# HYBRID_COMPUTER.net
KiCad netlist of a schematic drawn in EAGLE
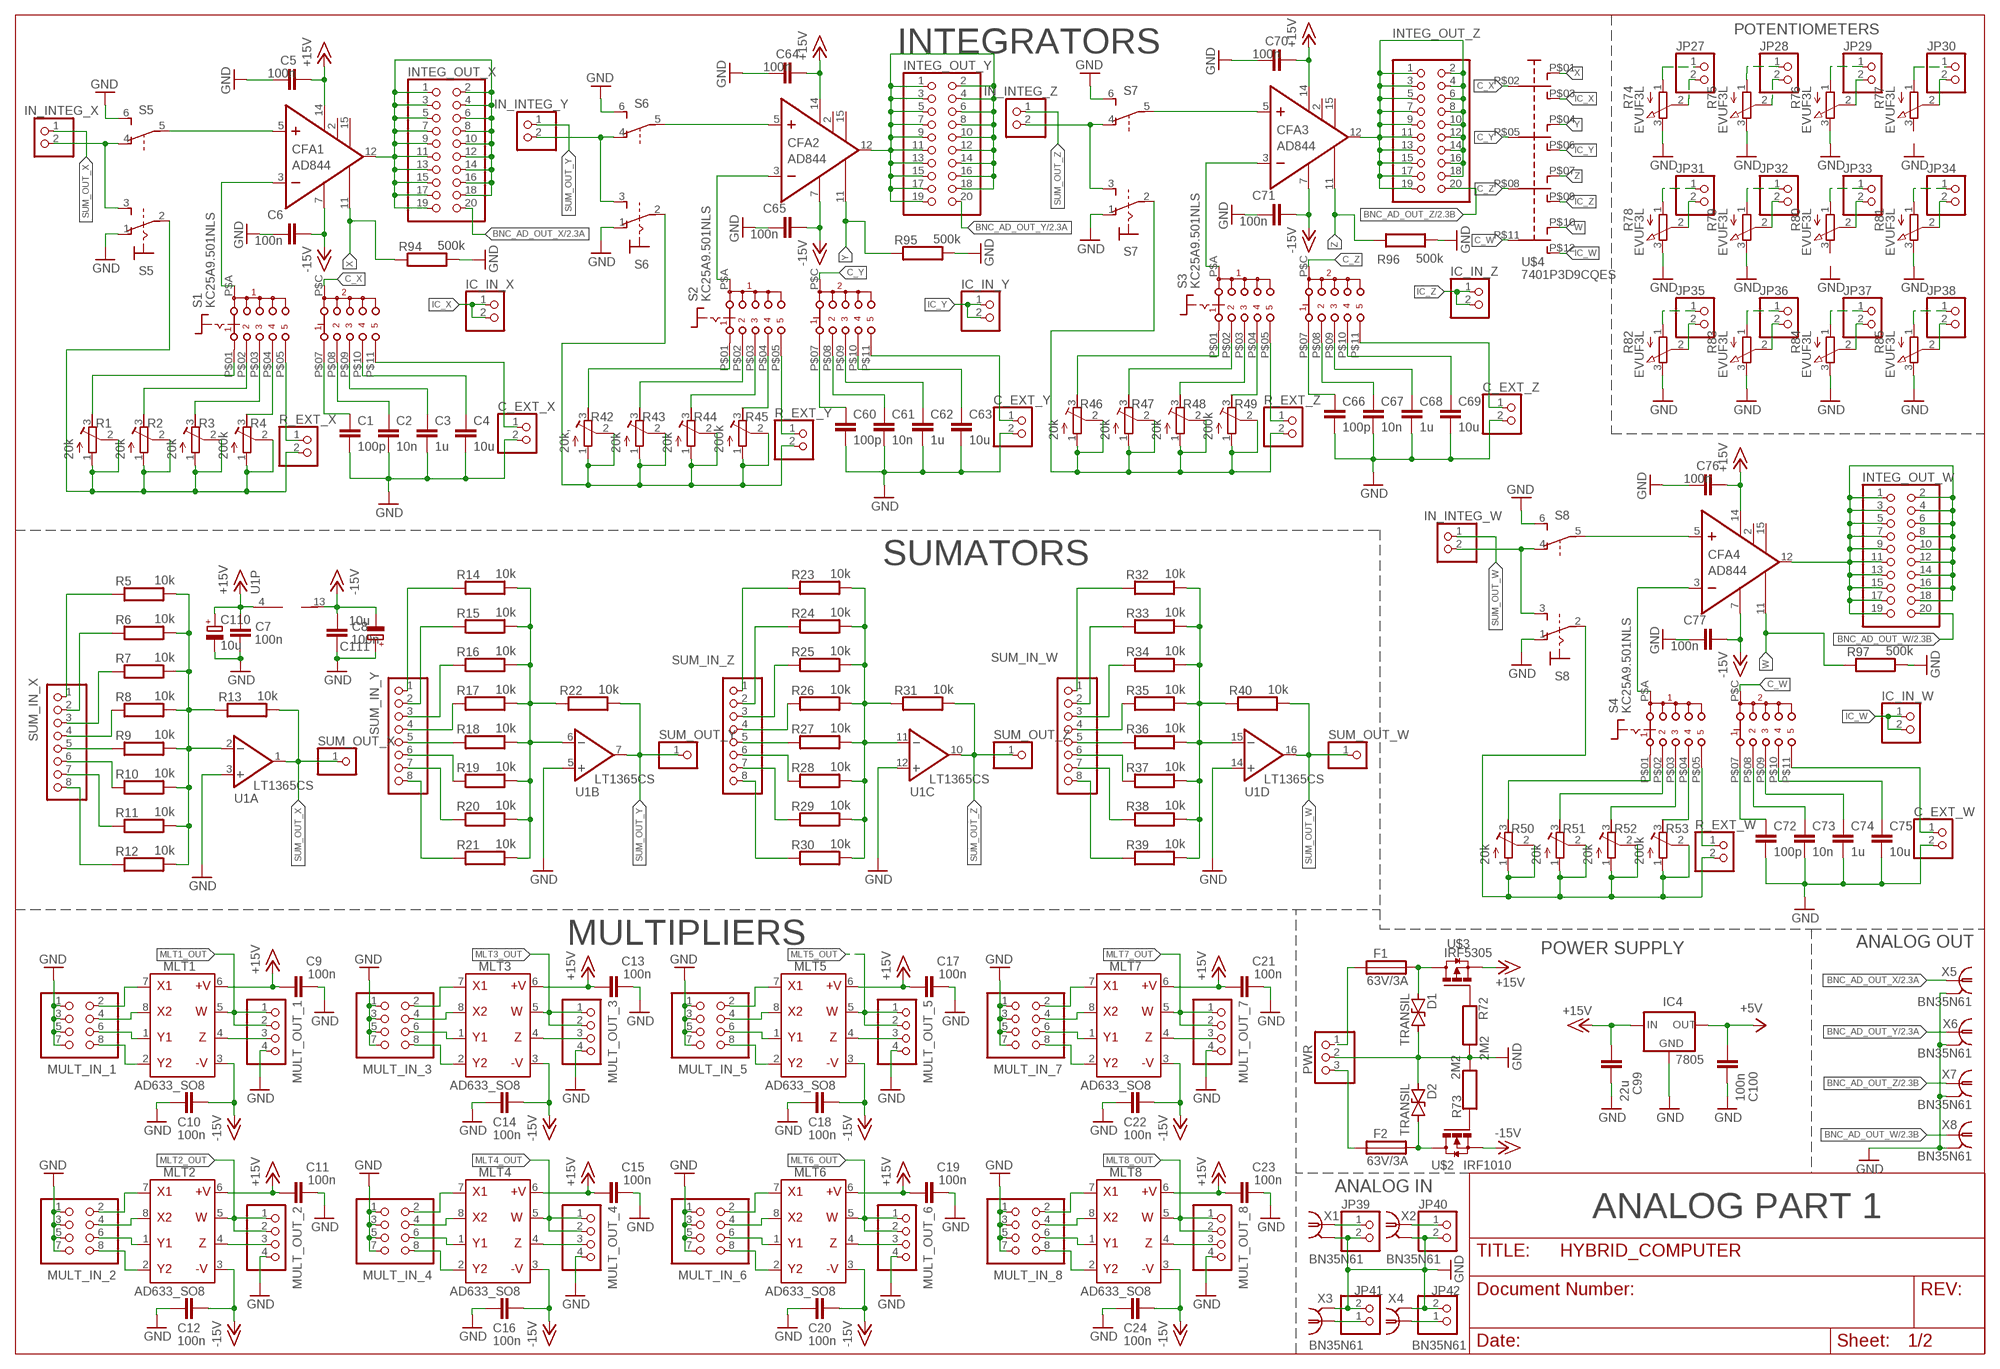
[diagram p0: schematic, sheet 1]
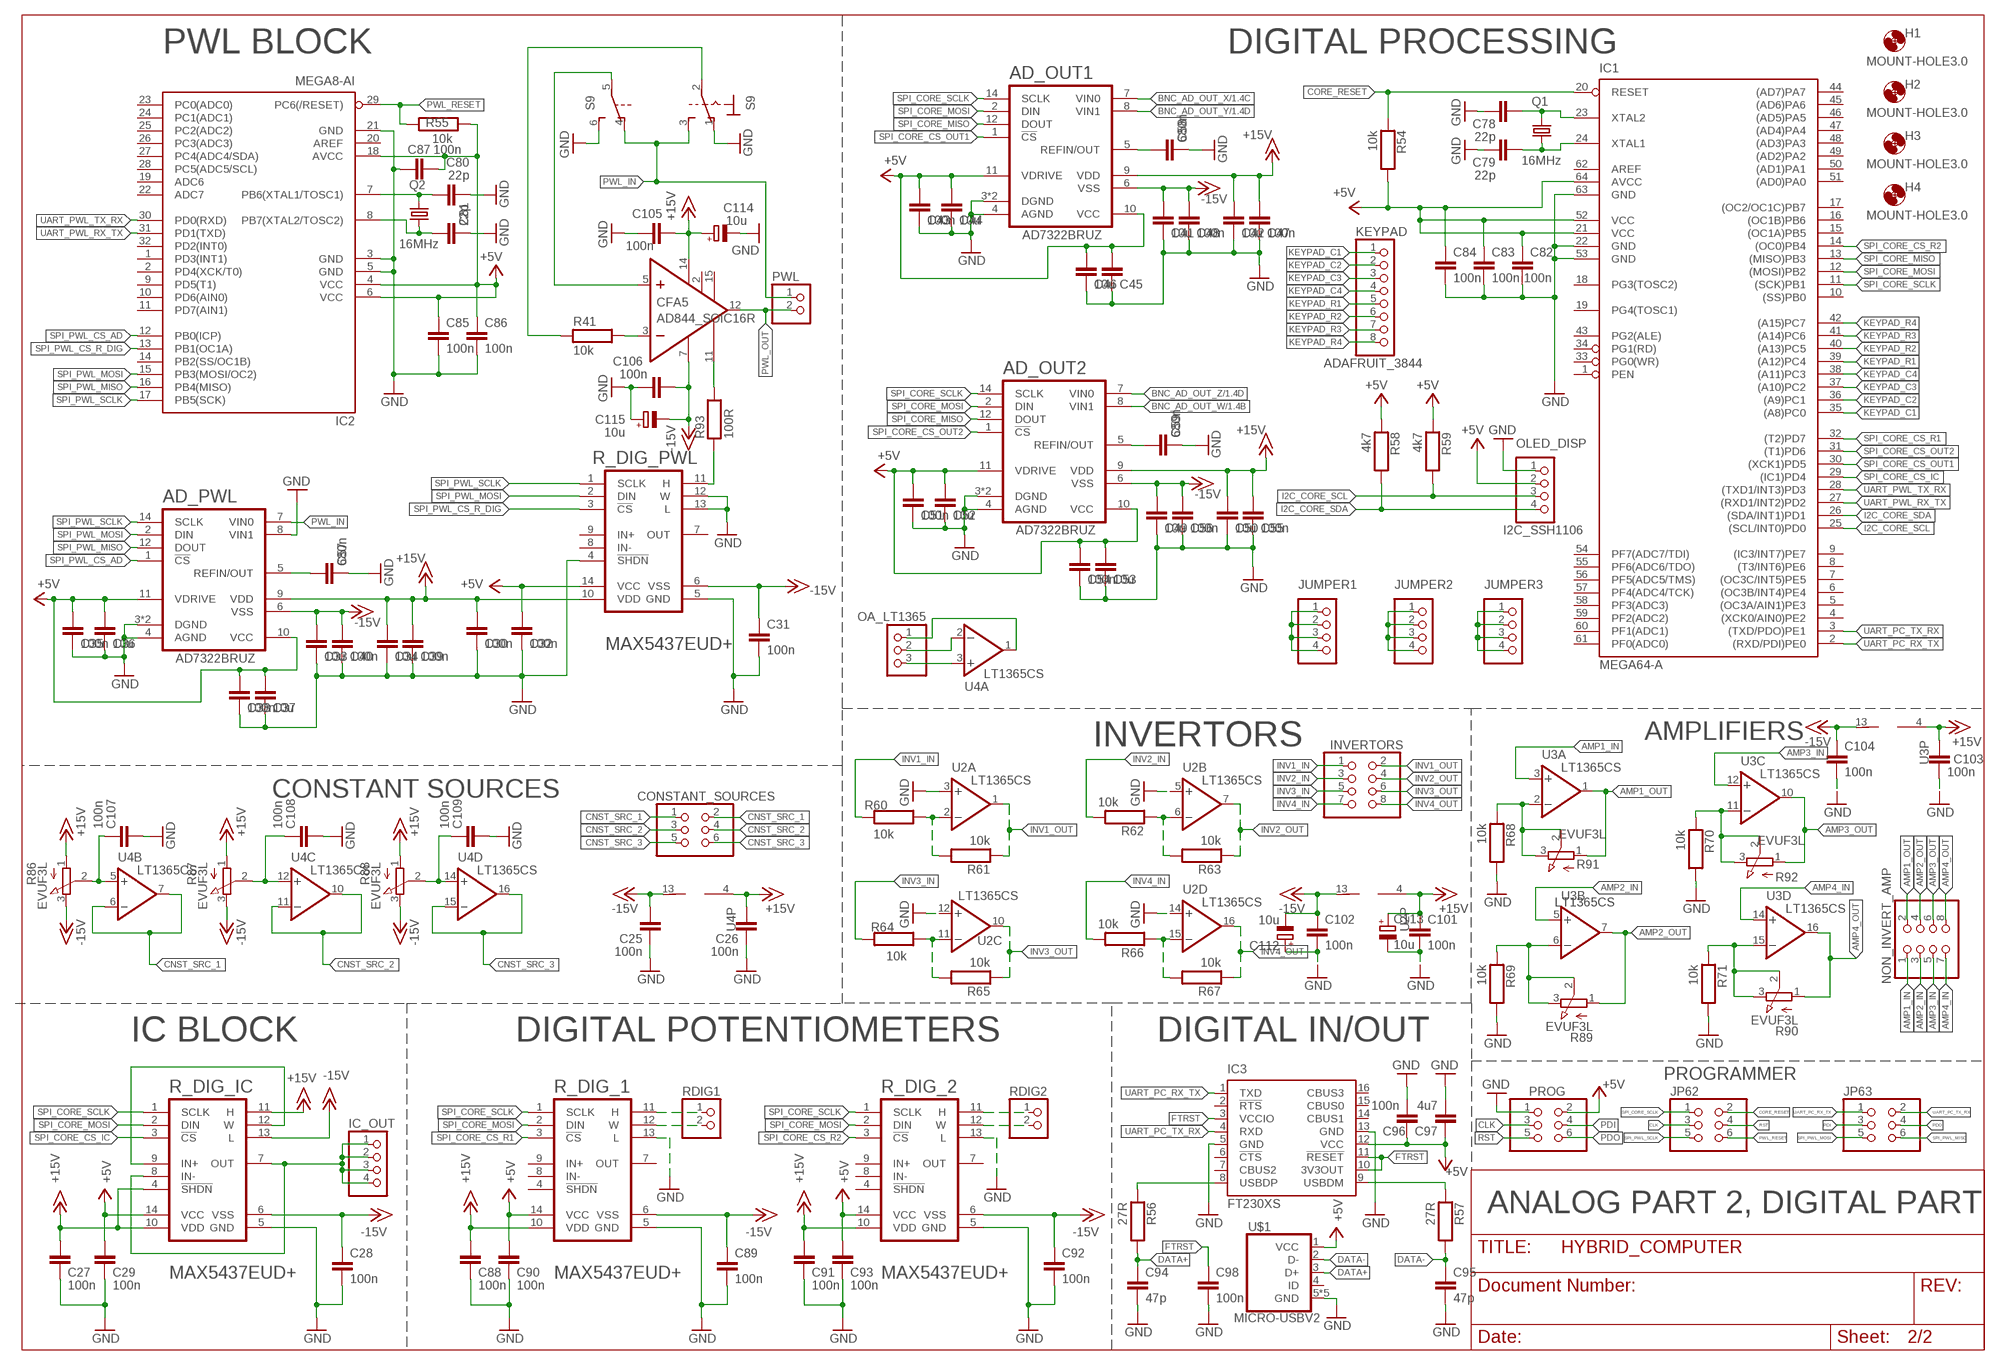
[diagram p1: schematic, sheet 2]

(export (version "E")
  (design (tool "Eeschema 10.0.6"))
  (components
    (comp (ref "C1")
      (value "100p")
      (footprint "eagle-import:C_1206")
      (libsource (lib "eagle-import") (part "C_1206"))
    )
    (comp (ref "C2")
      (value "10n")
      (footprint "eagle-import:C_1206")
      (libsource (lib "eagle-import") (part "C_1206"))
    )
    (comp (ref "C3")
      (value "1u")
      (footprint "eagle-import:C_1206")
      (libsource (lib "eagle-import") (part "C_1206"))
    )
    (comp (ref "C4")
      (value "10u")
      (footprint "eagle-import:C_1206")
      (libsource (lib "eagle-import") (part "C_1206"))
    )
    (comp (ref "C5")
      (value "100n")
      (footprint "eagle-import:C_1206")
      (libsource (lib "eagle-import") (part "C_1206"))
    )
    (comp (ref "C6")
      (value "100n")
      (footprint "eagle-import:C_1206")
      (libsource (lib "eagle-import") (part "C_1206"))
    )
    (comp (ref "C7")
      (value "100n")
      (footprint "eagle-import:C_1206")
      (libsource (lib "eagle-import") (part "C_1206"))
    )
    (comp (ref "C8")
      (value "100n")
      (footprint "eagle-import:C_1206")
      (libsource (lib "eagle-import") (part "C_1206"))
    )
    (comp (ref "C9")
      (value "100n")
      (footprint "eagle-import:C_1206")
      (libsource (lib "eagle-import") (part "C_1206"))
    )
    (comp (ref "C10")
      (value "100n")
      (footprint "eagle-import:C_1206")
      (libsource (lib "eagle-import") (part "C_1206"))
    )
    (comp (ref "C11")
      (value "100n")
      (footprint "eagle-import:C_1206")
      (libsource (lib "eagle-import") (part "C_1206"))
    )
    (comp (ref "C12")
      (value "100n")
      (footprint "eagle-import:C_1206")
      (libsource (lib "eagle-import") (part "C_1206"))
    )
    (comp (ref "C13")
      (value "100n")
      (footprint "eagle-import:C_1206")
      (libsource (lib "eagle-import") (part "C_1206"))
    )
    (comp (ref "C14")
      (value "100n")
      (footprint "eagle-import:C_1206")
      (libsource (lib "eagle-import") (part "C_1206"))
    )
    (comp (ref "C15")
      (value "100n")
      (footprint "eagle-import:C_1206")
      (libsource (lib "eagle-import") (part "C_1206"))
    )
    (comp (ref "C16")
      (value "100n")
      (footprint "eagle-import:C_1206")
      (libsource (lib "eagle-import") (part "C_1206"))
    )
    (comp (ref "C17")
      (value "100n")
      (footprint "eagle-import:C_1206")
      (libsource (lib "eagle-import") (part "C_1206"))
    )
    (comp (ref "C18")
      (value "100n")
      (footprint "eagle-import:C_1206")
      (libsource (lib "eagle-import") (part "C_1206"))
    )
    (comp (ref "C19")
      (value "100n")
      (footprint "eagle-import:C_1206")
      (libsource (lib "eagle-import") (part "C_1206"))
    )
    (comp (ref "C20")
      (value "100n")
      (footprint "eagle-import:C_1206")
      (libsource (lib "eagle-import") (part "C_1206"))
    )
    (comp (ref "C21")
      (value "100n")
      (footprint "eagle-import:C_1206")
      (libsource (lib "eagle-import") (part "C_1206"))
    )
    (comp (ref "C22")
      (value "100n")
      (footprint "eagle-import:C_1206")
      (libsource (lib "eagle-import") (part "C_1206"))
    )
    (comp (ref "C23")
      (value "100n")
      (footprint "eagle-import:C_1206")
      (libsource (lib "eagle-import") (part "C_1206"))
    )
    (comp (ref "C24")
      (value "100n")
      (footprint "eagle-import:C_1206")
      (libsource (lib "eagle-import") (part "C_1206"))
    )
    (comp (ref "C60")
      (value "100p")
      (footprint "eagle-import:C_1206")
      (libsource (lib "eagle-import") (part "C_1206"))
    )
    (comp (ref "C61")
      (value "10n")
      (footprint "eagle-import:C_1206")
      (libsource (lib "eagle-import") (part "C_1206"))
    )
    (comp (ref "C62")
      (value "1u")
      (footprint "eagle-import:C_1206")
      (libsource (lib "eagle-import") (part "C_1206"))
    )
    (comp (ref "C63")
      (value "10u")
      (footprint "eagle-import:C_1206")
      (libsource (lib "eagle-import") (part "C_1206"))
    )
    (comp (ref "C64")
      (value "100n")
      (footprint "eagle-import:C_1206")
      (libsource (lib "eagle-import") (part "C_1206"))
    )
    (comp (ref "C65")
      (value "100n")
      (footprint "eagle-import:C_1206")
      (libsource (lib "eagle-import") (part "C_1206"))
    )
    (comp (ref "C66")
      (value "100p")
      (footprint "eagle-import:C_1206")
      (libsource (lib "eagle-import") (part "C_1206"))
    )
    (comp (ref "C67")
      (value "10n")
      (footprint "eagle-import:C_1206")
      (libsource (lib "eagle-import") (part "C_1206"))
    )
    (comp (ref "C68")
      (value "1u")
      (footprint "eagle-import:C_1206")
      (libsource (lib "eagle-import") (part "C_1206"))
    )
    (comp (ref "C69")
      (value "10u")
      (footprint "eagle-import:C_1206")
      (libsource (lib "eagle-import") (part "C_1206"))
    )
    (comp (ref "C70")
      (value "100n")
      (footprint "eagle-import:C_1206")
      (libsource (lib "eagle-import") (part "C_1206"))
    )
    (comp (ref "C71")
      (value "100n")
      (footprint "eagle-import:C_1206")
      (libsource (lib "eagle-import") (part "C_1206"))
    )
    (comp (ref "C72")
      (value "100p")
      (footprint "eagle-import:C_1206")
      (libsource (lib "eagle-import") (part "C_1206"))
    )
    (comp (ref "C73")
      (value "10n")
      (footprint "eagle-import:C_1206")
      (libsource (lib "eagle-import") (part "C_1206"))
    )
    (comp (ref "C74")
      (value "1u")
      (footprint "eagle-import:C_1206")
      (libsource (lib "eagle-import") (part "C_1206"))
    )
    (comp (ref "C75")
      (value "10u")
      (footprint "eagle-import:C_1206")
      (libsource (lib "eagle-import") (part "C_1206"))
    )
    (comp (ref "C76")
      (value "100n")
      (footprint "eagle-import:C_1206")
      (libsource (lib "eagle-import") (part "C_1206"))
    )
    (comp (ref "C77")
      (value "100n")
      (footprint "eagle-import:C_1206")
      (libsource (lib "eagle-import") (part "C_1206"))
    )
    (comp (ref "C99")
      (value "22u")
      (footprint "eagle-import:C_1206")
      (libsource (lib "eagle-import") (part "C_1206"))
    )
    (comp (ref "C100")
      (value "100n")
      (footprint "eagle-import:C_1206")
      (libsource (lib "eagle-import") (part "C_1206"))
    )
    (comp (ref "C110")
      (value "10u")
      (footprint "eagle-import:E2,5-5")
      (libsource (lib "eagle-import") (part "CPOL-EUE2.5-5"))
    )
    (comp (ref "C111")
      (value "10u")
      (footprint "eagle-import:E2,5-5")
      (libsource (lib "eagle-import") (part "CPOL-EUE2.5-5"))
    )
    (comp (ref "CFA1")
      (value "AD844")
      (footprint "eagle-import:SOIC16R")
      (libsource (lib "eagle-import") (part "AD844_SOIC16R"))
    )
    (comp (ref "CFA2")
      (value "AD844")
      (footprint "eagle-import:SOIC16R")
      (libsource (lib "eagle-import") (part "AD844_SOIC16R"))
    )
    (comp (ref "CFA3")
      (value "AD844")
      (footprint "eagle-import:SOIC16R")
      (libsource (lib "eagle-import") (part "AD844_SOIC16R"))
    )
    (comp (ref "CFA4")
      (value "AD844")
      (footprint "eagle-import:SOIC16R")
      (libsource (lib "eagle-import") (part "AD844_SOIC16R"))
    )
    (comp (ref "C_EXT_W")
      (value "PINHD-1X2")
      (footprint "eagle-import:1X02")
      (libsource (lib "eagle-import") (part "PINHD-1X2"))
    )
    (comp (ref "C_EXT_X")
      (value "PINHD-1X2")
      (footprint "eagle-import:1X02")
      (libsource (lib "eagle-import") (part "PINHD-1X2"))
    )
    (comp (ref "C_EXT_Y")
      (value "PINHD-1X2")
      (footprint "eagle-import:1X02")
      (libsource (lib "eagle-import") (part "PINHD-1X2"))
    )
    (comp (ref "C_EXT_Z")
      (value "PINHD-1X2")
      (footprint "eagle-import:1X02")
      (libsource (lib "eagle-import") (part "PINHD-1X2"))
    )
    (comp (ref "D1")
      (value "TRANSIL")
      (footprint "eagle-import:DO15-12")
      (libsource (lib "eagle-import") (part "TRANSIL"))
    )
    (comp (ref "D2")
      (value "TRANSIL")
      (footprint "eagle-import:DO15-12")
      (libsource (lib "eagle-import") (part "TRANSIL"))
    )
    (comp (ref "F1")
      (value "63V/3A")
      (footprint "eagle-import:FUSE_1206")
      (libsource (lib "eagle-import") (part "FUSE"))
    )
    (comp (ref "F2")
      (value "63V/3A")
      (footprint "eagle-import:FUSE_1206")
      (libsource (lib "eagle-import") (part "FUSE"))
    )
    (comp (ref "IC4")
      (value "7805")
      (footprint "eagle-import:78MXXS")
      (libsource (lib "eagle-import") (part "78MXXS"))
    )
    (comp (ref "IC_IN_W")
      (value "PINHD-1X2")
      (footprint "eagle-import:1X02")
      (libsource (lib "eagle-import") (part "PINHD-1X2"))
    )
    (comp (ref "IC_IN_X")
      (value "PINHD-1X2")
      (footprint "eagle-import:1X02")
      (libsource (lib "eagle-import") (part "PINHD-1X2"))
    )
    (comp (ref "IC_IN_Y")
      (value "PINHD-1X2")
      (footprint "eagle-import:1X02")
      (libsource (lib "eagle-import") (part "PINHD-1X2"))
    )
    (comp (ref "IC_IN_Z")
      (value "PINHD-1X2")
      (footprint "eagle-import:1X02")
      (libsource (lib "eagle-import") (part "PINHD-1X2"))
    )
    (comp (ref "INTEG_OUT_W")
      (value "PINHD-2X10")
      (footprint "eagle-import:2X10")
      (libsource (lib "eagle-import") (part "PINHD-2X10"))
    )
    (comp (ref "INTEG_OUT_X")
      (value "PINHD-2X10")
      (footprint "eagle-import:2X10")
      (libsource (lib "eagle-import") (part "PINHD-2X10"))
    )
    (comp (ref "INTEG_OUT_Y")
      (value "PINHD-2X10")
      (footprint "eagle-import:2X10")
      (libsource (lib "eagle-import") (part "PINHD-2X10"))
    )
    (comp (ref "INTEG_OUT_Z")
      (value "PINHD-2X10")
      (footprint "eagle-import:2X10")
      (libsource (lib "eagle-import") (part "PINHD-2X10"))
    )
    (comp (ref "IN_INTEG_W")
      (value "PINHD-1X2")
      (footprint "eagle-import:1X02")
      (libsource (lib "eagle-import") (part "PINHD-1X2"))
    )
    (comp (ref "IN_INTEG_X")
      (value "PINHD-1X2")
      (footprint "eagle-import:1X02")
      (libsource (lib "eagle-import") (part "PINHD-1X2"))
    )
    (comp (ref "IN_INTEG_Y")
      (value "PINHD-1X2")
      (footprint "eagle-import:1X02")
      (libsource (lib "eagle-import") (part "PINHD-1X2"))
    )
    (comp (ref "IN_INTEG_Z")
      (value "PINHD-1X2")
      (footprint "eagle-import:1X02")
      (libsource (lib "eagle-import") (part "PINHD-1X2"))
    )
    (comp (ref "JP27")
      (value "PINHD-1X2")
      (footprint "eagle-import:1X02")
      (libsource (lib "eagle-import") (part "PINHD-1X2"))
    )
    (comp (ref "JP28")
      (value "PINHD-1X2")
      (footprint "eagle-import:1X02")
      (libsource (lib "eagle-import") (part "PINHD-1X2"))
    )
    (comp (ref "JP29")
      (value "PINHD-1X2")
      (footprint "eagle-import:1X02")
      (libsource (lib "eagle-import") (part "PINHD-1X2"))
    )
    (comp (ref "JP30")
      (value "PINHD-1X2")
      (footprint "eagle-import:1X02")
      (libsource (lib "eagle-import") (part "PINHD-1X2"))
    )
    (comp (ref "JP31")
      (value "PINHD-1X2")
      (footprint "eagle-import:1X02")
      (libsource (lib "eagle-import") (part "PINHD-1X2"))
    )
    (comp (ref "JP32")
      (value "PINHD-1X2")
      (footprint "eagle-import:1X02")
      (libsource (lib "eagle-import") (part "PINHD-1X2"))
    )
    (comp (ref "JP33")
      (value "PINHD-1X2")
      (footprint "eagle-import:1X02")
      (libsource (lib "eagle-import") (part "PINHD-1X2"))
    )
    (comp (ref "JP34")
      (value "PINHD-1X2")
      (footprint "eagle-import:1X02")
      (libsource (lib "eagle-import") (part "PINHD-1X2"))
    )
    (comp (ref "JP35")
      (value "PINHD-1X2")
      (footprint "eagle-import:1X02")
      (libsource (lib "eagle-import") (part "PINHD-1X2"))
    )
    (comp (ref "JP36")
      (value "PINHD-1X2")
      (footprint "eagle-import:1X02")
      (libsource (lib "eagle-import") (part "PINHD-1X2"))
    )
    (comp (ref "JP37")
      (value "PINHD-1X2")
      (footprint "eagle-import:1X02")
      (libsource (lib "eagle-import") (part "PINHD-1X2"))
    )
    (comp (ref "JP38")
      (value "PINHD-1X2")
      (footprint "eagle-import:1X02")
      (libsource (lib "eagle-import") (part "PINHD-1X2"))
    )
    (comp (ref "JP39")
      (value "PINHD-1X2")
      (footprint "eagle-import:1X02")
      (libsource (lib "eagle-import") (part "PINHD-1X2"))
    )
    (comp (ref "JP40")
      (value "PINHD-1X2")
      (footprint "eagle-import:1X02")
      (libsource (lib "eagle-import") (part "PINHD-1X2"))
    )
    (comp (ref "JP41")
      (value "PINHD-1X2")
      (footprint "eagle-import:1X02")
      (libsource (lib "eagle-import") (part "PINHD-1X2"))
    )
    (comp (ref "JP42")
      (value "PINHD-1X2")
      (footprint "eagle-import:1X02")
      (libsource (lib "eagle-import") (part "PINHD-1X2"))
    )
    (comp (ref "MLT1")
      (value "AD633_SO8")
      (footprint "eagle-import:SO8")
      (libsource (lib "eagle-import") (part "AD633_SO8"))
    )
    (comp (ref "MLT2")
      (value "AD633_SO8")
      (footprint "eagle-import:SO8")
      (libsource (lib "eagle-import") (part "AD633_SO8"))
    )
    (comp (ref "MLT3")
      (value "AD633_SO8")
      (footprint "eagle-import:SO8")
      (libsource (lib "eagle-import") (part "AD633_SO8"))
    )
    (comp (ref "MLT4")
      (value "AD633_SO8")
      (footprint "eagle-import:SO8")
      (libsource (lib "eagle-import") (part "AD633_SO8"))
    )
    (comp (ref "MLT5")
      (value "AD633_SO8")
      (footprint "eagle-import:SO8")
      (libsource (lib "eagle-import") (part "AD633_SO8"))
    )
    (comp (ref "MLT6")
      (value "AD633_SO8")
      (footprint "eagle-import:SO8")
      (libsource (lib "eagle-import") (part "AD633_SO8"))
    )
    (comp (ref "MLT7")
      (value "AD633_SO8")
      (footprint "eagle-import:SO8")
      (libsource (lib "eagle-import") (part "AD633_SO8"))
    )
    (comp (ref "MLT8")
      (value "AD633_SO8")
      (footprint "eagle-import:SO8")
      (libsource (lib "eagle-import") (part "AD633_SO8"))
    )
    (comp (ref "MULT_IN_1")
      (value "PINHD-2X4")
      (footprint "eagle-import:2X04")
      (libsource (lib "eagle-import") (part "PINHD-2X4"))
    )
    (comp (ref "MULT_IN_2")
      (value "PINHD-2X4")
      (footprint "eagle-import:2X04")
      (libsource (lib "eagle-import") (part "PINHD-2X4"))
    )
    (comp (ref "MULT_IN_3")
      (value "PINHD-2X4")
      (footprint "eagle-import:2X04")
      (libsource (lib "eagle-import") (part "PINHD-2X4"))
    )
    (comp (ref "MULT_IN_4")
      (value "PINHD-2X4")
      (footprint "eagle-import:2X04")
      (libsource (lib "eagle-import") (part "PINHD-2X4"))
    )
    (comp (ref "MULT_IN_5")
      (value "PINHD-2X4")
      (footprint "eagle-import:2X04")
      (libsource (lib "eagle-import") (part "PINHD-2X4"))
    )
    (comp (ref "MULT_IN_6")
      (value "PINHD-2X4")
      (footprint "eagle-import:2X04")
      (libsource (lib "eagle-import") (part "PINHD-2X4"))
    )
    (comp (ref "MULT_IN_7")
      (value "PINHD-2X4")
      (footprint "eagle-import:2X04")
      (libsource (lib "eagle-import") (part "PINHD-2X4"))
    )
    (comp (ref "MULT_IN_8")
      (value "PINHD-2X4")
      (footprint "eagle-import:2X04")
      (libsource (lib "eagle-import") (part "PINHD-2X4"))
    )
    (comp (ref "MULT_OUT_1")
      (value "PINHD-1X4")
      (footprint "eagle-import:1X04")
      (libsource (lib "eagle-import") (part "PINHD-1X4"))
    )
    (comp (ref "MULT_OUT_2")
      (value "PINHD-1X4")
      (footprint "eagle-import:1X04")
      (libsource (lib "eagle-import") (part "PINHD-1X4"))
    )
    (comp (ref "MULT_OUT_3")
      (value "PINHD-1X4")
      (footprint "eagle-import:1X04")
      (libsource (lib "eagle-import") (part "PINHD-1X4"))
    )
    (comp (ref "MULT_OUT_4")
      (value "PINHD-1X4")
      (footprint "eagle-import:1X04")
      (libsource (lib "eagle-import") (part "PINHD-1X4"))
    )
    (comp (ref "MULT_OUT_5")
      (value "PINHD-1X4")
      (footprint "eagle-import:1X04")
      (libsource (lib "eagle-import") (part "PINHD-1X4"))
    )
    (comp (ref "MULT_OUT_6")
      (value "PINHD-1X4")
      (footprint "eagle-import:1X04")
      (libsource (lib "eagle-import") (part "PINHD-1X4"))
    )
    (comp (ref "MULT_OUT_7")
      (value "PINHD-1X4")
      (footprint "eagle-import:1X04")
      (libsource (lib "eagle-import") (part "PINHD-1X4"))
    )
    (comp (ref "MULT_OUT_8")
      (value "PINHD-1X4")
      (footprint "eagle-import:1X04")
      (libsource (lib "eagle-import") (part "PINHD-1X4"))
    )
    (comp (ref "PWR")
      (value "PINHD-1X3")
      (footprint "eagle-import:1X03")
      (libsource (lib "eagle-import") (part "PINHD-1X3"))
    )
    (comp (ref "R1")
      (value "20k")
      (footprint "eagle-import:RTRIM64W")
      (libsource (lib "eagle-import") (part "R-TRIMM64W"))
    )
    (comp (ref "R2")
      (value "20k")
      (footprint "eagle-import:RTRIM64W")
      (libsource (lib "eagle-import") (part "R-TRIMM64W"))
    )
    (comp (ref "R3")
      (value "20k")
      (footprint "eagle-import:RTRIM64W")
      (libsource (lib "eagle-import") (part "R-TRIMM64W"))
    )
    (comp (ref "R4")
      (value "200k")
      (footprint "eagle-import:RTRIM64W")
      (libsource (lib "eagle-import") (part "R-TRIMM64W"))
    )
    (comp (ref "R5")
      (value "10k")
      (footprint "eagle-import:R_1206")
      (libsource (lib "eagle-import") (part "R_1206"))
    )
    (comp (ref "R6")
      (value "10k")
      (footprint "eagle-import:R_1206")
      (libsource (lib "eagle-import") (part "R_1206"))
    )
    (comp (ref "R7")
      (value "10k")
      (footprint "eagle-import:R_1206")
      (libsource (lib "eagle-import") (part "R_1206"))
    )
    (comp (ref "R8")
      (value "10k")
      (footprint "eagle-import:R_1206")
      (libsource (lib "eagle-import") (part "R_1206"))
    )
    (comp (ref "R9")
      (value "10k")
      (footprint "eagle-import:R_1206")
      (libsource (lib "eagle-import") (part "R_1206"))
    )
    (comp (ref "R10")
      (value "10k")
      (footprint "eagle-import:R_1206")
      (libsource (lib "eagle-import") (part "R_1206"))
    )
    (comp (ref "R11")
      (value "10k")
      (footprint "eagle-import:R_1206")
      (libsource (lib "eagle-import") (part "R_1206"))
    )
    (comp (ref "R12")
      (value "10k")
      (footprint "eagle-import:R_1206")
      (libsource (lib "eagle-import") (part "R_1206"))
    )
    (comp (ref "R13")
      (value "10k")
      (footprint "eagle-import:R_1206")
      (libsource (lib "eagle-import") (part "R_1206"))
    )
    (comp (ref "R14")
      (value "10k")
      (footprint "eagle-import:R_1206")
      (libsource (lib "eagle-import") (part "R_1206"))
    )
    (comp (ref "R15")
      (value "10k")
      (footprint "eagle-import:R_1206")
      (libsource (lib "eagle-import") (part "R_1206"))
    )
    (comp (ref "R16")
      (value "10k")
      (footprint "eagle-import:R_1206")
      (libsource (lib "eagle-import") (part "R_1206"))
    )
    (comp (ref "R17")
      (value "10k")
      (footprint "eagle-import:R_1206")
      (libsource (lib "eagle-import") (part "R_1206"))
    )
    (comp (ref "R18")
      (value "10k")
      (footprint "eagle-import:R_1206")
      (libsource (lib "eagle-import") (part "R_1206"))
    )
    (comp (ref "R19")
      (value "10k")
      (footprint "eagle-import:R_1206")
      (libsource (lib "eagle-import") (part "R_1206"))
    )
    (comp (ref "R20")
      (value "10k")
      (footprint "eagle-import:R_1206")
      (libsource (lib "eagle-import") (part "R_1206"))
    )
    (comp (ref "R21")
      (value "10k")
      (footprint "eagle-import:R_1206")
      (libsource (lib "eagle-import") (part "R_1206"))
    )
    (comp (ref "R22")
      (value "10k")
      (footprint "eagle-import:R_1206")
      (libsource (lib "eagle-import") (part "R_1206"))
    )
    (comp (ref "R23")
      (value "10k")
      (footprint "eagle-import:R_1206")
      (libsource (lib "eagle-import") (part "R_1206"))
    )
    (comp (ref "R24")
      (value "10k")
      (footprint "eagle-import:R_1206")
      (libsource (lib "eagle-import") (part "R_1206"))
    )
    (comp (ref "R25")
      (value "10k")
      (footprint "eagle-import:R_1206")
      (libsource (lib "eagle-import") (part "R_1206"))
    )
    (comp (ref "R26")
      (value "10k")
      (footprint "eagle-import:R_1206")
      (libsource (lib "eagle-import") (part "R_1206"))
    )
    (comp (ref "R27")
      (value "10k")
      (footprint "eagle-import:R_1206")
      (libsource (lib "eagle-import") (part "R_1206"))
    )
    (comp (ref "R28")
      (value "10k")
      (footprint "eagle-import:R_1206")
      (libsource (lib "eagle-import") (part "R_1206"))
    )
    (comp (ref "R29")
      (value "10k")
      (footprint "eagle-import:R_1206")
      (libsource (lib "eagle-import") (part "R_1206"))
    )
    (comp (ref "R30")
      (value "10k")
      (footprint "eagle-import:R_1206")
      (libsource (lib "eagle-import") (part "R_1206"))
    )
    (comp (ref "R31")
      (value "10k")
      (footprint "eagle-import:R_1206")
      (libsource (lib "eagle-import") (part "R_1206"))
    )
    (comp (ref "R32")
      (value "10k")
      (footprint "eagle-import:R_1206")
      (libsource (lib "eagle-import") (part "R_1206"))
    )
    (comp (ref "R33")
      (value "10k")
      (footprint "eagle-import:R_1206")
      (libsource (lib "eagle-import") (part "R_1206"))
    )
    (comp (ref "R34")
      (value "10k")
      (footprint "eagle-import:R_1206")
      (libsource (lib "eagle-import") (part "R_1206"))
    )
    (comp (ref "R35")
      (value "10k")
      (footprint "eagle-import:R_1206")
      (libsource (lib "eagle-import") (part "R_1206"))
    )
    (comp (ref "R36")
      (value "10k")
      (footprint "eagle-import:R_1206")
      (libsource (lib "eagle-import") (part "R_1206"))
    )
    (comp (ref "R37")
      (value "10k")
      (footprint "eagle-import:R_1206")
      (libsource (lib "eagle-import") (part "R_1206"))
    )
    (comp (ref "R38")
      (value "10k")
      (footprint "eagle-import:R_1206")
      (libsource (lib "eagle-import") (part "R_1206"))
    )
    (comp (ref "R39")
      (value "10k")
      (footprint "eagle-import:R_1206")
      (libsource (lib "eagle-import") (part "R_1206"))
    )
    (comp (ref "R40")
      (value "10k")
      (footprint "eagle-import:R_1206")
      (libsource (lib "eagle-import") (part "R_1206"))
    )
    (comp (ref "R42")
      (value "20k,")
      (footprint "eagle-import:RTRIM64W")
      (libsource (lib "eagle-import") (part "R-TRIMM64W"))
    )
    (comp (ref "R43")
      (value "20k")
      (footprint "eagle-import:RTRIM64W")
      (libsource (lib "eagle-import") (part "R-TRIMM64W"))
    )
    (comp (ref "R44")
      (value "20k")
      (footprint "eagle-import:RTRIM64W")
      (libsource (lib "eagle-import") (part "R-TRIMM64W"))
    )
    (comp (ref "R45")
      (value "200k")
      (footprint "eagle-import:RTRIM64W")
      (libsource (lib "eagle-import") (part "R-TRIMM64W"))
    )
    (comp (ref "R46")
      (value "20k")
      (footprint "eagle-import:RTRIM64W")
      (libsource (lib "eagle-import") (part "R-TRIMM64W"))
    )
    (comp (ref "R47")
      (value "20k")
      (footprint "eagle-import:RTRIM64W")
      (libsource (lib "eagle-import") (part "R-TRIMM64W"))
    )
    (comp (ref "R48")
      (value "20k")
      (footprint "eagle-import:RTRIM64W")
      (libsource (lib "eagle-import") (part "R-TRIMM64W"))
    )
    (comp (ref "R49")
      (value "200k")
      (footprint "eagle-import:RTRIM64W")
      (libsource (lib "eagle-import") (part "R-TRIMM64W"))
    )
    (comp (ref "R50")
      (value "20k")
      (footprint "eagle-import:RTRIM64W")
      (libsource (lib "eagle-import") (part "R-TRIMM64W"))
    )
    (comp (ref "R51")
      (value "20k")
      (footprint "eagle-import:RTRIM64W")
      (libsource (lib "eagle-import") (part "R-TRIMM64W"))
    )
    (comp (ref "R52")
      (value "20k")
      (footprint "eagle-import:RTRIM64W")
      (libsource (lib "eagle-import") (part "R-TRIMM64W"))
    )
    (comp (ref "R53")
      (value "200k")
      (footprint "eagle-import:RTRIM64W")
      (libsource (lib "eagle-import") (part "R-TRIMM64W"))
    )
    (comp (ref "R72")
      (value "2M2")
      (footprint "eagle-import:R_1206")
      (libsource (lib "eagle-import") (part "R_1206"))
    )
    (comp (ref "R73")
      (value "2M2")
      (footprint "eagle-import:R_1206")
      (libsource (lib "eagle-import") (part "R_1206"))
    )
    (comp (ref "R74")
      (value "EVUF3L")
      (footprint "eagle-import:EVUFXL")
      (libsource (lib "eagle-import") (part "EVULF3"))
    )
    (comp (ref "R75")
      (value "EVUF3L")
      (footprint "eagle-import:EVUFXL")
      (libsource (lib "eagle-import") (part "EVULF3"))
    )
    (comp (ref "R76")
      (value "EVUF3L")
      (footprint "eagle-import:EVUFXL")
      (libsource (lib "eagle-import") (part "EVULF3"))
    )
    (comp (ref "R77")
      (value "EVUF3L")
      (footprint "eagle-import:EVUFXL")
      (libsource (lib "eagle-import") (part "EVULF3"))
    )
    (comp (ref "R78")
      (value "EVUF3L")
      (footprint "eagle-import:EVUFXL")
      (libsource (lib "eagle-import") (part "EVULF3"))
    )
    (comp (ref "R79")
      (value "EVUF3L")
      (footprint "eagle-import:EVUFXL")
      (libsource (lib "eagle-import") (part "EVULF3"))
    )
    (comp (ref "R80")
      (value "EVUF3L")
      (footprint "eagle-import:EVUFXL")
      (libsource (lib "eagle-import") (part "EVULF3"))
    )
    (comp (ref "R81")
      (value "EVUF3L")
      (footprint "eagle-import:EVUFXL")
      (libsource (lib "eagle-import") (part "EVULF3"))
    )
    (comp (ref "R82")
      (value "EVUF3L")
      (footprint "eagle-import:EVUFXL")
      (libsource (lib "eagle-import") (part "EVULF3"))
    )
    (comp (ref "R83")
      (value "EVUF3L")
      (footprint "eagle-import:EVUFXL")
      (libsource (lib "eagle-import") (part "EVULF3"))
    )
    (comp (ref "R84")
      (value "EVUF3L")
      (footprint "eagle-import:EVUFXL")
      (libsource (lib "eagle-import") (part "EVULF3"))
    )
    (comp (ref "R85")
      (value "EVUF3L")
      (footprint "eagle-import:EVUFXL")
      (libsource (lib "eagle-import") (part "EVULF3"))
    )
    (comp (ref "R94")
      (value "500k")
      (footprint "eagle-import:R_1206")
      (libsource (lib "eagle-import") (part "R_1206"))
    )
    (comp (ref "R95")
      (value "500k")
      (footprint "eagle-import:R_1206")
      (libsource (lib "eagle-import") (part "R_1206"))
    )
    (comp (ref "R96")
      (value "500k")
      (footprint "eagle-import:R_1206")
      (libsource (lib "eagle-import") (part "R_1206"))
    )
    (comp (ref "R97")
      (value "500k")
      (footprint "eagle-import:R_1206")
      (libsource (lib "eagle-import") (part "R_1206"))
    )
    (comp (ref "R_EXT_W")
      (value "PINHD-1X2")
      (footprint "eagle-import:1X02")
      (libsource (lib "eagle-import") (part "PINHD-1X2"))
    )
    (comp (ref "R_EXT_X")
      (value "PINHD-1X2")
      (footprint "eagle-import:1X02")
      (libsource (lib "eagle-import") (part "PINHD-1X2"))
    )
    (comp (ref "R_EXT_Y")
      (value "PINHD-1X2")
      (footprint "eagle-import:1X02")
      (libsource (lib "eagle-import") (part "PINHD-1X2"))
    )
    (comp (ref "R_EXT_Z")
      (value "PINHD-1X2")
      (footprint "eagle-import:1X02")
      (libsource (lib "eagle-import") (part "PINHD-1X2"))
    )
    (comp (ref "S1")
      (value "KC25A9.501NLS")
      (footprint "eagle-import:KC25A9.501NLS")
      (libsource (lib "eagle-import") (part "KC25A9.501NLS"))
    )
    (comp (ref "S2")
      (value "KC25A9.501NLS")
      (footprint "eagle-import:KC25A9.501NLS")
      (libsource (lib "eagle-import") (part "KC25A9.501NLS"))
    )
    (comp (ref "S3")
      (value "KC25A9.501NLS")
      (footprint "eagle-import:KC25A9.501NLS")
      (libsource (lib "eagle-import") (part "KC25A9.501NLS"))
    )
    (comp (ref "S4")
      (value "KC25A9.501NLS")
      (footprint "eagle-import:KC25A9.501NLS")
      (libsource (lib "eagle-import") (part "KC25A9.501NLS"))
    )
    (comp (ref "S5")
      (value "320-938")
      (footprint "eagle-import:320-938")
      (libsource (lib "eagle-import") (part "320-938"))
    )
    (comp (ref "S6")
      (value "320-938")
      (footprint "eagle-import:320-938")
      (libsource (lib "eagle-import") (part "320-938"))
    )
    (comp (ref "S7")
      (value "320-938")
      (footprint "eagle-import:320-938")
      (libsource (lib "eagle-import") (part "320-938"))
    )
    (comp (ref "S8")
      (value "320-938")
      (footprint "eagle-import:320-938")
      (libsource (lib "eagle-import") (part "320-938"))
    )
    (comp (ref "SUM_IN_W")
      (value "PINHD-1X8")
      (footprint "eagle-import:1X08")
      (libsource (lib "eagle-import") (part "PINHD-1X8"))
    )
    (comp (ref "SUM_IN_X")
      (value "PINHD-1X8")
      (footprint "eagle-import:1X08")
      (libsource (lib "eagle-import") (part "PINHD-1X8"))
    )
    (comp (ref "SUM_IN_Y")
      (value "PINHD-1X8")
      (footprint "eagle-import:1X08")
      (libsource (lib "eagle-import") (part "PINHD-1X8"))
    )
    (comp (ref "SUM_IN_Z")
      (value "PINHD-1X8")
      (footprint "eagle-import:1X08")
      (libsource (lib "eagle-import") (part "PINHD-1X8"))
    )
    (comp (ref "SUM_OUT_W")
      (value "PINHD-1X1")
      (footprint "eagle-import:1X01")
      (libsource (lib "eagle-import") (part "PINHD-1X1"))
    )
    (comp (ref "SUM_OUT_X")
      (value "PINHD-1X1")
      (footprint "eagle-import:1X01")
      (libsource (lib "eagle-import") (part "PINHD-1X1"))
    )
    (comp (ref "SUM_OUT_Y")
      (value "PINHD-1X1")
      (footprint "eagle-import:1X01")
      (libsource (lib "eagle-import") (part "PINHD-1X1"))
    )
    (comp (ref "SUM_OUT_Z")
      (value "PINHD-1X1")
      (footprint "eagle-import:1X01")
      (libsource (lib "eagle-import") (part "PINHD-1X1"))
    )
    (comp (ref "U$2")
      (value "IRF1010")
      (footprint "eagle-import:TO220BV")
      (libsource (lib "eagle-import") (part "IRF1010"))
    )
    (comp (ref "U$3")
      (value "IRF5305")
      (footprint "eagle-import:TO220BV")
      (libsource (lib "eagle-import") (part "IRF5305"))
    )
    (comp (ref "U$4")
      (value "7401P3D9CQES")
      (footprint "eagle-import:7401P3D9CQES")
      (libsource (lib "eagle-import") (part "7401P3D9CQES"))
    )
    (comp (ref "U1")
      (value "LT1365CS")
      (footprint "eagle-import:SO16")
      (libsource (lib "eagle-import") (part "LT1365CS"))
    )
    (comp (ref "X1")
      (value "BN35N61")
      (footprint "eagle-import:B35N61")
      (libsource (lib "eagle-import") (part "BN35N61"))
    )
    (comp (ref "X2")
      (value "BN35N61")
      (footprint "eagle-import:B35N61")
      (libsource (lib "eagle-import") (part "BN35N61"))
    )
    (comp (ref "X3")
      (value "BN35N61")
      (footprint "eagle-import:B35N61")
      (libsource (lib "eagle-import") (part "BN35N61"))
    )
    (comp (ref "X4")
      (value "BN35N61")
      (footprint "eagle-import:B35N61")
      (libsource (lib "eagle-import") (part "BN35N61"))
    )
    (comp (ref "X5")
      (value "BN35N61")
      (footprint "eagle-import:B35N61")
      (libsource (lib "eagle-import") (part "BN35N61"))
    )
    (comp (ref "X6")
      (value "BN35N61")
      (footprint "eagle-import:B35N61")
      (libsource (lib "eagle-import") (part "BN35N61"))
    )
    (comp (ref "X7")
      (value "BN35N61")
      (footprint "eagle-import:B35N61")
      (libsource (lib "eagle-import") (part "BN35N61"))
    )
    (comp (ref "X8")
      (value "BN35N61")
      (footprint "eagle-import:B35N61")
      (libsource (lib "eagle-import") (part "BN35N61"))
    )
    (comp (ref "AD_OUT1")
      (value "AD7322")
      (footprint "eagle-import:TSSOP-14")
      (libsource (lib "eagle-import") (part "AD7322"))
    )
    (comp (ref "AD_OUT2")
      (value "AD7322")
      (footprint "eagle-import:TSSOP-14")
      (libsource (lib "eagle-import") (part "AD7322"))
    )
    (comp (ref "AD_PWL")
      (value "AD7322")
      (footprint "eagle-import:TSSOP-14")
      (libsource (lib "eagle-import") (part "AD7322"))
    )
    (comp (ref "C25")
      (value "100n")
      (footprint "eagle-import:C_1206")
      (libsource (lib "eagle-import") (part "C_1206"))
    )
    (comp (ref "C26")
      (value "100n")
      (footprint "eagle-import:C_1206")
      (libsource (lib "eagle-import") (part "C_1206"))
    )
    (comp (ref "C27")
      (value "100n")
      (footprint "eagle-import:C_1206")
      (libsource (lib "eagle-import") (part "C_1206"))
    )
    (comp (ref "C28")
      (value "100n")
      (footprint "eagle-import:C_1206")
      (libsource (lib "eagle-import") (part "C_1206"))
    )
    (comp (ref "C29")
      (value "100n")
      (footprint "eagle-import:C_1206")
      (libsource (lib "eagle-import") (part "C_1206"))
    )
    (comp (ref "C30")
      (value "100n")
      (footprint "eagle-import:C_1206")
      (libsource (lib "eagle-import") (part "C_1206"))
    )
    (comp (ref "C31")
      (value "100n")
      (footprint "eagle-import:C_1206")
      (libsource (lib "eagle-import") (part "C_1206"))
    )
    (comp (ref "C32")
      (value "100n")
      (footprint "eagle-import:C_1206")
      (libsource (lib "eagle-import") (part "C_1206"))
    )
    (comp (ref "C33")
      (value "10u")
      (footprint "eagle-import:C_1206")
      (libsource (lib "eagle-import") (part "C_1206"))
    )
    (comp (ref "C34")
      (value "10u")
      (footprint "eagle-import:C_1206")
      (libsource (lib "eagle-import") (part "C_1206"))
    )
    (comp (ref "C35")
      (value "100n")
      (footprint "eagle-import:C_1206")
      (libsource (lib "eagle-import") (part "C_1206"))
    )
    (comp (ref "C36")
      (value "10u")
      (footprint "eagle-import:C_1206")
      (libsource (lib "eagle-import") (part "C_1206"))
    )
    (comp (ref "C37")
      (value "10u")
      (footprint "eagle-import:C_1206")
      (libsource (lib "eagle-import") (part "C_1206"))
    )
    (comp (ref "C38")
      (value "100n")
      (footprint "eagle-import:C_1206")
      (libsource (lib "eagle-import") (part "C_1206"))
    )
    (comp (ref "C39")
      (value "100n")
      (footprint "eagle-import:C_1206")
      (libsource (lib "eagle-import") (part "C_1206"))
    )
    (comp (ref "C40")
      (value "100n")
      (footprint "eagle-import:C_1206")
      (libsource (lib "eagle-import") (part "C_1206"))
    )
    (comp (ref "C41")
      (value "10u")
      (footprint "eagle-import:C_1206")
      (libsource (lib "eagle-import") (part "C_1206"))
    )
    (comp (ref "C42")
      (value "10u")
      (footprint "eagle-import:C_1206")
      (libsource (lib "eagle-import") (part "C_1206"))
    )
    (comp (ref "C43")
      (value "100n")
      (footprint "eagle-import:C_1206")
      (libsource (lib "eagle-import") (part "C_1206"))
    )
    (comp (ref "C44")
      (value "10u")
      (footprint "eagle-import:C_1206")
      (libsource (lib "eagle-import") (part "C_1206"))
    )
    (comp (ref "C45")
      (value "C_1206")
      (footprint "eagle-import:C_1206")
      (libsource (lib "eagle-import") (part "C_1206"))
    )
    (comp (ref "C46")
      (value "10u")
      (footprint "eagle-import:C_1206")
      (libsource (lib "eagle-import") (part "C_1206"))
    )
    (comp (ref "C47")
      (value "100n")
      (footprint "eagle-import:C_1206")
      (libsource (lib "eagle-import") (part "C_1206"))
    )
    (comp (ref "C48")
      (value "100n")
      (footprint "eagle-import:C_1206")
      (libsource (lib "eagle-import") (part "C_1206"))
    )
    (comp (ref "C49")
      (value "10u")
      (footprint "eagle-import:C_1206")
      (libsource (lib "eagle-import") (part "C_1206"))
    )
    (comp (ref "C50")
      (value "10u")
      (footprint "eagle-import:C_1206")
      (libsource (lib "eagle-import") (part "C_1206"))
    )
    (comp (ref "C51")
      (value "100n")
      (footprint "eagle-import:C_1206")
      (libsource (lib "eagle-import") (part "C_1206"))
    )
    (comp (ref "C52")
      (value "10u")
      (footprint "eagle-import:C_1206")
      (libsource (lib "eagle-import") (part "C_1206"))
    )
    (comp (ref "C53")
      (value "10u")
      (footprint "eagle-import:C_1206")
      (libsource (lib "eagle-import") (part "C_1206"))
    )
    (comp (ref "C54")
      (value "100n")
      (footprint "eagle-import:C_1206")
      (libsource (lib "eagle-import") (part "C_1206"))
    )
    (comp (ref "C55")
      (value "100n")
      (footprint "eagle-import:C_1206")
      (libsource (lib "eagle-import") (part "C_1206"))
    )
    (comp (ref "C56")
      (value "100n")
      (footprint "eagle-import:C_1206")
      (libsource (lib "eagle-import") (part "C_1206"))
    )
    (comp (ref "C57")
      (value "680n")
      (footprint "eagle-import:C_1206")
      (libsource (lib "eagle-import") (part "C_1206"))
    )
    (comp (ref "C58")
      (value "680n")
      (footprint "eagle-import:C_1206")
      (libsource (lib "eagle-import") (part "C_1206"))
    )
    (comp (ref "C59")
      (value "680n")
      (footprint "eagle-import:C_1206")
      (libsource (lib "eagle-import") (part "C_1206"))
    )
    (comp (ref "C78")
      (value "22p")
      (footprint "eagle-import:C_1206")
      (libsource (lib "eagle-import") (part "C_1206"))
    )
    (comp (ref "C79")
      (value "22p")
      (footprint "eagle-import:C_1206")
      (libsource (lib "eagle-import") (part "C_1206"))
    )
    (comp (ref "C80")
      (value "22p")
      (footprint "eagle-import:C_1206")
      (libsource (lib "eagle-import") (part "C_1206"))
    )
    (comp (ref "C81")
      (value "22p")
      (footprint "eagle-import:C_1206")
      (libsource (lib "eagle-import") (part "C_1206"))
    )
    (comp (ref "C82")
      (value "100n")
      (footprint "eagle-import:C_1206")
      (libsource (lib "eagle-import") (part "C_1206"))
    )
    (comp (ref "C83")
      (value "100n")
      (footprint "eagle-import:C_1206")
      (libsource (lib "eagle-import") (part "C_1206"))
    )
    (comp (ref "C84")
      (value "100n")
      (footprint "eagle-import:C_1206")
      (libsource (lib "eagle-import") (part "C_1206"))
    )
    (comp (ref "C85")
      (value "100n")
      (footprint "eagle-import:C_1206")
      (libsource (lib "eagle-import") (part "C_1206"))
    )
    (comp (ref "C86")
      (value "100n")
      (footprint "eagle-import:C_1206")
      (libsource (lib "eagle-import") (part "C_1206"))
    )
    (comp (ref "C87")
      (value "100n")
      (footprint "eagle-import:C_1206")
      (libsource (lib "eagle-import") (part "C_1206"))
    )
    (comp (ref "C88")
      (value "100n")
      (footprint "eagle-import:C_1206")
      (libsource (lib "eagle-import") (part "C_1206"))
    )
    (comp (ref "C89")
      (value "100n")
      (footprint "eagle-import:C_1206")
      (libsource (lib "eagle-import") (part "C_1206"))
    )
    (comp (ref "C90")
      (value "100n")
      (footprint "eagle-import:C_1206")
      (libsource (lib "eagle-import") (part "C_1206"))
    )
    (comp (ref "C91")
      (value "100n")
      (footprint "eagle-import:C_1206")
      (libsource (lib "eagle-import") (part "C_1206"))
    )
    (comp (ref "C92")
      (value "100n")
      (footprint "eagle-import:C_1206")
      (libsource (lib "eagle-import") (part "C_1206"))
    )
    (comp (ref "C93")
      (value "100n")
      (footprint "eagle-import:C_1206")
      (libsource (lib "eagle-import") (part "C_1206"))
    )
    (comp (ref "C94")
      (value "47p")
      (footprint "eagle-import:C_1206")
      (libsource (lib "eagle-import") (part "C_1206"))
    )
    (comp (ref "C95")
      (value "47p")
      (footprint "eagle-import:C_1206")
      (libsource (lib "eagle-import") (part "C_1206"))
    )
    (comp (ref "C96")
      (value "100n")
      (footprint "eagle-import:C_1206")
      (libsource (lib "eagle-import") (part "C_1206"))
    )
    (comp (ref "C97")
      (value "4u7")
      (footprint "eagle-import:C_1206")
      (libsource (lib "eagle-import") (part "C_1206"))
    )
    (comp (ref "C98")
      (value "100n")
      (footprint "eagle-import:C_1206")
      (libsource (lib "eagle-import") (part "C_1206"))
    )
    (comp (ref "C101")
      (value "100n")
      (footprint "eagle-import:C_1206")
      (libsource (lib "eagle-import") (part "C_1206"))
    )
    (comp (ref "C102")
      (value "100n")
      (footprint "eagle-import:C_1206")
      (libsource (lib "eagle-import") (part "C_1206"))
    )
    (comp (ref "C103")
      (value "100n")
      (footprint "eagle-import:C_1206")
      (libsource (lib "eagle-import") (part "C_1206"))
    )
    (comp (ref "C104")
      (value "100n")
      (footprint "eagle-import:C_1206")
      (libsource (lib "eagle-import") (part "C_1206"))
    )
    (comp (ref "C105")
      (value "100n")
      (footprint "eagle-import:C_1206")
      (libsource (lib "eagle-import") (part "C_1206"))
    )
    (comp (ref "C106")
      (value "100n")
      (footprint "eagle-import:C_1206")
      (libsource (lib "eagle-import") (part "C_1206"))
    )
    (comp (ref "C107")
      (value "100n")
      (footprint "eagle-import:C_1206")
      (libsource (lib "eagle-import") (part "C_1206"))
    )
    (comp (ref "C108")
      (value "100n")
      (footprint "eagle-import:C_1206")
      (libsource (lib "eagle-import") (part "C_1206"))
    )
    (comp (ref "C109")
      (value "100n")
      (footprint "eagle-import:C_1206")
      (libsource (lib "eagle-import") (part "C_1206"))
    )
    (comp (ref "C112")
      (value "10u")
      (footprint "eagle-import:E2,5-5")
      (libsource (lib "eagle-import") (part "CPOL-EUE2.5-5"))
    )
    (comp (ref "C113")
      (value "10u")
      (footprint "eagle-import:E2,5-5")
      (libsource (lib "eagle-import") (part "CPOL-EUE2.5-5"))
    )
    (comp (ref "C114")
      (value "10u")
      (footprint "eagle-import:E2,5-5")
      (libsource (lib "eagle-import") (part "CPOL-EUE2.5-5"))
    )
    (comp (ref "C115")
      (value "10u")
      (footprint "eagle-import:E2,5-5")
      (libsource (lib "eagle-import") (part "CPOL-EUE2.5-5"))
    )
    (comp (ref "CFA5")
      (value "AD844_SOIC16R")
      (footprint "eagle-import:SOIC16R")
      (libsource (lib "eagle-import") (part "AD844_SOIC16R"))
    )
    (comp (ref "CONSTANT_SOURCES")
      (value "PINHD-2X3")
      (footprint "eagle-import:2X03")
      (libsource (lib "eagle-import") (part "PINHD-2X3"))
    )
    (comp (ref "H1")
      (value "MOUNT-HOLE3.0")
      (footprint "eagle-import:3,0")
      (libsource (lib "eagle-import") (part "MOUNT-HOLE3.0"))
    )
    (comp (ref "H2")
      (value "MOUNT-HOLE3.0")
      (footprint "eagle-import:3,0")
      (libsource (lib "eagle-import") (part "MOUNT-HOLE3.0"))
    )
    (comp (ref "H3")
      (value "MOUNT-HOLE3.0")
      (footprint "eagle-import:3,0")
      (libsource (lib "eagle-import") (part "MOUNT-HOLE3.0"))
    )
    (comp (ref "H4")
      (value "MOUNT-HOLE3.0")
      (footprint "eagle-import:3,0")
      (libsource (lib "eagle-import") (part "MOUNT-HOLE3.0"))
    )
    (comp (ref "IC1")
      (value "MEGA64-A")
      (footprint "eagle-import:TQFP64")
      (fields (field (name "MPN") "ATMEGA64-16AU"))
      (libsource (lib "eagle-import") (part "MEGA64-A"))
    )
    (comp (ref "IC2")
      (value "MEGA8-AI")
      (footprint "eagle-import:TQFP32-08")
      (fields (field (name "MPN") "ATMEGA8-16AU"))
      (libsource (lib "eagle-import") (part "MEGA8-AI"))
    )
    (comp (ref "IC3")
      (value "FT230XS")
      (footprint "eagle-import:SSOP16")
      (libsource (lib "eagle-import") (part "FT230XS"))
    )
    (comp (ref "IC_OUT")
      (value "PINHD-1X4")
      (footprint "eagle-import:1X04")
      (libsource (lib "eagle-import") (part "PINHD-1X4"))
    )
    (comp (ref "INVERTORS")
      (value "PINHD-2X4")
      (footprint "eagle-import:2X04")
      (libsource (lib "eagle-import") (part "PINHD-2X4"))
    )
    (comp (ref "JP62")
      (value "PINHD-2X3")
      (footprint "eagle-import:2X03")
      (libsource (lib "eagle-import") (part "PINHD-2X3"))
    )
    (comp (ref "JP63")
      (value "PINHD-2X3")
      (footprint "eagle-import:2X03")
      (libsource (lib "eagle-import") (part "PINHD-2X3"))
    )
    (comp (ref "JUMPER1")
      (value "PINHD-1X4")
      (footprint "eagle-import:1X04")
      (libsource (lib "eagle-import") (part "PINHD-1X4"))
    )
    (comp (ref "JUMPER2")
      (value "PINHD-1X4")
      (footprint "eagle-import:1X04")
      (libsource (lib "eagle-import") (part "PINHD-1X4"))
    )
    (comp (ref "JUMPER3")
      (value "PINHD-1X4")
      (footprint "eagle-import:1X04")
      (libsource (lib "eagle-import") (part "PINHD-1X4"))
    )
    (comp (ref "KEYPAD")
      (value "ADAFRUIT_3844")
      (footprint "eagle-import:1X08")
      (libsource (lib "eagle-import") (part "PINHD-1X8"))
    )
    (comp (ref "NON_INVERT_AMP")
      (value "PINHD-2X4")
      (footprint "eagle-import:2X04")
      (libsource (lib "eagle-import") (part "PINHD-2X4"))
    )
    (comp (ref "OA_LT1365")
      (value "PINHD-1X3")
      (footprint "eagle-import:1X03")
      (libsource (lib "eagle-import") (part "PINHD-1X3"))
    )
    (comp (ref "OLED_DISP")
      (value "I2C_SSH1106")
      (footprint "eagle-import:1X04")
      (libsource (lib "eagle-import") (part "PINHD-1X4"))
    )
    (comp (ref "PROG")
      (value "PINHD-2X3")
      (footprint "eagle-import:2X03")
      (libsource (lib "eagle-import") (part "PINHD-2X3"))
    )
    (comp (ref "PWL")
      (value "PINHD-1X2")
      (footprint "eagle-import:1X02")
      (libsource (lib "eagle-import") (part "PINHD-1X2"))
    )
    (comp (ref "Q1")
      (value "16MHz")
      (footprint "eagle-import:HC49_S")
      (libsource (lib "eagle-import") (part "CRYSTALHC49S"))
    )
    (comp (ref "Q2")
      (value "16MHz")
      (footprint "eagle-import:HC49_S")
      (libsource (lib "eagle-import") (part "CRYSTALHC49S"))
    )
    (comp (ref "R41")
      (value "10k")
      (footprint "eagle-import:R_1206")
      (libsource (lib "eagle-import") (part "R_1206"))
    )
    (comp (ref "R54")
      (value "10k")
      (footprint "eagle-import:R_1206")
      (libsource (lib "eagle-import") (part "R_1206"))
    )
    (comp (ref "R55")
      (value "10k")
      (footprint "eagle-import:R_1206")
      (libsource (lib "eagle-import") (part "R_1206"))
    )
    (comp (ref "R56")
      (value "27R")
      (footprint "eagle-import:R_1206")
      (libsource (lib "eagle-import") (part "R_1206"))
    )
    (comp (ref "R57")
      (value "27R")
      (footprint "eagle-import:R_1206")
      (libsource (lib "eagle-import") (part "R_1206"))
    )
    (comp (ref "R58")
      (value "4k7")
      (footprint "eagle-import:R_1206")
      (libsource (lib "eagle-import") (part "R_1206"))
    )
    (comp (ref "R59")
      (value "4k7")
      (footprint "eagle-import:R_1206")
      (libsource (lib "eagle-import") (part "R_1206"))
    )
    (comp (ref "R60")
      (value "10k")
      (footprint "eagle-import:R_1206")
      (libsource (lib "eagle-import") (part "R_1206"))
    )
    (comp (ref "R61")
      (value "10k")
      (footprint "eagle-import:R_1206")
      (libsource (lib "eagle-import") (part "R_1206"))
    )
    (comp (ref "R62")
      (value "10k")
      (footprint "eagle-import:R_1206")
      (libsource (lib "eagle-import") (part "R_1206"))
    )
    (comp (ref "R63")
      (value "10k")
      (footprint "eagle-import:R_1206")
      (libsource (lib "eagle-import") (part "R_1206"))
    )
    (comp (ref "R64")
      (value "10k")
      (footprint "eagle-import:R_1206")
      (libsource (lib "eagle-import") (part "R_1206"))
    )
    (comp (ref "R65")
      (value "10k")
      (footprint "eagle-import:R_1206")
      (libsource (lib "eagle-import") (part "R_1206"))
    )
    (comp (ref "R66")
      (value "10k")
      (footprint "eagle-import:R_1206")
      (libsource (lib "eagle-import") (part "R_1206"))
    )
    (comp (ref "R67")
      (value "10k")
      (footprint "eagle-import:R_1206")
      (libsource (lib "eagle-import") (part "R_1206"))
    )
    (comp (ref "R68")
      (value "10k")
      (footprint "eagle-import:R_1206")
      (libsource (lib "eagle-import") (part "R_1206"))
    )
    (comp (ref "R69")
      (value "10k")
      (footprint "eagle-import:R_1206")
      (libsource (lib "eagle-import") (part "R_1206"))
    )
    (comp (ref "R70")
      (value "10k")
      (footprint "eagle-import:R_1206")
      (libsource (lib "eagle-import") (part "R_1206"))
    )
    (comp (ref "R71")
      (value "10k")
      (footprint "eagle-import:R_1206")
      (libsource (lib "eagle-import") (part "R_1206"))
    )
    (comp (ref "R86")
      (value "EVUF3L")
      (footprint "eagle-import:EVUFXL")
      (libsource (lib "eagle-import") (part "EVULF3"))
    )
    (comp (ref "R87")
      (value "EVUF3L")
      (footprint "eagle-import:EVUFXL")
      (libsource (lib "eagle-import") (part "EVULF3"))
    )
    (comp (ref "R88")
      (value "EVUF3L")
      (footprint "eagle-import:EVUFXL")
      (libsource (lib "eagle-import") (part "EVULF3"))
    )
    (comp (ref "R89")
      (value "EVUF3L")
      (footprint "eagle-import:EVUFXL")
      (libsource (lib "eagle-import") (part "EVULF3"))
    )
    (comp (ref "R90")
      (value "EVUF3L")
      (footprint "eagle-import:EVUFXL")
      (libsource (lib "eagle-import") (part "EVULF3"))
    )
    (comp (ref "R91")
      (value "EVUF3L")
      (footprint "eagle-import:EVUFXL")
      (libsource (lib "eagle-import") (part "EVULF3"))
    )
    (comp (ref "R92")
      (value "EVUF3L")
      (footprint "eagle-import:EVUFXL")
      (libsource (lib "eagle-import") (part "EVULF3"))
    )
    (comp (ref "R93")
      (value "100R")
      (footprint "eagle-import:R_1206")
      (libsource (lib "eagle-import") (part "R_1206"))
    )
    (comp (ref "RDIG1")
      (value "PINHD-1X2")
      (footprint "eagle-import:1X02")
      (libsource (lib "eagle-import") (part "PINHD-1X2"))
    )
    (comp (ref "RDIG2")
      (value "PINHD-1X2")
      (footprint "eagle-import:1X02")
      (libsource (lib "eagle-import") (part "PINHD-1X2"))
    )
    (comp (ref "R_DIG_1")
      (value "MAXIM_MAX5437EUD+MAXIM_MAX5437EUD+_0_0")
      (footprint "eagle-import:MAXIM_MAX5437EUD+_0")
      (fields (field (name "MF") "Maxim") (field (name "MPN") "MAX5437EUD+"))
      (libsource (lib "eagle-import") (part "MAXIM_MAX5437EUD+MAXIM_MAX5437EUD+_0_0"))
    )
    (comp (ref "R_DIG_2")
      (value "MAXIM_MAX5437EUD+MAXIM_MAX5437EUD+_0_0")
      (footprint "eagle-import:MAXIM_MAX5437EUD+_0")
      (fields (field (name "MF") "Maxim") (field (name "MPN") "MAX5437EUD+"))
      (libsource (lib "eagle-import") (part "MAXIM_MAX5437EUD+MAXIM_MAX5437EUD+_0_0"))
    )
    (comp (ref "R_DIG_IC")
      (value "MAXIM_MAX5437EUD+MAXIM_MAX5437EUD+_0_0")
      (footprint "eagle-import:MAXIM_MAX5437EUD+_0")
      (fields (field (name "MF") "Maxim") (field (name "MPN") "MAX5437EUD+"))
      (libsource (lib "eagle-import") (part "MAXIM_MAX5437EUD+MAXIM_MAX5437EUD+_0_0"))
    )
    (comp (ref "R_DIG_PWL")
      (value "MAXIM_MAX5437EUD+MAXIM_MAX5437EUD+_0_0")
      (footprint "eagle-import:MAXIM_MAX5437EUD+_0")
      (fields (field (name "MF") "Maxim") (field (name "MPN") "MAX5437EUD+"))
      (libsource (lib "eagle-import") (part "MAXIM_MAX5437EUD+MAXIM_MAX5437EUD+_0_0"))
    )
    (comp (ref "S9")
      (value "320-938")
      (footprint "eagle-import:320-938")
      (libsource (lib "eagle-import") (part "320-938"))
    )
    (comp (ref "U$1")
      (value "MICRO-USBV2")
      (footprint "eagle-import:MICRO-USB-2")
      (libsource (lib "eagle-import") (part "MICRO-USBV2"))
    )
    (comp (ref "U2")
      (value "LT1365CS")
      (footprint "eagle-import:SO16")
      (libsource (lib "eagle-import") (part "LT1365CS"))
    )
    (comp (ref "U3")
      (value "LT1365CS")
      (footprint "eagle-import:SO16")
      (libsource (lib "eagle-import") (part "LT1365CS"))
    )
    (comp (ref "U4")
      (value "LT1365CS")
      (footprint "eagle-import:SO16")
      (libsource (lib "eagle-import") (part "LT1365CS"))
    )
  )
  (nets
    (net (code "1") (name "+5V") (class "Default")
      (node (ref "AD_OUT1") (pin "10") (pinfunction "VCC_10") (pintype "power_in"))
      (node (ref "AD_OUT1") (pin "11") (pinfunction "VDRIVE_11") (pintype "power_in"))
      (node (ref "AD_OUT2") (pin "10") (pinfunction "VCC_10") (pintype "power_in"))
      (node (ref "AD_OUT2") (pin "11") (pinfunction "VDRIVE_11") (pintype "power_in"))
      (node (ref "AD_PWL") (pin "10") (pinfunction "VCC_10") (pintype "power_in"))
      (node (ref "AD_PWL") (pin "11") (pinfunction "VDRIVE_11") (pintype "power_in"))
      (node (ref "C100") (pin "1") (pinfunction "1_1") (pintype "passive"))
      (node (ref "C29") (pin "1") (pinfunction "1_1") (pintype "passive"))
      (node (ref "C32") (pin "1") (pinfunction "1_1") (pintype "passive"))
      (node (ref "C35") (pin "1") (pinfunction "1_1") (pintype "passive"))
      (node (ref "C36") (pin "1") (pinfunction "1_1") (pintype "passive"))
      (node (ref "C37") (pin "1") (pinfunction "1_1") (pintype "passive"))
      (node (ref "C38") (pin "1") (pinfunction "1_1") (pintype "passive"))
      (node (ref "C43") (pin "1") (pinfunction "1_1") (pintype "passive"))
      (node (ref "C44") (pin "1") (pinfunction "1_1") (pintype "passive"))
      (node (ref "C45") (pin "1") (pinfunction "1_1") (pintype "passive"))
      (node (ref "C46") (pin "1") (pinfunction "1_1") (pintype "passive"))
      (node (ref "C51") (pin "1") (pinfunction "1_1") (pintype "passive"))
      (node (ref "C52") (pin "1") (pinfunction "1_1") (pintype "passive"))
      (node (ref "C53") (pin "1") (pinfunction "1_1") (pintype "passive"))
      (node (ref "C54") (pin "1") (pinfunction "1_1") (pintype "passive"))
      (node (ref "C82") (pin "1") (pinfunction "1_1") (pintype "passive"))
      (node (ref "C83") (pin "1") (pinfunction "1_1") (pintype "passive"))
      (node (ref "C84") (pin "1") (pinfunction "1_1") (pintype "passive"))
      (node (ref "C85") (pin "1") (pinfunction "1_1") (pintype "passive"))
      (node (ref "C86") (pin "1") (pinfunction "1_1") (pintype "passive"))
      (node (ref "C87") (pin "1") (pinfunction "1_1") (pintype "passive"))
      (node (ref "C90") (pin "1") (pinfunction "1_1") (pintype "passive"))
      (node (ref "C93") (pin "1") (pinfunction "1_1") (pintype "passive"))
      (node (ref "C96") (pin "1") (pinfunction "1_1") (pintype "passive"))
      (node (ref "C97") (pin "1") (pinfunction "1_1") (pintype "passive"))
      (node (ref "IC1") (pin "21") (pinfunction "VCC_21") (pintype "power_in"))
      (node (ref "IC1") (pin "52") (pinfunction "VCC_52") (pintype "power_in"))
      (node (ref "IC1") (pin "64") (pinfunction "AVCC_64") (pintype "power_in"))
      (node (ref "IC2") (pin "18") (pinfunction "AVCC_18") (pintype "power_in"))
      (node (ref "IC2") (pin "4") (pinfunction "VCC_4") (pintype "power_in"))
      (node (ref "IC2") (pin "6") (pinfunction "VCC_6") (pintype "power_in"))
      (node (ref "IC3") (pin "12") (pinfunction "VCC_12") (pintype "power_in"))
      (node (ref "IC4") (pin "OUT") (pinfunction "OUT_OUT") (pintype "passive"))
      (node (ref "OLED_DISP") (pin "2") (pinfunction "2_2") (pintype "passive"))
      (node (ref "PROG") (pin "2") (pinfunction "2_2") (pintype "passive"))
      (node (ref "R54") (pin "2") (pinfunction "2_2") (pintype "passive"))
      (node (ref "R55") (pin "2") (pinfunction "2_2") (pintype "passive"))
      (node (ref "R58") (pin "1") (pinfunction "1_1") (pintype "passive"))
      (node (ref "R59") (pin "1") (pinfunction "1_1") (pintype "passive"))
      (node (ref "R_DIG_1") (pin "14") (pinfunction "VCC_14") (pintype "power_in"))
      (node (ref "R_DIG_2") (pin "14") (pinfunction "VCC_14") (pintype "power_in"))
      (node (ref "R_DIG_IC") (pin "14") (pinfunction "VCC_14") (pintype "power_in"))
      (node (ref "R_DIG_PWL") (pin "14") (pinfunction "VCC_14") (pintype "power_in"))
      (node (ref "U$1") (pin "1") (pinfunction "VCC_1") (pintype "power_in"))
    )
    (net (code "2") (name "+15V") (class "Default")
      (node (ref "AD_OUT1") (pin "9") (pinfunction "VDD_9") (pintype "power_in"))
      (node (ref "AD_OUT2") (pin "9") (pinfunction "VDD_9") (pintype "power_in"))
      (node (ref "AD_PWL") (pin "9") (pinfunction "VDD_9") (pintype "power_in"))
      (node (ref "C101") (pin "1") (pinfunction "1_1") (pintype "passive"))
      (node (ref "C103") (pin "1") (pinfunction "1_1") (pintype "passive"))
      (node (ref "C105") (pin "1") (pinfunction "1_1") (pintype "passive"))
      (node (ref "C11") (pin "1") (pinfunction "1_1") (pintype "passive"))
      (node (ref "C110") (pin "+") (pinfunction "+_+") (pintype "passive"))
      (node (ref "C113") (pin "+") (pinfunction "+_+") (pintype "passive"))
      (node (ref "C114") (pin "+") (pinfunction "+_+") (pintype "passive"))
      (node (ref "C13") (pin "1") (pinfunction "1_1") (pintype "passive"))
      (node (ref "C15") (pin "1") (pinfunction "1_1") (pintype "passive"))
      (node (ref "C17") (pin "1") (pinfunction "1_1") (pintype "passive"))
      (node (ref "C19") (pin "1") (pinfunction "1_1") (pintype "passive"))
      (node (ref "C21") (pin "1") (pinfunction "1_1") (pintype "passive"))
      (node (ref "C23") (pin "1") (pinfunction "1_1") (pintype "passive"))
      (node (ref "C26") (pin "2") (pinfunction "2_2") (pintype "passive"))
      (node (ref "C27") (pin "1") (pinfunction "1_1") (pintype "passive"))
      (node (ref "C30") (pin "1") (pinfunction "1_1") (pintype "passive"))
      (node (ref "C34") (pin "1") (pinfunction "1_1") (pintype "passive"))
      (node (ref "C39") (pin "1") (pinfunction "1_1") (pintype "passive"))
      (node (ref "C42") (pin "1") (pinfunction "1_1") (pintype "passive"))
      (node (ref "C47") (pin "1") (pinfunction "1_1") (pintype "passive"))
      (node (ref "C5") (pin "1") (pinfunction "1_1") (pintype "passive"))
      (node (ref "C50") (pin "1") (pinfunction "1_1") (pintype "passive"))
      (node (ref "C55") (pin "1") (pinfunction "1_1") (pintype "passive"))
      (node (ref "C64") (pin "1") (pinfunction "1_1") (pintype "passive"))
      (node (ref "C7") (pin "1") (pinfunction "1_1") (pintype "passive"))
      (node (ref "C70") (pin "1") (pinfunction "1_1") (pintype "passive"))
      (node (ref "C76") (pin "1") (pinfunction "1_1") (pintype "passive"))
      (node (ref "C88") (pin "1") (pinfunction "1_1") (pintype "passive"))
      (node (ref "C9") (pin "1") (pinfunction "1_1") (pintype "passive"))
      (node (ref "C91") (pin "1") (pinfunction "1_1") (pintype "passive"))
      (node (ref "C99") (pin "1") (pinfunction "1_1") (pintype "passive"))
      (node (ref "CFA1") (pin "14") (pinfunction "7_14") (pintype "passive"))
      (node (ref "CFA2") (pin "14") (pinfunction "7_14") (pintype "passive"))
      (node (ref "CFA3") (pin "14") (pinfunction "7_14") (pintype "passive"))
      (node (ref "CFA4") (pin "14") (pinfunction "7_14") (pintype "passive"))
      (node (ref "CFA5") (pin "14") (pinfunction "7_14") (pintype "passive"))
      (node (ref "IC4") (pin "IN") (pinfunction "IN_IN") (pintype "input"))
      (node (ref "MLT1") (pin "6") (pinfunction "8_6") (pintype "power_in"))
      (node (ref "MLT2") (pin "6") (pinfunction "8_6") (pintype "power_in"))
      (node (ref "MLT3") (pin "6") (pinfunction "8_6") (pintype "power_in"))
      (node (ref "MLT4") (pin "6") (pinfunction "8_6") (pintype "power_in"))
      (node (ref "MLT5") (pin "6") (pinfunction "8_6") (pintype "power_in"))
      (node (ref "MLT6") (pin "6") (pinfunction "8_6") (pintype "power_in"))
      (node (ref "MLT7") (pin "6") (pinfunction "8_6") (pintype "power_in"))
      (node (ref "MLT8") (pin "6") (pinfunction "8_6") (pintype "power_in"))
      (node (ref "R86") (pin "1") (pinfunction "A_1") (pintype "passive"))
      (node (ref "R87") (pin "1") (pinfunction "A_1") (pintype "passive"))
      (node (ref "R88") (pin "1") (pinfunction "A_1") (pintype "passive"))
      (node (ref "R_DIG_1") (pin "10") (pinfunction "VDD_10") (pintype "power_in"))
      (node (ref "R_DIG_2") (pin "10") (pinfunction "VDD_10") (pintype "power_in"))
      (node (ref "R_DIG_IC") (pin "10") (pinfunction "VDD_10") (pintype "power_in"))
      (node (ref "R_DIG_IC") (pin "11") (pinfunction "H_11") (pintype "passive"))
      (node (ref "R_DIG_IC") (pin "4") (pinfunction "~{SHDN}_4") (pintype "input"))
      (node (ref "R_DIG_PWL") (pin "10") (pinfunction "VDD_10") (pintype "power_in"))
      (node (ref "U$3") (pin "S") (pinfunction "S_S") (pintype "passive"))
      (node (ref "U1") (pin "4") (pinfunction "V+_4") (pintype "power_in"))
      (node (ref "U2") (pin "4") (pinfunction "V+_4") (pintype "power_in"))
      (node (ref "U3") (pin "4") (pinfunction "V+_4") (pintype "power_in"))
      (node (ref "U4") (pin "4") (pinfunction "V+_4") (pintype "power_in"))
    )
    (net (code "3") (name "-15V") (class "Default")
      (node (ref "AD_OUT1") (pin "6") (pinfunction "VSS_6") (pintype "power_in"))
      (node (ref "AD_OUT2") (pin "6") (pinfunction "VSS_6") (pintype "power_in"))
      (node (ref "AD_PWL") (pin "6") (pinfunction "VSS_6") (pintype "power_in"))
      (node (ref "C10") (pin "1") (pinfunction "1_1") (pintype "passive"))
      (node (ref "C102") (pin "1") (pinfunction "1_1") (pintype "passive"))
      (node (ref "C104") (pin "1") (pinfunction "1_1") (pintype "passive"))
      (node (ref "C106") (pin "1") (pinfunction "1_1") (pintype "passive"))
      (node (ref "C111") (pin "-") (pinfunction "-_-") (pintype "passive"))
      (node (ref "C112") (pin "-") (pinfunction "-_-") (pintype "passive"))
      (node (ref "C115") (pin "-") (pinfunction "-_-") (pintype "passive"))
      (node (ref "C12") (pin "1") (pinfunction "1_1") (pintype "passive"))
      (node (ref "C14") (pin "1") (pinfunction "1_1") (pintype "passive"))
      (node (ref "C16") (pin "1") (pinfunction "1_1") (pintype "passive"))
      (node (ref "C18") (pin "1") (pinfunction "1_1") (pintype "passive"))
      (node (ref "C20") (pin "1") (pinfunction "1_1") (pintype "passive"))
      (node (ref "C22") (pin "1") (pinfunction "1_1") (pintype "passive"))
      (node (ref "C24") (pin "1") (pinfunction "1_1") (pintype "passive"))
      (node (ref "C25") (pin "2") (pinfunction "2_2") (pintype "passive"))
      (node (ref "C28") (pin "1") (pinfunction "1_1") (pintype "passive"))
      (node (ref "C31") (pin "1") (pinfunction "1_1") (pintype "passive"))
      (node (ref "C33") (pin "1") (pinfunction "1_1") (pintype "passive"))
      (node (ref "C40") (pin "1") (pinfunction "1_1") (pintype "passive"))
      (node (ref "C41") (pin "1") (pinfunction "1_1") (pintype "passive"))
      (node (ref "C48") (pin "1") (pinfunction "1_1") (pintype "passive"))
      (node (ref "C49") (pin "1") (pinfunction "1_1") (pintype "passive"))
      (node (ref "C56") (pin "1") (pinfunction "1_1") (pintype "passive"))
      (node (ref "C6") (pin "1") (pinfunction "1_1") (pintype "passive"))
      (node (ref "C65") (pin "1") (pinfunction "1_1") (pintype "passive"))
      (node (ref "C71") (pin "1") (pinfunction "1_1") (pintype "passive"))
      (node (ref "C77") (pin "1") (pinfunction "1_1") (pintype "passive"))
      (node (ref "C8") (pin "1") (pinfunction "1_1") (pintype "passive"))
      (node (ref "C89") (pin "1") (pinfunction "1_1") (pintype "passive"))
      (node (ref "C92") (pin "1") (pinfunction "1_1") (pintype "passive"))
      (node (ref "CFA1") (pin "7") (pinfunction "4_7") (pintype "passive"))
      (node (ref "CFA2") (pin "7") (pinfunction "4_7") (pintype "passive"))
      (node (ref "CFA3") (pin "7") (pinfunction "4_7") (pintype "passive"))
      (node (ref "CFA4") (pin "7") (pinfunction "4_7") (pintype "passive"))
      (node (ref "CFA5") (pin "7") (pinfunction "4_7") (pintype "passive"))
      (node (ref "MLT1") (pin "3") (pinfunction "5_3") (pintype "power_in"))
      (node (ref "MLT2") (pin "3") (pinfunction "5_3") (pintype "power_in"))
      (node (ref "MLT3") (pin "3") (pinfunction "5_3") (pintype "power_in"))
      (node (ref "MLT4") (pin "3") (pinfunction "5_3") (pintype "power_in"))
      (node (ref "MLT5") (pin "3") (pinfunction "5_3") (pintype "power_in"))
      (node (ref "MLT6") (pin "3") (pinfunction "5_3") (pintype "power_in"))
      (node (ref "MLT7") (pin "3") (pinfunction "5_3") (pintype "power_in"))
      (node (ref "MLT8") (pin "3") (pinfunction "5_3") (pintype "power_in"))
      (node (ref "R86") (pin "3") (pinfunction "E_3") (pintype "passive"))
      (node (ref "R87") (pin "3") (pinfunction "E_3") (pintype "passive"))
      (node (ref "R88") (pin "3") (pinfunction "E_3") (pintype "passive"))
      (node (ref "R_DIG_1") (pin "6") (pinfunction "VSS_6") (pintype "power_in"))
      (node (ref "R_DIG_2") (pin "6") (pinfunction "VSS_6") (pintype "power_in"))
      (node (ref "R_DIG_IC") (pin "13") (pinfunction "L_13") (pintype "passive"))
      (node (ref "R_DIG_IC") (pin "6") (pinfunction "VSS_6") (pintype "power_in"))
      (node (ref "R_DIG_PWL") (pin "6") (pinfunction "VSS_6") (pintype "power_in"))
      (node (ref "U$2") (pin "S") (pinfunction "S_S") (pintype "passive"))
      (node (ref "U1") (pin "13") (pinfunction "V-_13") (pintype "power_in"))
      (node (ref "U2") (pin "13") (pinfunction "V-_13") (pintype "power_in"))
      (node (ref "U3") (pin "13") (pinfunction "V-_13") (pintype "power_in"))
      (node (ref "U4") (pin "13") (pinfunction "V-_13") (pintype "power_in"))
    )
    (net (code "4") (name "AMP1_IN") (class "Default")
      (node (ref "NON_INVERT_AMP") (pin "1") (pinfunction "1_1") (pintype "passive"))
      (node (ref "U3") (pin "3") (pinfunction "+IN_3") (pintype "input"))
    )
    (net (code "5") (name "AMP1_OUT") (class "Default")
      (node (ref "NON_INVERT_AMP") (pin "2") (pinfunction "2_2") (pintype "passive"))
      (node (ref "R91") (pin "1") (pinfunction "A_1") (pintype "passive"))
      (node (ref "U3") (pin "1") (pinfunction "OUT_1") (pintype "output"))
    )
    (net (code "6") (name "AMP2_IN") (class "Default")
      (node (ref "NON_INVERT_AMP") (pin "3") (pinfunction "3_3") (pintype "passive"))
      (node (ref "U3") (pin "5") (pinfunction "+IN_5") (pintype "input"))
    )
    (net (code "7") (name "AMP2_OUT") (class "Default")
      (node (ref "NON_INVERT_AMP") (pin "4") (pinfunction "4_4") (pintype "passive"))
      (node (ref "R89") (pin "1") (pinfunction "A_1") (pintype "passive"))
      (node (ref "U3") (pin "7") (pinfunction "OUT_7") (pintype "output"))
    )
    (net (code "8") (name "AMP3_IN") (class "Default")
      (node (ref "NON_INVERT_AMP") (pin "5") (pinfunction "5_5") (pintype "passive"))
      (node (ref "U3") (pin "12") (pinfunction "+IN_12") (pintype "input"))
    )
    (net (code "9") (name "AMP3_OUT") (class "Default")
      (node (ref "NON_INVERT_AMP") (pin "6") (pinfunction "6_6") (pintype "passive"))
      (node (ref "R92") (pin "1") (pinfunction "A_1") (pintype "passive"))
      (node (ref "U3") (pin "10") (pinfunction "OUT_10") (pintype "output"))
    )
    (net (code "10") (name "AMP4_IN") (class "Default")
      (node (ref "NON_INVERT_AMP") (pin "7") (pinfunction "7_7") (pintype "passive"))
      (node (ref "U3") (pin "14") (pinfunction "+IN_14") (pintype "input"))
    )
    (net (code "11") (name "AMP4_OUT") (class "Default")
      (node (ref "NON_INVERT_AMP") (pin "8") (pinfunction "8_8") (pintype "passive"))
      (node (ref "R90") (pin "1") (pinfunction "A_1") (pintype "passive"))
      (node (ref "U3") (pin "16") (pinfunction "OUT_16") (pintype "output"))
    )
    (net (code "12") (name "BNC_AD_OUT_W") (class "Default")
      (node (ref "AD_OUT2") (pin "8") (pinfunction "VIN1_8") (pintype "input"))
      (node (ref "INTEG_OUT_W") (pin "20") (pinfunction "20_20") (pintype "passive"))
      (node (ref "X8") (pin "1") (pinfunction "1_1") (pintype "passive"))
    )
    (net (code "13") (name "BNC_AD_OUT_X") (class "Default")
      (node (ref "AD_OUT1") (pin "7") (pinfunction "VIN0_7") (pintype "input"))
      (node (ref "INTEG_OUT_X") (pin "20") (pinfunction "20_20") (pintype "passive"))
      (node (ref "X5") (pin "1") (pinfunction "1_1") (pintype "passive"))
    )
    (net (code "14") (name "BNC_AD_OUT_Y") (class "Default")
      (node (ref "AD_OUT1") (pin "8") (pinfunction "VIN1_8") (pintype "input"))
      (node (ref "INTEG_OUT_Y") (pin "20") (pinfunction "20_20") (pintype "passive"))
      (node (ref "X6") (pin "1") (pinfunction "1_1") (pintype "passive"))
    )
    (net (code "15") (name "BNC_AD_OUT_Z") (class "Default")
      (node (ref "AD_OUT2") (pin "7") (pinfunction "VIN0_7") (pintype "input"))
      (node (ref "INTEG_OUT_Z") (pin "20") (pinfunction "20_20") (pintype "passive"))
      (node (ref "X7") (pin "1") (pinfunction "1_1") (pintype "passive"))
    )
    (net (code "16") (name "CLK") (class "Default")
      (node (ref "JP62") (pin "3") (pinfunction "3_3") (pintype "passive"))
      (node (ref "PROG") (pin "3") (pinfunction "3_3") (pintype "passive"))
    )
    (net (code "17") (name "CNST_SRC_1") (class "Default")
      (node (ref "CONSTANT_SOURCES") (pin "1") (pinfunction "1_1") (pintype "passive"))
      (node (ref "CONSTANT_SOURCES") (pin "2") (pinfunction "2_2") (pintype "passive"))
      (node (ref "U4") (pin "6") (pinfunction "-IN_6") (pintype "input"))
      (node (ref "U4") (pin "7") (pinfunction "OUT_7") (pintype "output"))
    )
    (net (code "18") (name "CNST_SRC_2") (class "Default")
      (node (ref "CONSTANT_SOURCES") (pin "3") (pinfunction "3_3") (pintype "passive"))
      (node (ref "CONSTANT_SOURCES") (pin "4") (pinfunction "4_4") (pintype "passive"))
      (node (ref "U4") (pin "10") (pinfunction "OUT_10") (pintype "output"))
      (node (ref "U4") (pin "11") (pinfunction "-IN_11") (pintype "input"))
    )
    (net (code "19") (name "CNST_SRC_3") (class "Default")
      (node (ref "CONSTANT_SOURCES") (pin "5") (pinfunction "5_5") (pintype "passive"))
      (node (ref "CONSTANT_SOURCES") (pin "6") (pinfunction "6_6") (pintype "passive"))
      (node (ref "U4") (pin "15") (pinfunction "-IN_15") (pintype "input"))
      (node (ref "U4") (pin "16") (pinfunction "OUT_16") (pintype "output"))
    )
    (net (code "20") (name "CORE_RESET") (class "Default")
      (node (ref "IC1") (pin "20") (pinfunction "RESET_20") (pintype "input"))
      (node (ref "JP62") (pin "2") (pinfunction "2_2") (pintype "passive"))
      (node (ref "R54") (pin "1") (pinfunction "1_1") (pintype "passive"))
    )
    (net (code "21") (name "C_W") (class "Default")
      (node (ref "S4") (pin "P$C") (pinfunction "C_P$C") (pintype "passive"))
      (node (ref "U$4") (pin "P$11") (pinfunction "11_P$11") (pintype "passive"))
    )
    (net (code "22") (name "C_X") (class "Default")
      (node (ref "S1") (pin "P$C") (pinfunction "C_P$C") (pintype "passive"))
      (node (ref "U$4") (pin "P$02") (pinfunction "2_P$02") (pintype "passive"))
    )
    (net (code "23") (name "C_Y") (class "Default")
      (node (ref "S2") (pin "P$C") (pinfunction "C_P$C") (pintype "passive"))
      (node (ref "U$4") (pin "P$05") (pinfunction "5_P$05") (pintype "passive"))
    )
    (net (code "24") (name "C_Z") (class "Default")
      (node (ref "S3") (pin "P$C") (pinfunction "C_P$C") (pintype "passive"))
      (node (ref "U$4") (pin "P$08") (pinfunction "8_P$08") (pintype "passive"))
    )
    (net (code "25") (name "DATA+") (class "Default")
      (node (ref "C94") (pin "1") (pinfunction "1_1") (pintype "passive"))
      (node (ref "R56") (pin "2") (pinfunction "2_2") (pintype "passive"))
      (node (ref "U$1") (pin "3") (pinfunction "D+_3") (pintype "bidirectional"))
    )
    (net (code "26") (name "DATA-") (class "Default")
      (node (ref "C95") (pin "1") (pinfunction "1_1") (pintype "passive"))
      (node (ref "R57") (pin "2") (pinfunction "2_2") (pintype "passive"))
      (node (ref "U$1") (pin "2") (pinfunction "D-_2") (pintype "bidirectional"))
    )
    (net (code "27") (name "FTRST") (class "Default")
      (node (ref "C98") (pin "1") (pinfunction "1_1") (pintype "passive"))
      (node (ref "IC3") (pin "10") (pinfunction "3V3OUT_10") (pintype "output"))
      (node (ref "IC3") (pin "11") (pinfunction "~{RESET}_11") (pintype "input"))
      (node (ref "IC3") (pin "3") (pinfunction "VCCIO_3") (pintype "power_in"))
    )
    (net (code "28") (name "GND") (class "Default")
      (node (ref "AD_OUT1") (pin "13") (pinfunction "DGND_13") (pintype "power_in"))
      (node (ref "AD_OUT1") (pin "3") (pinfunction "DGND_3") (pintype "power_in"))
      (node (ref "AD_OUT1") (pin "4") (pinfunction "AGND_4") (pintype "power_in"))
      (node (ref "AD_OUT2") (pin "13") (pinfunction "DGND_13") (pintype "power_in"))
      (node (ref "AD_OUT2") (pin "3") (pinfunction "DGND_3") (pintype "power_in"))
      (node (ref "AD_OUT2") (pin "4") (pinfunction "AGND_4") (pintype "power_in"))
      (node (ref "AD_PWL") (pin "13") (pinfunction "DGND_13") (pintype "power_in"))
      (node (ref "AD_PWL") (pin "3") (pinfunction "DGND_3") (pintype "power_in"))
      (node (ref "AD_PWL") (pin "4") (pinfunction "AGND_4") (pintype "power_in"))
      (node (ref "AD_PWL") (pin "8") (pinfunction "VIN1_8") (pintype "input"))
      (node (ref "C1") (pin "2") (pinfunction "2_2") (pintype "passive"))
      (node (ref "C10") (pin "2") (pinfunction "2_2") (pintype "passive"))
      (node (ref "C100") (pin "2") (pinfunction "2_2") (pintype "passive"))
      (node (ref "C101") (pin "2") (pinfunction "2_2") (pintype "passive"))
      (node (ref "C102") (pin "2") (pinfunction "2_2") (pintype "passive"))
      (node (ref "C103") (pin "2") (pinfunction "2_2") (pintype "passive"))
      (node (ref "C104") (pin "2") (pinfunction "2_2") (pintype "passive"))
      (node (ref "C105") (pin "2") (pinfunction "2_2") (pintype "passive"))
      (node (ref "C106") (pin "2") (pinfunction "2_2") (pintype "passive"))
      (node (ref "C107") (pin "2") (pinfunction "2_2") (pintype "passive"))
      (node (ref "C108") (pin "2") (pinfunction "2_2") (pintype "passive"))
      (node (ref "C109") (pin "2") (pinfunction "2_2") (pintype "passive"))
      (node (ref "C11") (pin "2") (pinfunction "2_2") (pintype "passive"))
      (node (ref "C110") (pin "-") (pinfunction "-_-") (pintype "passive"))
      (node (ref "C111") (pin "+") (pinfunction "+_+") (pintype "passive"))
      (node (ref "C112") (pin "+") (pinfunction "+_+") (pintype "passive"))
      (node (ref "C113") (pin "-") (pinfunction "-_-") (pintype "passive"))
      (node (ref "C114") (pin "-") (pinfunction "-_-") (pintype "passive"))
      (node (ref "C115") (pin "+") (pinfunction "+_+") (pintype "passive"))
      (node (ref "C12") (pin "2") (pinfunction "2_2") (pintype "passive"))
      (node (ref "C13") (pin "2") (pinfunction "2_2") (pintype "passive"))
      (node (ref "C14") (pin "2") (pinfunction "2_2") (pintype "passive"))
      (node (ref "C15") (pin "2") (pinfunction "2_2") (pintype "passive"))
      (node (ref "C16") (pin "2") (pinfunction "2_2") (pintype "passive"))
      (node (ref "C17") (pin "2") (pinfunction "2_2") (pintype "passive"))
      (node (ref "C18") (pin "2") (pinfunction "2_2") (pintype "passive"))
      (node (ref "C19") (pin "2") (pinfunction "2_2") (pintype "passive"))
      (node (ref "C2") (pin "2") (pinfunction "2_2") (pintype "passive"))
      (node (ref "C20") (pin "2") (pinfunction "2_2") (pintype "passive"))
      (node (ref "C21") (pin "2") (pinfunction "2_2") (pintype "passive"))
      (node (ref "C22") (pin "2") (pinfunction "2_2") (pintype "passive"))
      (node (ref "C23") (pin "2") (pinfunction "2_2") (pintype "passive"))
      (node (ref "C24") (pin "2") (pinfunction "2_2") (pintype "passive"))
      (node (ref "C25") (pin "1") (pinfunction "1_1") (pintype "passive"))
      (node (ref "C26") (pin "1") (pinfunction "1_1") (pintype "passive"))
      (node (ref "C27") (pin "2") (pinfunction "2_2") (pintype "passive"))
      (node (ref "C28") (pin "2") (pinfunction "2_2") (pintype "passive"))
      (node (ref "C29") (pin "2") (pinfunction "2_2") (pintype "passive"))
      (node (ref "C3") (pin "2") (pinfunction "2_2") (pintype "passive"))
      (node (ref "C30") (pin "2") (pinfunction "2_2") (pintype "passive"))
      (node (ref "C31") (pin "2") (pinfunction "2_2") (pintype "passive"))
      (node (ref "C32") (pin "2") (pinfunction "2_2") (pintype "passive"))
      (node (ref "C33") (pin "2") (pinfunction "2_2") (pintype "passive"))
      (node (ref "C34") (pin "2") (pinfunction "2_2") (pintype "passive"))
      (node (ref "C35") (pin "2") (pinfunction "2_2") (pintype "passive"))
      (node (ref "C36") (pin "2") (pinfunction "2_2") (pintype "passive"))
      (node (ref "C37") (pin "2") (pinfunction "2_2") (pintype "passive"))
      (node (ref "C38") (pin "2") (pinfunction "2_2") (pintype "passive"))
      (node (ref "C39") (pin "2") (pinfunction "2_2") (pintype "passive"))
      (node (ref "C4") (pin "2") (pinfunction "2_2") (pintype "passive"))
      (node (ref "C40") (pin "2") (pinfunction "2_2") (pintype "passive"))
      (node (ref "C41") (pin "2") (pinfunction "2_2") (pintype "passive"))
      (node (ref "C42") (pin "2") (pinfunction "2_2") (pintype "passive"))
      (node (ref "C43") (pin "2") (pinfunction "2_2") (pintype "passive"))
      (node (ref "C44") (pin "2") (pinfunction "2_2") (pintype "passive"))
      (node (ref "C45") (pin "2") (pinfunction "2_2") (pintype "passive"))
      (node (ref "C46") (pin "2") (pinfunction "2_2") (pintype "passive"))
      (node (ref "C47") (pin "2") (pinfunction "2_2") (pintype "passive"))
      (node (ref "C48") (pin "2") (pinfunction "2_2") (pintype "passive"))
      (node (ref "C49") (pin "2") (pinfunction "2_2") (pintype "passive"))
      (node (ref "C5") (pin "2") (pinfunction "2_2") (pintype "passive"))
      (node (ref "C50") (pin "2") (pinfunction "2_2") (pintype "passive"))
      (node (ref "C51") (pin "2") (pinfunction "2_2") (pintype "passive"))
      (node (ref "C52") (pin "2") (pinfunction "2_2") (pintype "passive"))
      (node (ref "C53") (pin "2") (pinfunction "2_2") (pintype "passive"))
      (node (ref "C54") (pin "2") (pinfunction "2_2") (pintype "passive"))
      (node (ref "C55") (pin "2") (pinfunction "2_2") (pintype "passive"))
      (node (ref "C56") (pin "2") (pinfunction "2_2") (pintype "passive"))
      (node (ref "C57") (pin "2") (pinfunction "2_2") (pintype "passive"))
      (node (ref "C58") (pin "2") (pinfunction "2_2") (pintype "passive"))
      (node (ref "C59") (pin "2") (pinfunction "2_2") (pintype "passive"))
      (node (ref "C6") (pin "2") (pinfunction "2_2") (pintype "passive"))
      (node (ref "C60") (pin "2") (pinfunction "2_2") (pintype "passive"))
      (node (ref "C61") (pin "2") (pinfunction "2_2") (pintype "passive"))
      (node (ref "C62") (pin "2") (pinfunction "2_2") (pintype "passive"))
      (node (ref "C63") (pin "2") (pinfunction "2_2") (pintype "passive"))
      (node (ref "C64") (pin "2") (pinfunction "2_2") (pintype "passive"))
      (node (ref "C65") (pin "2") (pinfunction "2_2") (pintype "passive"))
      (node (ref "C66") (pin "2") (pinfunction "2_2") (pintype "passive"))
      (node (ref "C67") (pin "2") (pinfunction "2_2") (pintype "passive"))
      (node (ref "C68") (pin "2") (pinfunction "2_2") (pintype "passive"))
      (node (ref "C69") (pin "2") (pinfunction "2_2") (pintype "passive"))
      (node (ref "C7") (pin "2") (pinfunction "2_2") (pintype "passive"))
      (node (ref "C70") (pin "2") (pinfunction "2_2") (pintype "passive"))
      (node (ref "C71") (pin "2") (pinfunction "2_2") (pintype "passive"))
      (node (ref "C72") (pin "2") (pinfunction "2_2") (pintype "passive"))
      (node (ref "C73") (pin "2") (pinfunction "2_2") (pintype "passive"))
      (node (ref "C74") (pin "2") (pinfunction "2_2") (pintype "passive"))
      (node (ref "C75") (pin "2") (pinfunction "2_2") (pintype "passive"))
      (node (ref "C76") (pin "2") (pinfunction "2_2") (pintype "passive"))
      (node (ref "C77") (pin "2") (pinfunction "2_2") (pintype "passive"))
      (node (ref "C78") (pin "1") (pinfunction "1_1") (pintype "passive"))
      (node (ref "C79") (pin "1") (pinfunction "1_1") (pintype "passive"))
      (node (ref "C8") (pin "2") (pinfunction "2_2") (pintype "passive"))
      (node (ref "C80") (pin "2") (pinfunction "2_2") (pintype "passive"))
      (node (ref "C81") (pin "2") (pinfunction "2_2") (pintype "passive"))
      (node (ref "C82") (pin "2") (pinfunction "2_2") (pintype "passive"))
      (node (ref "C83") (pin "2") (pinfunction "2_2") (pintype "passive"))
      (node (ref "C84") (pin "2") (pinfunction "2_2") (pintype "passive"))
      (node (ref "C85") (pin "2") (pinfunction "2_2") (pintype "passive"))
      (node (ref "C86") (pin "2") (pinfunction "2_2") (pintype "passive"))
      (node (ref "C87") (pin "2") (pinfunction "2_2") (pintype "passive"))
      (node (ref "C88") (pin "2") (pinfunction "2_2") (pintype "passive"))
      (node (ref "C89") (pin "2") (pinfunction "2_2") (pintype "passive"))
      (node (ref "C9") (pin "2") (pinfunction "2_2") (pintype "passive"))
      (node (ref "C90") (pin "2") (pinfunction "2_2") (pintype "passive"))
      (node (ref "C91") (pin "2") (pinfunction "2_2") (pintype "passive"))
      (node (ref "C92") (pin "2") (pinfunction "2_2") (pintype "passive"))
      (node (ref "C93") (pin "2") (pinfunction "2_2") (pintype "passive"))
      (node (ref "C94") (pin "2") (pinfunction "2_2") (pintype "passive"))
      (node (ref "C95") (pin "2") (pinfunction "2_2") (pintype "passive"))
      (node (ref "C96") (pin "2") (pinfunction "2_2") (pintype "passive"))
      (node (ref "C97") (pin "2") (pinfunction "2_2") (pintype "passive"))
      (node (ref "C98") (pin "2") (pinfunction "2_2") (pintype "passive"))
      (node (ref "C99") (pin "2") (pinfunction "2_2") (pintype "passive"))
      (node (ref "C_EXT_W") (pin "2") (pinfunction "2_2") (pintype "passive"))
      (node (ref "C_EXT_X") (pin "2") (pinfunction "2_2") (pintype "passive"))
      (node (ref "C_EXT_Y") (pin "2") (pinfunction "2_2") (pintype "passive"))
      (node (ref "C_EXT_Z") (pin "2") (pinfunction "2_2") (pintype "passive"))
      (node (ref "D1") (pin "C") (pinfunction "C_C") (pintype "passive"))
      (node (ref "D2") (pin "A") (pinfunction "A_A") (pintype "passive"))
      (node (ref "IC1") (pin "22") (pinfunction "GND_22") (pintype "power_in"))
      (node (ref "IC1") (pin "53") (pinfunction "GND_53") (pintype "power_in"))
      (node (ref "IC1") (pin "63") (pinfunction "GND_63") (pintype "power_in"))
      (node (ref "IC2") (pin "21") (pinfunction "GND_21") (pintype "power_in"))
      (node (ref "IC2") (pin "3") (pinfunction "GND_3") (pintype "power_in"))
      (node (ref "IC2") (pin "5") (pinfunction "GND_5") (pintype "power_in"))
      (node (ref "IC3") (pin "13") (pinfunction "GND_13") (pintype "power_in"))
      (node (ref "IC3") (pin "5") (pinfunction "GND_5") (pintype "power_in"))
      (node (ref "IC4") (pin "GND") (pinfunction "GND_GND") (pintype "input"))
      (node (ref "JP39") (pin "2") (pinfunction "2_2") (pintype "passive"))
      (node (ref "JP40") (pin "2") (pinfunction "2_2") (pintype "passive"))
      (node (ref "JP41") (pin "2") (pinfunction "2_2") (pintype "passive"))
      (node (ref "JP42") (pin "2") (pinfunction "2_2") (pintype "passive"))
      (node (ref "MULT_IN_1") (pin "1") (pinfunction "1_1") (pintype "passive"))
      (node (ref "MULT_IN_1") (pin "3") (pinfunction "3_3") (pintype "passive"))
      (node (ref "MULT_IN_1") (pin "5") (pinfunction "5_5") (pintype "passive"))
      (node (ref "MULT_IN_1") (pin "7") (pinfunction "7_7") (pintype "passive"))
      (node (ref "MULT_IN_2") (pin "1") (pinfunction "1_1") (pintype "passive"))
      (node (ref "MULT_IN_2") (pin "3") (pinfunction "3_3") (pintype "passive"))
      (node (ref "MULT_IN_2") (pin "5") (pinfunction "5_5") (pintype "passive"))
      (node (ref "MULT_IN_2") (pin "7") (pinfunction "7_7") (pintype "passive"))
      (node (ref "MULT_IN_3") (pin "1") (pinfunction "1_1") (pintype "passive"))
      (node (ref "MULT_IN_3") (pin "3") (pinfunction "3_3") (pintype "passive"))
      (node (ref "MULT_IN_3") (pin "5") (pinfunction "5_5") (pintype "passive"))
      (node (ref "MULT_IN_3") (pin "7") (pinfunction "7_7") (pintype "passive"))
      (node (ref "MULT_IN_4") (pin "1") (pinfunction "1_1") (pintype "passive"))
      (node (ref "MULT_IN_4") (pin "3") (pinfunction "3_3") (pintype "passive"))
      (node (ref "MULT_IN_4") (pin "5") (pinfunction "5_5") (pintype "passive"))
      (node (ref "MULT_IN_4") (pin "7") (pinfunction "7_7") (pintype "passive"))
      (node (ref "MULT_IN_5") (pin "1") (pinfunction "1_1") (pintype "passive"))
      (node (ref "MULT_IN_5") (pin "3") (pinfunction "3_3") (pintype "passive"))
      (node (ref "MULT_IN_5") (pin "5") (pinfunction "5_5") (pintype "passive"))
      (node (ref "MULT_IN_5") (pin "7") (pinfunction "7_7") (pintype "passive"))
      (node (ref "MULT_IN_6") (pin "1") (pinfunction "1_1") (pintype "passive"))
      (node (ref "MULT_IN_6") (pin "3") (pinfunction "3_3") (pintype "passive"))
      (node (ref "MULT_IN_6") (pin "5") (pinfunction "5_5") (pintype "passive"))
      (node (ref "MULT_IN_6") (pin "7") (pinfunction "7_7") (pintype "passive"))
      (node (ref "MULT_IN_7") (pin "1") (pinfunction "1_1") (pintype "passive"))
      (node (ref "MULT_IN_7") (pin "3") (pinfunction "3_3") (pintype "passive"))
      (node (ref "MULT_IN_7") (pin "5") (pinfunction "5_5") (pintype "passive"))
      (node (ref "MULT_IN_7") (pin "7") (pinfunction "7_7") (pintype "passive"))
      (node (ref "MULT_IN_8") (pin "1") (pinfunction "1_1") (pintype "passive"))
      (node (ref "MULT_IN_8") (pin "3") (pinfunction "3_3") (pintype "passive"))
      (node (ref "MULT_IN_8") (pin "5") (pinfunction "5_5") (pintype "passive"))
      (node (ref "MULT_IN_8") (pin "7") (pinfunction "7_7") (pintype "passive"))
      (node (ref "MULT_OUT_1") (pin "4") (pinfunction "4_4") (pintype "passive"))
      (node (ref "MULT_OUT_2") (pin "4") (pinfunction "4_4") (pintype "passive"))
      (node (ref "MULT_OUT_3") (pin "4") (pinfunction "4_4") (pintype "passive"))
      (node (ref "MULT_OUT_4") (pin "4") (pinfunction "4_4") (pintype "passive"))
      (node (ref "MULT_OUT_5") (pin "4") (pinfunction "4_4") (pintype "passive"))
      (node (ref "MULT_OUT_6") (pin "4") (pinfunction "4_4") (pintype "passive"))
      (node (ref "MULT_OUT_7") (pin "4") (pinfunction "4_4") (pintype "passive"))
      (node (ref "MULT_OUT_8") (pin "4") (pinfunction "4_4") (pintype "passive"))
      (node (ref "OLED_DISP") (pin "1") (pinfunction "1_1") (pintype "passive"))
      (node (ref "PROG") (pin "1") (pinfunction "1_1") (pintype "passive"))
      (node (ref "PWR") (pin "2") (pinfunction "2_2") (pintype "passive"))
      (node (ref "R68") (pin "2") (pinfunction "2_2") (pintype "passive"))
      (node (ref "R69") (pin "2") (pinfunction "2_2") (pintype "passive"))
      (node (ref "R70") (pin "2") (pinfunction "2_2") (pintype "passive"))
      (node (ref "R71") (pin "2") (pinfunction "2_2") (pintype "passive"))
      (node (ref "R72") (pin "2") (pinfunction "2_2") (pintype "passive"))
      (node (ref "R73") (pin "2") (pinfunction "2_2") (pintype "passive"))
      (node (ref "R74") (pin "3") (pinfunction "E_3") (pintype "passive"))
      (node (ref "R75") (pin "3") (pinfunction "E_3") (pintype "passive"))
      (node (ref "R76") (pin "3") (pinfunction "E_3") (pintype "passive"))
      (node (ref "R78") (pin "3") (pinfunction "E_3") (pintype "passive"))
      (node (ref "R79") (pin "3") (pinfunction "E_3") (pintype "passive"))
      (node (ref "R81") (pin "3") (pinfunction "E_3") (pintype "passive"))
      (node (ref "R82") (pin "3") (pinfunction "E_3") (pintype "passive"))
      (node (ref "R83") (pin "3") (pinfunction "E_3") (pintype "passive"))
      (node (ref "R84") (pin "3") (pinfunction "E_3") (pintype "passive"))
      (node (ref "R85") (pin "3") (pinfunction "E_3") (pintype "passive"))
      (node (ref "R94") (pin "2") (pinfunction "2_2") (pintype "passive"))
      (node (ref "R95") (pin "2") (pinfunction "2_2") (pintype "passive"))
      (node (ref "R96") (pin "2") (pinfunction "2_2") (pintype "passive"))
      (node (ref "R97") (pin "2") (pinfunction "2_2") (pintype "passive"))
      (node (ref "R_DIG_1") (pin "13") (pinfunction "L_13") (pintype "passive"))
      (node (ref "R_DIG_1") (pin "5") (pinfunction "GND_5") (pintype "power_in"))
      (node (ref "R_DIG_2") (pin "13") (pinfunction "L_13") (pintype "passive"))
      (node (ref "R_DIG_2") (pin "5") (pinfunction "GND_5") (pintype "power_in"))
      (node (ref "R_DIG_IC") (pin "5") (pinfunction "GND_5") (pintype "power_in"))
      (node (ref "R_DIG_PWL") (pin "12") (pinfunction "W_12") (pintype "passive"))
      (node (ref "R_DIG_PWL") (pin "13") (pinfunction "L_13") (pintype "passive"))
      (node (ref "R_DIG_PWL") (pin "4") (pinfunction "~{SHDN}_4") (pintype "input"))
      (node (ref "R_DIG_PWL") (pin "5") (pinfunction "GND_5") (pintype "power_in"))
      (node (ref "S5") (pin "1") (pinfunction "O_1") (pintype "passive"))
      (node (ref "S5") (pin "6") (pinfunction "S_6") (pintype "passive"))
      (node (ref "S6") (pin "1") (pinfunction "O_1") (pintype "passive"))
      (node (ref "S6") (pin "6") (pinfunction "S_6") (pintype "passive"))
      (node (ref "S7") (pin "1") (pinfunction "O_1") (pintype "passive"))
      (node (ref "S7") (pin "6") (pinfunction "S_6") (pintype "passive"))
      (node (ref "S8") (pin "1") (pinfunction "O_1") (pintype "passive"))
      (node (ref "S8") (pin "6") (pinfunction "S_6") (pintype "passive"))
      (node (ref "S9") (pin "1") (pinfunction "O_1") (pintype "passive"))
      (node (ref "S9") (pin "6") (pinfunction "S_6") (pintype "passive"))
      (node (ref "U$1") (pin "5") (pinfunction "GND_5") (pintype "power_in"))
      (node (ref "U$1") (pin "P$1") (pinfunction "GND_P$1") (pintype "power_in"))
      (node (ref "U$1") (pin "P$2") (pinfunction "GND_P$2") (pintype "power_in"))
      (node (ref "U$1") (pin "P$3") (pinfunction "GND_P$3") (pintype "power_in"))
      (node (ref "U$1") (pin "P$4") (pinfunction "GND_P$4") (pintype "power_in"))
      (node (ref "U1") (pin "12") (pinfunction "+IN_12") (pintype "input"))
      (node (ref "U1") (pin "14") (pinfunction "+IN_14") (pintype "input"))
      (node (ref "U1") (pin "3") (pinfunction "+IN_3") (pintype "input"))
      (node (ref "U1") (pin "5") (pinfunction "+IN_5") (pintype "input"))
      (node (ref "U2") (pin "12") (pinfunction "+IN_12") (pintype "input"))
      (node (ref "U2") (pin "14") (pinfunction "+IN_14") (pintype "input"))
      (node (ref "U2") (pin "3") (pinfunction "+IN_3") (pintype "input"))
      (node (ref "U2") (pin "5") (pinfunction "+IN_5") (pintype "input"))
      (node (ref "X1") (pin "2") (pinfunction "2_2") (pintype "passive"))
      (node (ref "X1") (pin "3") (pinfunction "2_3") (pintype "passive"))
      (node (ref "X1") (pin "4") (pinfunction "2_4") (pintype "passive"))
      (node (ref "X1") (pin "5") (pinfunction "2_5") (pintype "passive"))
      (node (ref "X2") (pin "2") (pinfunction "2_2") (pintype "passive"))
      (node (ref "X2") (pin "3") (pinfunction "2_3") (pintype "passive"))
      (node (ref "X2") (pin "4") (pinfunction "2_4") (pintype "passive"))
      (node (ref "X2") (pin "5") (pinfunction "2_5") (pintype "passive"))
      (node (ref "X3") (pin "2") (pinfunction "2_2") (pintype "passive"))
      (node (ref "X3") (pin "3") (pinfunction "2_3") (pintype "passive"))
      (node (ref "X3") (pin "4") (pinfunction "2_4") (pintype "passive"))
      (node (ref "X3") (pin "5") (pinfunction "2_5") (pintype "passive"))
      (node (ref "X4") (pin "2") (pinfunction "2_2") (pintype "passive"))
      (node (ref "X4") (pin "3") (pinfunction "2_3") (pintype "passive"))
      (node (ref "X4") (pin "4") (pinfunction "2_4") (pintype "passive"))
      (node (ref "X4") (pin "5") (pinfunction "2_5") (pintype "passive"))
      (node (ref "X5") (pin "2") (pinfunction "2_2") (pintype "passive"))
      (node (ref "X5") (pin "3") (pinfunction "2_3") (pintype "passive"))
      (node (ref "X5") (pin "4") (pinfunction "2_4") (pintype "passive"))
      (node (ref "X5") (pin "5") (pinfunction "2_5") (pintype "passive"))
      (node (ref "X6") (pin "2") (pinfunction "2_2") (pintype "passive"))
      (node (ref "X6") (pin "3") (pinfunction "2_3") (pintype "passive"))
      (node (ref "X6") (pin "4") (pinfunction "2_4") (pintype "passive"))
      (node (ref "X6") (pin "5") (pinfunction "2_5") (pintype "passive"))
      (node (ref "X7") (pin "2") (pinfunction "2_2") (pintype "passive"))
      (node (ref "X7") (pin "3") (pinfunction "2_3") (pintype "passive"))
      (node (ref "X7") (pin "4") (pinfunction "2_4") (pintype "passive"))
      (node (ref "X7") (pin "5") (pinfunction "2_5") (pintype "passive"))
      (node (ref "X8") (pin "2") (pinfunction "2_2") (pintype "passive"))
      (node (ref "X8") (pin "3") (pinfunction "2_3") (pintype "passive"))
      (node (ref "X8") (pin "4") (pinfunction "2_4") (pintype "passive"))
      (node (ref "X8") (pin "5") (pinfunction "2_5") (pintype "passive"))
    )
    (net (code "29") (name "I2C_CORE_SCL") (class "Default")
      (node (ref "IC1") (pin "25") (pinfunction "(SCL/INT0)PD0_25") (pintype "bidirectional"))
      (node (ref "OLED_DISP") (pin "3") (pinfunction "3_3") (pintype "passive"))
      (node (ref "R59") (pin "2") (pinfunction "2_2") (pintype "passive"))
    )
    (net (code "30") (name "I2C_CORE_SDA") (class "Default")
      (node (ref "IC1") (pin "26") (pinfunction "(SDA/INT1)PD1_26") (pintype "bidirectional"))
      (node (ref "OLED_DISP") (pin "4") (pinfunction "4_4") (pintype "passive"))
      (node (ref "R58") (pin "2") (pinfunction "2_2") (pintype "passive"))
    )
    (net (code "31") (name "IC_W") (class "Default")
      (node (ref "IC_IN_W") (pin "1") (pinfunction "1_1") (pintype "passive"))
      (node (ref "IC_IN_W") (pin "2") (pinfunction "2_2") (pintype "passive"))
      (node (ref "U$4") (pin "P$12") (pinfunction "12_P$12") (pintype "passive"))
    )
    (net (code "32") (name "IC_X") (class "Default")
      (node (ref "IC_IN_X") (pin "1") (pinfunction "1_1") (pintype "passive"))
      (node (ref "IC_IN_X") (pin "2") (pinfunction "2_2") (pintype "passive"))
      (node (ref "U$4") (pin "P$03") (pinfunction "3_P$03") (pintype "passive"))
    )
    (net (code "33") (name "IC_Y") (class "Default")
      (node (ref "IC_IN_Y") (pin "1") (pinfunction "1_1") (pintype "passive"))
      (node (ref "IC_IN_Y") (pin "2") (pinfunction "2_2") (pintype "passive"))
      (node (ref "U$4") (pin "P$06") (pinfunction "6_P$06") (pintype "passive"))
    )
    (net (code "34") (name "IC_Z") (class "Default")
      (node (ref "IC_IN_Z") (pin "1") (pinfunction "1_1") (pintype "passive"))
      (node (ref "IC_IN_Z") (pin "2") (pinfunction "2_2") (pintype "passive"))
      (node (ref "U$4") (pin "P$09") (pinfunction "9_P$09") (pintype "passive"))
    )
    (net (code "35") (name "INV1_IN") (class "Default")
      (node (ref "INVERTORS") (pin "1") (pinfunction "1_1") (pintype "passive"))
      (node (ref "R60") (pin "2") (pinfunction "2_2") (pintype "passive"))
    )
    (net (code "36") (name "INV1_OUT") (class "Default")
      (node (ref "INVERTORS") (pin "2") (pinfunction "2_2") (pintype "passive"))
      (node (ref "R61") (pin "1") (pinfunction "1_1") (pintype "passive"))
      (node (ref "U2") (pin "1") (pinfunction "OUT_1") (pintype "output"))
    )
    (net (code "37") (name "INV2_IN") (class "Default")
      (node (ref "INVERTORS") (pin "3") (pinfunction "3_3") (pintype "passive"))
      (node (ref "R62") (pin "2") (pinfunction "2_2") (pintype "passive"))
    )
    (net (code "38") (name "INV2_OUT") (class "Default")
      (node (ref "INVERTORS") (pin "4") (pinfunction "4_4") (pintype "passive"))
      (node (ref "R63") (pin "1") (pinfunction "1_1") (pintype "passive"))
      (node (ref "U2") (pin "7") (pinfunction "OUT_7") (pintype "output"))
    )
    (net (code "39") (name "INV3_IN") (class "Default")
      (node (ref "INVERTORS") (pin "5") (pinfunction "5_5") (pintype "passive"))
      (node (ref "R64") (pin "2") (pinfunction "2_2") (pintype "passive"))
    )
    (net (code "40") (name "INV3_OUT") (class "Default")
      (node (ref "INVERTORS") (pin "6") (pinfunction "6_6") (pintype "passive"))
      (node (ref "R65") (pin "1") (pinfunction "1_1") (pintype "passive"))
      (node (ref "U2") (pin "10") (pinfunction "OUT_10") (pintype "output"))
    )
    (net (code "41") (name "INV4_IN") (class "Default")
      (node (ref "INVERTORS") (pin "7") (pinfunction "7_7") (pintype "passive"))
      (node (ref "R66") (pin "2") (pinfunction "2_2") (pintype "passive"))
    )
    (net (code "42") (name "INV4_OUT") (class "Default")
      (node (ref "INVERTORS") (pin "8") (pinfunction "8_8") (pintype "passive"))
      (node (ref "R67") (pin "1") (pinfunction "1_1") (pintype "passive"))
      (node (ref "U2") (pin "16") (pinfunction "OUT_16") (pintype "output"))
    )
    (net (code "43") (name "KEYPAD_C1") (class "Default")
      (node (ref "IC1") (pin "35") (pinfunction "(A8)PC0_35") (pintype "output"))
      (node (ref "KEYPAD") (pin "1") (pinfunction "1_1") (pintype "passive"))
    )
    (net (code "44") (name "KEYPAD_C2") (class "Default")
      (node (ref "IC1") (pin "36") (pinfunction "(A9)PC1_36") (pintype "output"))
      (node (ref "KEYPAD") (pin "2") (pinfunction "2_2") (pintype "passive"))
    )
    (net (code "45") (name "KEYPAD_C3") (class "Default")
      (node (ref "IC1") (pin "37") (pinfunction "(A10)PC2_37") (pintype "output"))
      (node (ref "KEYPAD") (pin "3") (pinfunction "3_3") (pintype "passive"))
    )
    (net (code "46") (name "KEYPAD_C4") (class "Default")
      (node (ref "IC1") (pin "38") (pinfunction "(A11)PC3_38") (pintype "output"))
      (node (ref "KEYPAD") (pin "4") (pinfunction "4_4") (pintype "passive"))
    )
    (net (code "47") (name "KEYPAD_R1") (class "Default")
      (node (ref "IC1") (pin "39") (pinfunction "(A12)PC4_39") (pintype "output"))
      (node (ref "KEYPAD") (pin "5") (pinfunction "5_5") (pintype "passive"))
    )
    (net (code "48") (name "KEYPAD_R2") (class "Default")
      (node (ref "IC1") (pin "40") (pinfunction "(A13)PC5_40") (pintype "output"))
      (node (ref "KEYPAD") (pin "6") (pinfunction "6_6") (pintype "passive"))
    )
    (net (code "49") (name "KEYPAD_R3") (class "Default")
      (node (ref "IC1") (pin "41") (pinfunction "(A14)PC6_41") (pintype "output"))
      (node (ref "KEYPAD") (pin "7") (pinfunction "7_7") (pintype "passive"))
    )
    (net (code "50") (name "KEYPAD_R4") (class "Default")
      (node (ref "IC1") (pin "42") (pinfunction "(A15)PC7_42") (pintype "output"))
      (node (ref "KEYPAD") (pin "8") (pinfunction "8_8") (pintype "passive"))
    )
    (net (code "51") (name "MLT1_OUT") (class "Default")
      (node (ref "MLT1") (pin "5") (pinfunction "7_5") (pintype "output"))
      (node (ref "MULT_OUT_1") (pin "1") (pinfunction "1_1") (pintype "passive"))
      (node (ref "MULT_OUT_1") (pin "2") (pinfunction "2_2") (pintype "passive"))
    )
    (net (code "52") (name "MLT2_OUT") (class "Default")
      (node (ref "MLT2") (pin "5") (pinfunction "7_5") (pintype "output"))
      (node (ref "MULT_OUT_2") (pin "1") (pinfunction "1_1") (pintype "passive"))
      (node (ref "MULT_OUT_2") (pin "2") (pinfunction "2_2") (pintype "passive"))
    )
    (net (code "53") (name "MLT3_OUT") (class "Default")
      (node (ref "MLT3") (pin "5") (pinfunction "7_5") (pintype "output"))
      (node (ref "MULT_OUT_3") (pin "1") (pinfunction "1_1") (pintype "passive"))
      (node (ref "MULT_OUT_3") (pin "2") (pinfunction "2_2") (pintype "passive"))
    )
    (net (code "54") (name "MLT4_OUT") (class "Default")
      (node (ref "MLT4") (pin "5") (pinfunction "7_5") (pintype "output"))
      (node (ref "MULT_OUT_4") (pin "1") (pinfunction "1_1") (pintype "passive"))
      (node (ref "MULT_OUT_4") (pin "2") (pinfunction "2_2") (pintype "passive"))
    )
    (net (code "55") (name "MLT5_OUT") (class "Default")
      (node (ref "MLT5") (pin "5") (pinfunction "7_5") (pintype "output"))
      (node (ref "MULT_OUT_5") (pin "1") (pinfunction "1_1") (pintype "passive"))
      (node (ref "MULT_OUT_5") (pin "2") (pinfunction "2_2") (pintype "passive"))
    )
    (net (code "56") (name "MLT6_OUT") (class "Default")
      (node (ref "MLT6") (pin "5") (pinfunction "7_5") (pintype "output"))
      (node (ref "MULT_OUT_6") (pin "1") (pinfunction "1_1") (pintype "passive"))
      (node (ref "MULT_OUT_6") (pin "2") (pinfunction "2_2") (pintype "passive"))
    )
    (net (code "57") (name "MLT7_OUT") (class "Default")
      (node (ref "MLT7") (pin "5") (pinfunction "7_5") (pintype "output"))
      (node (ref "MULT_OUT_7") (pin "1") (pinfunction "1_1") (pintype "passive"))
      (node (ref "MULT_OUT_7") (pin "2") (pinfunction "2_2") (pintype "passive"))
    )
    (net (code "58") (name "MLT8_OUT") (class "Default")
      (node (ref "MLT8") (pin "5") (pinfunction "7_5") (pintype "output"))
      (node (ref "MULT_OUT_8") (pin "1") (pinfunction "1_1") (pintype "passive"))
      (node (ref "MULT_OUT_8") (pin "2") (pinfunction "2_2") (pintype "passive"))
    )
    (net (code "59") (name "Net-(AD_OUT1-REFIN{slash}OUT)") (class "Default")
      (node (ref "AD_OUT1") (pin "5") (pinfunction "REFIN/OUT_5") (pintype "output"))
      (node (ref "C58") (pin "1") (pinfunction "1_1") (pintype "passive"))
    )
    (net (code "60") (name "Net-(AD_OUT2-REFIN{slash}OUT)") (class "Default")
      (node (ref "AD_OUT2") (pin "5") (pinfunction "REFIN/OUT_5") (pintype "output"))
      (node (ref "C59") (pin "1") (pinfunction "1_1") (pintype "passive"))
    )
    (net (code "61") (name "Net-(AD_PWL-REFIN{slash}OUT)") (class "Default")
      (node (ref "AD_PWL") (pin "5") (pinfunction "REFIN/OUT_5") (pintype "output"))
      (node (ref "C57") (pin "1") (pinfunction "1_1") (pintype "passive"))
    )
    (net (code "62") (name "Net-(CFA1-2)") (class "Default")
      (node (ref "CFA1") (pin "3") (pinfunction "2_3") (pintype "input"))
      (node (ref "S1") (pin "P$A") (pinfunction "A_P$A") (pintype "passive"))
    )
    (net (code "63") (name "Net-(CFA1-3)") (class "Default")
      (node (ref "CFA1") (pin "5") (pinfunction "3_5") (pintype "input"))
      (node (ref "S5") (pin "5") (pinfunction "P_5") (pintype "passive"))
    )
    (net (code "64") (name "Net-(CFA1-6)") (class "Default")
      (node (ref "CFA1") (pin "12") (pinfunction "6_12") (pintype "output"))
      (node (ref "INTEG_OUT_X") (pin "1") (pinfunction "1_1") (pintype "passive"))
      (node (ref "INTEG_OUT_X") (pin "10") (pinfunction "10_10") (pintype "passive"))
      (node (ref "INTEG_OUT_X") (pin "11") (pinfunction "11_11") (pintype "passive"))
      (node (ref "INTEG_OUT_X") (pin "12") (pinfunction "12_12") (pintype "passive"))
      (node (ref "INTEG_OUT_X") (pin "13") (pinfunction "13_13") (pintype "passive"))
      (node (ref "INTEG_OUT_X") (pin "14") (pinfunction "14_14") (pintype "passive"))
      (node (ref "INTEG_OUT_X") (pin "15") (pinfunction "15_15") (pintype "passive"))
      (node (ref "INTEG_OUT_X") (pin "16") (pinfunction "16_16") (pintype "passive"))
      (node (ref "INTEG_OUT_X") (pin "17") (pinfunction "17_17") (pintype "passive"))
      (node (ref "INTEG_OUT_X") (pin "18") (pinfunction "18_18") (pintype "passive"))
      (node (ref "INTEG_OUT_X") (pin "19") (pinfunction "19_19") (pintype "passive"))
      (node (ref "INTEG_OUT_X") (pin "2") (pinfunction "2_2") (pintype "passive"))
      (node (ref "INTEG_OUT_X") (pin "3") (pinfunction "3_3") (pintype "passive"))
      (node (ref "INTEG_OUT_X") (pin "4") (pinfunction "4_4") (pintype "passive"))
      (node (ref "INTEG_OUT_X") (pin "5") (pinfunction "5_5") (pintype "passive"))
      (node (ref "INTEG_OUT_X") (pin "6") (pinfunction "6_6") (pintype "passive"))
      (node (ref "INTEG_OUT_X") (pin "7") (pinfunction "7_7") (pintype "passive"))
      (node (ref "INTEG_OUT_X") (pin "8") (pinfunction "8_8") (pintype "passive"))
      (node (ref "INTEG_OUT_X") (pin "9") (pinfunction "9_9") (pintype "passive"))
    )
    (net (code "65") (name "Net-(CFA2-2)") (class "Default")
      (node (ref "CFA2") (pin "3") (pinfunction "2_3") (pintype "input"))
      (node (ref "S2") (pin "P$A") (pinfunction "A_P$A") (pintype "passive"))
    )
    (net (code "66") (name "Net-(CFA2-3)") (class "Default")
      (node (ref "CFA2") (pin "5") (pinfunction "3_5") (pintype "input"))
      (node (ref "S6") (pin "5") (pinfunction "P_5") (pintype "passive"))
    )
    (net (code "67") (name "Net-(CFA2-6)") (class "Default")
      (node (ref "CFA2") (pin "12") (pinfunction "6_12") (pintype "output"))
      (node (ref "INTEG_OUT_Y") (pin "1") (pinfunction "1_1") (pintype "passive"))
      (node (ref "INTEG_OUT_Y") (pin "10") (pinfunction "10_10") (pintype "passive"))
      (node (ref "INTEG_OUT_Y") (pin "11") (pinfunction "11_11") (pintype "passive"))
      (node (ref "INTEG_OUT_Y") (pin "12") (pinfunction "12_12") (pintype "passive"))
      (node (ref "INTEG_OUT_Y") (pin "13") (pinfunction "13_13") (pintype "passive"))
      (node (ref "INTEG_OUT_Y") (pin "14") (pinfunction "14_14") (pintype "passive"))
      (node (ref "INTEG_OUT_Y") (pin "15") (pinfunction "15_15") (pintype "passive"))
      (node (ref "INTEG_OUT_Y") (pin "16") (pinfunction "16_16") (pintype "passive"))
      (node (ref "INTEG_OUT_Y") (pin "17") (pinfunction "17_17") (pintype "passive"))
      (node (ref "INTEG_OUT_Y") (pin "18") (pinfunction "18_18") (pintype "passive"))
      (node (ref "INTEG_OUT_Y") (pin "19") (pinfunction "19_19") (pintype "passive"))
      (node (ref "INTEG_OUT_Y") (pin "2") (pinfunction "2_2") (pintype "passive"))
      (node (ref "INTEG_OUT_Y") (pin "3") (pinfunction "3_3") (pintype "passive"))
      (node (ref "INTEG_OUT_Y") (pin "4") (pinfunction "4_4") (pintype "passive"))
      (node (ref "INTEG_OUT_Y") (pin "5") (pinfunction "5_5") (pintype "passive"))
      (node (ref "INTEG_OUT_Y") (pin "6") (pinfunction "6_6") (pintype "passive"))
      (node (ref "INTEG_OUT_Y") (pin "7") (pinfunction "7_7") (pintype "passive"))
      (node (ref "INTEG_OUT_Y") (pin "8") (pinfunction "8_8") (pintype "passive"))
      (node (ref "INTEG_OUT_Y") (pin "9") (pinfunction "9_9") (pintype "passive"))
    )
    (net (code "68") (name "Net-(CFA3-2)") (class "Default")
      (node (ref "CFA3") (pin "3") (pinfunction "2_3") (pintype "input"))
      (node (ref "S3") (pin "P$A") (pinfunction "A_P$A") (pintype "passive"))
    )
    (net (code "69") (name "Net-(CFA3-3)") (class "Default")
      (node (ref "CFA3") (pin "5") (pinfunction "3_5") (pintype "input"))
      (node (ref "S7") (pin "5") (pinfunction "P_5") (pintype "passive"))
    )
    (net (code "70") (name "Net-(CFA3-6)") (class "Default")
      (node (ref "CFA3") (pin "12") (pinfunction "6_12") (pintype "output"))
      (node (ref "INTEG_OUT_Z") (pin "1") (pinfunction "1_1") (pintype "passive"))
      (node (ref "INTEG_OUT_Z") (pin "10") (pinfunction "10_10") (pintype "passive"))
      (node (ref "INTEG_OUT_Z") (pin "11") (pinfunction "11_11") (pintype "passive"))
      (node (ref "INTEG_OUT_Z") (pin "12") (pinfunction "12_12") (pintype "passive"))
      (node (ref "INTEG_OUT_Z") (pin "13") (pinfunction "13_13") (pintype "passive"))
      (node (ref "INTEG_OUT_Z") (pin "14") (pinfunction "14_14") (pintype "passive"))
      (node (ref "INTEG_OUT_Z") (pin "15") (pinfunction "15_15") (pintype "passive"))
      (node (ref "INTEG_OUT_Z") (pin "16") (pinfunction "16_16") (pintype "passive"))
      (node (ref "INTEG_OUT_Z") (pin "17") (pinfunction "17_17") (pintype "passive"))
      (node (ref "INTEG_OUT_Z") (pin "18") (pinfunction "18_18") (pintype "passive"))
      (node (ref "INTEG_OUT_Z") (pin "19") (pinfunction "19_19") (pintype "passive"))
      (node (ref "INTEG_OUT_Z") (pin "2") (pinfunction "2_2") (pintype "passive"))
      (node (ref "INTEG_OUT_Z") (pin "3") (pinfunction "3_3") (pintype "passive"))
      (node (ref "INTEG_OUT_Z") (pin "4") (pinfunction "4_4") (pintype "passive"))
      (node (ref "INTEG_OUT_Z") (pin "5") (pinfunction "5_5") (pintype "passive"))
      (node (ref "INTEG_OUT_Z") (pin "6") (pinfunction "6_6") (pintype "passive"))
      (node (ref "INTEG_OUT_Z") (pin "7") (pinfunction "7_7") (pintype "passive"))
      (node (ref "INTEG_OUT_Z") (pin "8") (pinfunction "8_8") (pintype "passive"))
      (node (ref "INTEG_OUT_Z") (pin "9") (pinfunction "9_9") (pintype "passive"))
    )
    (net (code "71") (name "Net-(CFA4-2)") (class "Default")
      (node (ref "CFA4") (pin "3") (pinfunction "2_3") (pintype "input"))
      (node (ref "S4") (pin "P$A") (pinfunction "A_P$A") (pintype "passive"))
    )
    (net (code "72") (name "Net-(CFA4-3)") (class "Default")
      (node (ref "CFA4") (pin "5") (pinfunction "3_5") (pintype "input"))
      (node (ref "S8") (pin "5") (pinfunction "P_5") (pintype "passive"))
    )
    (net (code "73") (name "Net-(CFA4-6)") (class "Default")
      (node (ref "CFA4") (pin "12") (pinfunction "6_12") (pintype "output"))
      (node (ref "INTEG_OUT_W") (pin "1") (pinfunction "1_1") (pintype "passive"))
      (node (ref "INTEG_OUT_W") (pin "10") (pinfunction "10_10") (pintype "passive"))
      (node (ref "INTEG_OUT_W") (pin "11") (pinfunction "11_11") (pintype "passive"))
      (node (ref "INTEG_OUT_W") (pin "12") (pinfunction "12_12") (pintype "passive"))
      (node (ref "INTEG_OUT_W") (pin "13") (pinfunction "13_13") (pintype "passive"))
      (node (ref "INTEG_OUT_W") (pin "14") (pinfunction "14_14") (pintype "passive"))
      (node (ref "INTEG_OUT_W") (pin "15") (pinfunction "15_15") (pintype "passive"))
      (node (ref "INTEG_OUT_W") (pin "16") (pinfunction "16_16") (pintype "passive"))
      (node (ref "INTEG_OUT_W") (pin "17") (pinfunction "17_17") (pintype "passive"))
      (node (ref "INTEG_OUT_W") (pin "18") (pinfunction "18_18") (pintype "passive"))
      (node (ref "INTEG_OUT_W") (pin "19") (pinfunction "19_19") (pintype "passive"))
      (node (ref "INTEG_OUT_W") (pin "2") (pinfunction "2_2") (pintype "passive"))
      (node (ref "INTEG_OUT_W") (pin "3") (pinfunction "3_3") (pintype "passive"))
      (node (ref "INTEG_OUT_W") (pin "4") (pinfunction "4_4") (pintype "passive"))
      (node (ref "INTEG_OUT_W") (pin "5") (pinfunction "5_5") (pintype "passive"))
      (node (ref "INTEG_OUT_W") (pin "6") (pinfunction "6_6") (pintype "passive"))
      (node (ref "INTEG_OUT_W") (pin "7") (pinfunction "7_7") (pintype "passive"))
      (node (ref "INTEG_OUT_W") (pin "8") (pinfunction "8_8") (pintype "passive"))
      (node (ref "INTEG_OUT_W") (pin "9") (pinfunction "9_9") (pintype "passive"))
    )
    (net (code "74") (name "Net-(CFA5-2)") (class "Default")
      (node (ref "CFA5") (pin "3") (pinfunction "2_3") (pintype "input"))
      (node (ref "R41") (pin "2") (pinfunction "2_2") (pintype "passive"))
    )
    (net (code "75") (name "Net-(CFA5-3)") (class "Default")
      (node (ref "CFA5") (pin "5") (pinfunction "3_5") (pintype "input"))
      (node (ref "S9") (pin "5") (pinfunction "P_5") (pintype "passive"))
    )
    (net (code "76") (name "Net-(CFA5-5)") (class "Default")
      (node (ref "CFA5") (pin "11") (pinfunction "5_11") (pintype "passive"))
      (node (ref "R93") (pin "2") (pinfunction "2_2") (pintype "passive"))
    )
    (net (code "77") (name "Net-(D1-PadA)") (class "Default")
      (node (ref "D1") (pin "A") (pinfunction "A_A") (pintype "passive"))
      (node (ref "F1") (pin "2") (pinfunction "2_2") (pintype "passive"))
      (node (ref "U$3") (pin "D") (pinfunction "D_D") (pintype "passive"))
    )
    (net (code "78") (name "Net-(D2-PadC)") (class "Default")
      (node (ref "D2") (pin "C") (pinfunction "C_C") (pintype "passive"))
      (node (ref "F2") (pin "2") (pinfunction "2_2") (pintype "passive"))
      (node (ref "U$2") (pin "D") (pinfunction "D_D") (pintype "passive"))
    )
    (net (code "79") (name "Net-(F1-Pad1)") (class "Default")
      (node (ref "F1") (pin "1") (pinfunction "1_1") (pintype "passive"))
      (node (ref "PWR") (pin "1") (pinfunction "1_1") (pintype "passive"))
    )
    (net (code "80") (name "Net-(F2-Pad1)") (class "Default")
      (node (ref "F2") (pin "1") (pinfunction "1_1") (pintype "passive"))
      (node (ref "PWR") (pin "3") (pinfunction "3_3") (pintype "passive"))
    )
    (net (code "81") (name "Net-(IC1-XTAL1)") (class "Default")
      (node (ref "C79") (pin "2") (pinfunction "2_2") (pintype "passive"))
      (node (ref "IC1") (pin "24") (pinfunction "XTAL1_24") (pintype "bidirectional"))
      (node (ref "Q1") (pin "1") (pinfunction "1_1") (pintype "passive"))
    )
    (net (code "82") (name "Net-(IC1-XTAL2)") (class "Default")
      (node (ref "C78") (pin "2") (pinfunction "2_2") (pintype "passive"))
      (node (ref "IC1") (pin "23") (pinfunction "XTAL2_23") (pintype "bidirectional"))
      (node (ref "Q1") (pin "2") (pinfunction "2_2") (pintype "passive"))
    )
    (net (code "83") (name "Net-(IC2-PB6(XTAL1{slash}TOSC1))") (class "Default")
      (node (ref "C80") (pin "1") (pinfunction "1_1") (pintype "passive"))
      (node (ref "IC2") (pin "7") (pinfunction "PB6(XTAL1/TOSC1)_7") (pintype "bidirectional"))
      (node (ref "Q2") (pin "2") (pinfunction "2_2") (pintype "passive"))
    )
    (net (code "84") (name "Net-(IC2-PB7(XTAL2{slash}TOSC2))") (class "Default")
      (node (ref "C81") (pin "1") (pinfunction "1_1") (pintype "passive"))
      (node (ref "IC2") (pin "8") (pinfunction "PB7(XTAL2/TOSC2)_8") (pintype "bidirectional"))
      (node (ref "Q2") (pin "1") (pinfunction "1_1") (pintype "passive"))
    )
    (net (code "85") (name "Net-(IC3-USBDM)") (class "Default")
      (node (ref "IC3") (pin "9") (pinfunction "USBDM_9") (pintype "input"))
      (node (ref "R57") (pin "1") (pinfunction "1_1") (pintype "passive"))
    )
    (net (code "86") (name "Net-(IC3-USBDP)") (class "Default")
      (node (ref "IC3") (pin "8") (pinfunction "USBDP_8") (pintype "input"))
      (node (ref "R56") (pin "1") (pinfunction "1_1") (pintype "passive"))
    )
    (net (code "87") (name "Net-(JP39-Pad1)") (class "Default")
      (node (ref "JP39") (pin "1") (pinfunction "1_1") (pintype "passive"))
      (node (ref "X1") (pin "1") (pinfunction "1_1") (pintype "passive"))
    )
    (net (code "88") (name "Net-(JP40-Pad1)") (class "Default")
      (node (ref "JP40") (pin "1") (pinfunction "1_1") (pintype "passive"))
      (node (ref "X2") (pin "1") (pinfunction "1_1") (pintype "passive"))
    )
    (net (code "89") (name "Net-(JP41-Pad1)") (class "Default")
      (node (ref "JP41") (pin "1") (pinfunction "1_1") (pintype "passive"))
      (node (ref "X3") (pin "1") (pinfunction "1_1") (pintype "passive"))
    )
    (net (code "90") (name "Net-(JP42-Pad1)") (class "Default")
      (node (ref "JP42") (pin "1") (pinfunction "1_1") (pintype "passive"))
      (node (ref "X4") (pin "1") (pinfunction "1_1") (pintype "passive"))
    )
    (net (code "91") (name "Net-(JUMPER1-Pad1)") (class "Default")
      (node (ref "JUMPER1") (pin "1") (pinfunction "1_1") (pintype "passive"))
      (node (ref "JUMPER1") (pin "2") (pinfunction "2_2") (pintype "passive"))
      (node (ref "JUMPER1") (pin "3") (pinfunction "3_3") (pintype "passive"))
      (node (ref "JUMPER1") (pin "4") (pinfunction "4_4") (pintype "passive"))
    )
    (net (code "92") (name "Net-(JUMPER2-Pad1)") (class "Default")
      (node (ref "JUMPER2") (pin "1") (pinfunction "1_1") (pintype "passive"))
      (node (ref "JUMPER2") (pin "2") (pinfunction "2_2") (pintype "passive"))
      (node (ref "JUMPER2") (pin "3") (pinfunction "3_3") (pintype "passive"))
      (node (ref "JUMPER2") (pin "4") (pinfunction "4_4") (pintype "passive"))
    )
    (net (code "93") (name "Net-(JUMPER3-Pad1)") (class "Default")
      (node (ref "JUMPER3") (pin "1") (pinfunction "1_1") (pintype "passive"))
      (node (ref "JUMPER3") (pin "2") (pinfunction "2_2") (pintype "passive"))
      (node (ref "JUMPER3") (pin "3") (pinfunction "3_3") (pintype "passive"))
      (node (ref "JUMPER3") (pin "4") (pinfunction "4_4") (pintype "passive"))
    )
    (net (code "94") (name "Net-(MLT1-1)") (class "Default")
      (node (ref "MLT1") (pin "7") (pinfunction "1_7") (pintype "input"))
      (node (ref "MULT_IN_1") (pin "2") (pinfunction "2_2") (pintype "passive"))
    )
    (net (code "95") (name "Net-(MLT1-2)") (class "Default")
      (node (ref "MLT1") (pin "8") (pinfunction "2_8") (pintype "input"))
      (node (ref "MULT_IN_1") (pin "4") (pinfunction "4_4") (pintype "passive"))
    )
    (net (code "96") (name "Net-(MLT1-3)") (class "Default")
      (node (ref "MLT1") (pin "1") (pinfunction "3_1") (pintype "input"))
      (node (ref "MULT_IN_1") (pin "6") (pinfunction "6_6") (pintype "passive"))
    )
    (net (code "97") (name "Net-(MLT1-4)") (class "Default")
      (node (ref "MLT1") (pin "2") (pinfunction "4_2") (pintype "input"))
      (node (ref "MULT_IN_1") (pin "8") (pinfunction "8_8") (pintype "passive"))
    )
    (net (code "98") (name "Net-(MLT1-6)") (class "Default")
      (node (ref "MLT1") (pin "4") (pinfunction "6_4") (pintype "input"))
      (node (ref "MULT_OUT_1") (pin "3") (pinfunction "3_3") (pintype "passive"))
    )
    (net (code "99") (name "Net-(MLT2-1)") (class "Default")
      (node (ref "MLT2") (pin "7") (pinfunction "1_7") (pintype "input"))
      (node (ref "MULT_IN_2") (pin "2") (pinfunction "2_2") (pintype "passive"))
    )
    (net (code "100") (name "Net-(MLT2-2)") (class "Default")
      (node (ref "MLT2") (pin "8") (pinfunction "2_8") (pintype "input"))
      (node (ref "MULT_IN_2") (pin "4") (pinfunction "4_4") (pintype "passive"))
    )
    (net (code "101") (name "Net-(MLT2-3)") (class "Default")
      (node (ref "MLT2") (pin "1") (pinfunction "3_1") (pintype "input"))
      (node (ref "MULT_IN_2") (pin "6") (pinfunction "6_6") (pintype "passive"))
    )
    (net (code "102") (name "Net-(MLT2-4)") (class "Default")
      (node (ref "MLT2") (pin "2") (pinfunction "4_2") (pintype "input"))
      (node (ref "MULT_IN_2") (pin "8") (pinfunction "8_8") (pintype "passive"))
    )
    (net (code "103") (name "Net-(MLT2-6)") (class "Default")
      (node (ref "MLT2") (pin "4") (pinfunction "6_4") (pintype "input"))
      (node (ref "MULT_OUT_2") (pin "3") (pinfunction "3_3") (pintype "passive"))
    )
    (net (code "104") (name "Net-(MLT3-1)") (class "Default")
      (node (ref "MLT3") (pin "7") (pinfunction "1_7") (pintype "input"))
      (node (ref "MULT_IN_3") (pin "2") (pinfunction "2_2") (pintype "passive"))
    )
    (net (code "105") (name "Net-(MLT3-2)") (class "Default")
      (node (ref "MLT3") (pin "8") (pinfunction "2_8") (pintype "input"))
      (node (ref "MULT_IN_3") (pin "4") (pinfunction "4_4") (pintype "passive"))
    )
    (net (code "106") (name "Net-(MLT3-3)") (class "Default")
      (node (ref "MLT3") (pin "1") (pinfunction "3_1") (pintype "input"))
      (node (ref "MULT_IN_3") (pin "6") (pinfunction "6_6") (pintype "passive"))
    )
    (net (code "107") (name "Net-(MLT3-4)") (class "Default")
      (node (ref "MLT3") (pin "2") (pinfunction "4_2") (pintype "input"))
      (node (ref "MULT_IN_3") (pin "8") (pinfunction "8_8") (pintype "passive"))
    )
    (net (code "108") (name "Net-(MLT3-6)") (class "Default")
      (node (ref "MLT3") (pin "4") (pinfunction "6_4") (pintype "input"))
      (node (ref "MULT_OUT_3") (pin "3") (pinfunction "3_3") (pintype "passive"))
    )
    (net (code "109") (name "Net-(MLT4-1)") (class "Default")
      (node (ref "MLT4") (pin "7") (pinfunction "1_7") (pintype "input"))
      (node (ref "MULT_IN_4") (pin "2") (pinfunction "2_2") (pintype "passive"))
    )
    (net (code "110") (name "Net-(MLT4-2)") (class "Default")
      (node (ref "MLT4") (pin "8") (pinfunction "2_8") (pintype "input"))
      (node (ref "MULT_IN_4") (pin "4") (pinfunction "4_4") (pintype "passive"))
    )
    (net (code "111") (name "Net-(MLT4-3)") (class "Default")
      (node (ref "MLT4") (pin "1") (pinfunction "3_1") (pintype "input"))
      (node (ref "MULT_IN_4") (pin "6") (pinfunction "6_6") (pintype "passive"))
    )
    (net (code "112") (name "Net-(MLT4-4)") (class "Default")
      (node (ref "MLT4") (pin "2") (pinfunction "4_2") (pintype "input"))
      (node (ref "MULT_IN_4") (pin "8") (pinfunction "8_8") (pintype "passive"))
    )
    (net (code "113") (name "Net-(MLT4-6)") (class "Default")
      (node (ref "MLT4") (pin "4") (pinfunction "6_4") (pintype "input"))
      (node (ref "MULT_OUT_4") (pin "3") (pinfunction "3_3") (pintype "passive"))
    )
    (net (code "114") (name "Net-(MLT5-1)") (class "Default")
      (node (ref "MLT5") (pin "7") (pinfunction "1_7") (pintype "input"))
      (node (ref "MULT_IN_5") (pin "2") (pinfunction "2_2") (pintype "passive"))
    )
    (net (code "115") (name "Net-(MLT5-2)") (class "Default")
      (node (ref "MLT5") (pin "8") (pinfunction "2_8") (pintype "input"))
      (node (ref "MULT_IN_5") (pin "4") (pinfunction "4_4") (pintype "passive"))
    )
    (net (code "116") (name "Net-(MLT5-3)") (class "Default")
      (node (ref "MLT5") (pin "1") (pinfunction "3_1") (pintype "input"))
      (node (ref "MULT_IN_5") (pin "6") (pinfunction "6_6") (pintype "passive"))
    )
    (net (code "117") (name "Net-(MLT5-4)") (class "Default")
      (node (ref "MLT5") (pin "2") (pinfunction "4_2") (pintype "input"))
      (node (ref "MULT_IN_5") (pin "8") (pinfunction "8_8") (pintype "passive"))
    )
    (net (code "118") (name "Net-(MLT5-6)") (class "Default")
      (node (ref "MLT5") (pin "4") (pinfunction "6_4") (pintype "input"))
      (node (ref "MULT_OUT_5") (pin "3") (pinfunction "3_3") (pintype "passive"))
    )
    (net (code "119") (name "Net-(MLT6-1)") (class "Default")
      (node (ref "MLT6") (pin "7") (pinfunction "1_7") (pintype "input"))
      (node (ref "MULT_IN_6") (pin "2") (pinfunction "2_2") (pintype "passive"))
    )
    (net (code "120") (name "Net-(MLT6-2)") (class "Default")
      (node (ref "MLT6") (pin "8") (pinfunction "2_8") (pintype "input"))
      (node (ref "MULT_IN_6") (pin "4") (pinfunction "4_4") (pintype "passive"))
    )
    (net (code "121") (name "Net-(MLT6-3)") (class "Default")
      (node (ref "MLT6") (pin "1") (pinfunction "3_1") (pintype "input"))
      (node (ref "MULT_IN_6") (pin "6") (pinfunction "6_6") (pintype "passive"))
    )
    (net (code "122") (name "Net-(MLT6-4)") (class "Default")
      (node (ref "MLT6") (pin "2") (pinfunction "4_2") (pintype "input"))
      (node (ref "MULT_IN_6") (pin "8") (pinfunction "8_8") (pintype "passive"))
    )
    (net (code "123") (name "Net-(MLT6-6)") (class "Default")
      (node (ref "MLT6") (pin "4") (pinfunction "6_4") (pintype "input"))
      (node (ref "MULT_OUT_6") (pin "3") (pinfunction "3_3") (pintype "passive"))
    )
    (net (code "124") (name "Net-(MLT7-1)") (class "Default")
      (node (ref "MLT7") (pin "7") (pinfunction "1_7") (pintype "input"))
      (node (ref "MULT_IN_7") (pin "2") (pinfunction "2_2") (pintype "passive"))
    )
    (net (code "125") (name "Net-(MLT7-2)") (class "Default")
      (node (ref "MLT7") (pin "8") (pinfunction "2_8") (pintype "input"))
      (node (ref "MULT_IN_7") (pin "4") (pinfunction "4_4") (pintype "passive"))
    )
    (net (code "126") (name "Net-(MLT7-3)") (class "Default")
      (node (ref "MLT7") (pin "1") (pinfunction "3_1") (pintype "input"))
      (node (ref "MULT_IN_7") (pin "6") (pinfunction "6_6") (pintype "passive"))
    )
    (net (code "127") (name "Net-(MLT7-4)") (class "Default")
      (node (ref "MLT7") (pin "2") (pinfunction "4_2") (pintype "input"))
      (node (ref "MULT_IN_7") (pin "8") (pinfunction "8_8") (pintype "passive"))
    )
    (net (code "128") (name "Net-(MLT7-6)") (class "Default")
      (node (ref "MLT7") (pin "4") (pinfunction "6_4") (pintype "input"))
      (node (ref "MULT_OUT_7") (pin "3") (pinfunction "3_3") (pintype "passive"))
    )
    (net (code "129") (name "Net-(MLT8-1)") (class "Default")
      (node (ref "MLT8") (pin "7") (pinfunction "1_7") (pintype "input"))
      (node (ref "MULT_IN_8") (pin "2") (pinfunction "2_2") (pintype "passive"))
    )
    (net (code "130") (name "Net-(MLT8-2)") (class "Default")
      (node (ref "MLT8") (pin "8") (pinfunction "2_8") (pintype "input"))
      (node (ref "MULT_IN_8") (pin "4") (pinfunction "4_4") (pintype "passive"))
    )
    (net (code "131") (name "Net-(MLT8-3)") (class "Default")
      (node (ref "MLT8") (pin "1") (pinfunction "3_1") (pintype "input"))
      (node (ref "MULT_IN_8") (pin "6") (pinfunction "6_6") (pintype "passive"))
    )
    (net (code "132") (name "Net-(MLT8-4)") (class "Default")
      (node (ref "MLT8") (pin "2") (pinfunction "4_2") (pintype "input"))
      (node (ref "MULT_IN_8") (pin "8") (pinfunction "8_8") (pintype "passive"))
    )
    (net (code "133") (name "Net-(MLT8-6)") (class "Default")
      (node (ref "MLT8") (pin "4") (pinfunction "6_4") (pintype "input"))
      (node (ref "MULT_OUT_8") (pin "3") (pinfunction "3_3") (pintype "passive"))
    )
    (net (code "134") (name "Net-(R1-A)") (class "Default")
      (node (ref "R1") (pin "1") (pinfunction "A_1") (pintype "passive"))
      (node (ref "R1") (pin "2") (pinfunction "S_2") (pintype "passive"))
      (node (ref "R2") (pin "1") (pinfunction "A_1") (pintype "passive"))
      (node (ref "R2") (pin "2") (pinfunction "S_2") (pintype "passive"))
      (node (ref "R3") (pin "1") (pinfunction "A_1") (pintype "passive"))
      (node (ref "R3") (pin "2") (pinfunction "S_2") (pintype "passive"))
      (node (ref "R4") (pin "1") (pinfunction "A_1") (pintype "passive"))
      (node (ref "R4") (pin "2") (pinfunction "S_2") (pintype "passive"))
      (node (ref "R_EXT_X") (pin "2") (pinfunction "2_2") (pintype "passive"))
      (node (ref "S5") (pin "2") (pinfunction "P_2") (pintype "passive"))
    )
    (net (code "135") (name "Net-(R1-E)") (class "Default")
      (node (ref "R1") (pin "3") (pinfunction "E_3") (pintype "passive"))
      (node (ref "S1") (pin "P$01") (pinfunction "1_P$01") (pintype "passive"))
    )
    (net (code "136") (name "Net-(R2-E)") (class "Default")
      (node (ref "R2") (pin "3") (pinfunction "E_3") (pintype "passive"))
      (node (ref "S1") (pin "P$02") (pinfunction "2_P$02") (pintype "passive"))
    )
    (net (code "137") (name "Net-(R3-E)") (class "Default")
      (node (ref "R3") (pin "3") (pinfunction "E_3") (pintype "passive"))
      (node (ref "S1") (pin "P$03") (pinfunction "3_P$03") (pintype "passive"))
    )
    (net (code "138") (name "Net-(R4-E)") (class "Default")
      (node (ref "R4") (pin "3") (pinfunction "E_3") (pintype "passive"))
      (node (ref "S1") (pin "P$04") (pinfunction "4_P$04") (pintype "passive"))
    )
    (net (code "139") (name "Net-(R5-Pad1)") (class "Default")
      (node (ref "R5") (pin "1") (pinfunction "1_1") (pintype "passive"))
      (node (ref "SUM_IN_X") (pin "1") (pinfunction "1_1") (pintype "passive"))
    )
    (net (code "140") (name "Net-(R6-Pad1)") (class "Default")
      (node (ref "R6") (pin "1") (pinfunction "1_1") (pintype "passive"))
      (node (ref "SUM_IN_X") (pin "2") (pinfunction "2_2") (pintype "passive"))
    )
    (net (code "141") (name "Net-(R7-Pad1)") (class "Default")
      (node (ref "R7") (pin "1") (pinfunction "1_1") (pintype "passive"))
      (node (ref "SUM_IN_X") (pin "3") (pinfunction "3_3") (pintype "passive"))
    )
    (net (code "142") (name "Net-(R8-Pad1)") (class "Default")
      (node (ref "R8") (pin "1") (pinfunction "1_1") (pintype "passive"))
      (node (ref "SUM_IN_X") (pin "4") (pinfunction "4_4") (pintype "passive"))
    )
    (net (code "143") (name "Net-(R9-Pad1)") (class "Default")
      (node (ref "R9") (pin "1") (pinfunction "1_1") (pintype "passive"))
      (node (ref "SUM_IN_X") (pin "5") (pinfunction "5_5") (pintype "passive"))
    )
    (net (code "144") (name "Net-(R10-Pad1)") (class "Default")
      (node (ref "R10") (pin "1") (pinfunction "1_1") (pintype "passive"))
      (node (ref "SUM_IN_X") (pin "6") (pinfunction "6_6") (pintype "passive"))
    )
    (net (code "145") (name "Net-(R11-Pad1)") (class "Default")
      (node (ref "R11") (pin "1") (pinfunction "1_1") (pintype "passive"))
      (node (ref "SUM_IN_X") (pin "7") (pinfunction "7_7") (pintype "passive"))
    )
    (net (code "146") (name "Net-(R12-Pad1)") (class "Default")
      (node (ref "R12") (pin "1") (pinfunction "1_1") (pintype "passive"))
      (node (ref "SUM_IN_X") (pin "8") (pinfunction "8_8") (pintype "passive"))
    )
    (net (code "147") (name "Net-(R14-Pad1)") (class "Default")
      (node (ref "R14") (pin "1") (pinfunction "1_1") (pintype "passive"))
      (node (ref "SUM_IN_Y") (pin "1") (pinfunction "1_1") (pintype "passive"))
    )
    (net (code "148") (name "Net-(R15-Pad1)") (class "Default")
      (node (ref "R15") (pin "1") (pinfunction "1_1") (pintype "passive"))
      (node (ref "SUM_IN_Y") (pin "2") (pinfunction "2_2") (pintype "passive"))
    )
    (net (code "149") (name "Net-(R16-Pad1)") (class "Default")
      (node (ref "R16") (pin "1") (pinfunction "1_1") (pintype "passive"))
      (node (ref "SUM_IN_Y") (pin "3") (pinfunction "3_3") (pintype "passive"))
    )
    (net (code "150") (name "Net-(R17-Pad1)") (class "Default")
      (node (ref "R17") (pin "1") (pinfunction "1_1") (pintype "passive"))
      (node (ref "SUM_IN_Y") (pin "4") (pinfunction "4_4") (pintype "passive"))
    )
    (net (code "151") (name "Net-(R18-Pad1)") (class "Default")
      (node (ref "R18") (pin "1") (pinfunction "1_1") (pintype "passive"))
      (node (ref "SUM_IN_Y") (pin "5") (pinfunction "5_5") (pintype "passive"))
    )
    (net (code "152") (name "Net-(R19-Pad1)") (class "Default")
      (node (ref "R19") (pin "1") (pinfunction "1_1") (pintype "passive"))
      (node (ref "SUM_IN_Y") (pin "6") (pinfunction "6_6") (pintype "passive"))
    )
    (net (code "153") (name "Net-(R20-Pad1)") (class "Default")
      (node (ref "R20") (pin "1") (pinfunction "1_1") (pintype "passive"))
      (node (ref "SUM_IN_Y") (pin "7") (pinfunction "7_7") (pintype "passive"))
    )
    (net (code "154") (name "Net-(R21-Pad1)") (class "Default")
      (node (ref "R21") (pin "1") (pinfunction "1_1") (pintype "passive"))
      (node (ref "SUM_IN_Y") (pin "8") (pinfunction "8_8") (pintype "passive"))
    )
    (net (code "155") (name "Net-(R23-Pad1)") (class "Default")
      (node (ref "R23") (pin "1") (pinfunction "1_1") (pintype "passive"))
      (node (ref "SUM_IN_Z") (pin "1") (pinfunction "1_1") (pintype "passive"))
    )
    (net (code "156") (name "Net-(R24-Pad1)") (class "Default")
      (node (ref "R24") (pin "1") (pinfunction "1_1") (pintype "passive"))
      (node (ref "SUM_IN_Z") (pin "2") (pinfunction "2_2") (pintype "passive"))
    )
    (net (code "157") (name "Net-(R25-Pad1)") (class "Default")
      (node (ref "R25") (pin "1") (pinfunction "1_1") (pintype "passive"))
      (node (ref "SUM_IN_Z") (pin "3") (pinfunction "3_3") (pintype "passive"))
    )
    (net (code "158") (name "Net-(R26-Pad1)") (class "Default")
      (node (ref "R26") (pin "1") (pinfunction "1_1") (pintype "passive"))
      (node (ref "SUM_IN_Z") (pin "4") (pinfunction "4_4") (pintype "passive"))
    )
    (net (code "159") (name "Net-(R27-Pad1)") (class "Default")
      (node (ref "R27") (pin "1") (pinfunction "1_1") (pintype "passive"))
      (node (ref "SUM_IN_Z") (pin "5") (pinfunction "5_5") (pintype "passive"))
    )
    (net (code "160") (name "Net-(R28-Pad1)") (class "Default")
      (node (ref "R28") (pin "1") (pinfunction "1_1") (pintype "passive"))
      (node (ref "SUM_IN_Z") (pin "6") (pinfunction "6_6") (pintype "passive"))
    )
    (net (code "161") (name "Net-(R29-Pad1)") (class "Default")
      (node (ref "R29") (pin "1") (pinfunction "1_1") (pintype "passive"))
      (node (ref "SUM_IN_Z") (pin "7") (pinfunction "7_7") (pintype "passive"))
    )
    (net (code "162") (name "Net-(R30-Pad1)") (class "Default")
      (node (ref "R30") (pin "1") (pinfunction "1_1") (pintype "passive"))
      (node (ref "SUM_IN_Z") (pin "8") (pinfunction "8_8") (pintype "passive"))
    )
    (net (code "163") (name "Net-(R32-Pad1)") (class "Default")
      (node (ref "R32") (pin "1") (pinfunction "1_1") (pintype "passive"))
      (node (ref "SUM_IN_W") (pin "1") (pinfunction "1_1") (pintype "passive"))
    )
    (net (code "164") (name "Net-(R33-Pad1)") (class "Default")
      (node (ref "R33") (pin "1") (pinfunction "1_1") (pintype "passive"))
      (node (ref "SUM_IN_W") (pin "2") (pinfunction "2_2") (pintype "passive"))
    )
    (net (code "165") (name "Net-(R34-Pad1)") (class "Default")
      (node (ref "R34") (pin "1") (pinfunction "1_1") (pintype "passive"))
      (node (ref "SUM_IN_W") (pin "3") (pinfunction "3_3") (pintype "passive"))
    )
    (net (code "166") (name "Net-(R35-Pad1)") (class "Default")
      (node (ref "R35") (pin "1") (pinfunction "1_1") (pintype "passive"))
      (node (ref "SUM_IN_W") (pin "4") (pinfunction "4_4") (pintype "passive"))
    )
    (net (code "167") (name "Net-(R36-Pad1)") (class "Default")
      (node (ref "R36") (pin "1") (pinfunction "1_1") (pintype "passive"))
      (node (ref "SUM_IN_W") (pin "5") (pinfunction "5_5") (pintype "passive"))
    )
    (net (code "168") (name "Net-(R37-Pad1)") (class "Default")
      (node (ref "R37") (pin "1") (pinfunction "1_1") (pintype "passive"))
      (node (ref "SUM_IN_W") (pin "6") (pinfunction "6_6") (pintype "passive"))
    )
    (net (code "169") (name "Net-(R38-Pad1)") (class "Default")
      (node (ref "R38") (pin "1") (pinfunction "1_1") (pintype "passive"))
      (node (ref "SUM_IN_W") (pin "7") (pinfunction "7_7") (pintype "passive"))
    )
    (net (code "170") (name "Net-(R39-Pad1)") (class "Default")
      (node (ref "R39") (pin "1") (pinfunction "1_1") (pintype "passive"))
      (node (ref "SUM_IN_W") (pin "8") (pinfunction "8_8") (pintype "passive"))
    )
    (net (code "171") (name "Net-(R42-A)") (class "Default")
      (node (ref "R42") (pin "1") (pinfunction "A_1") (pintype "passive"))
      (node (ref "R42") (pin "2") (pinfunction "S_2") (pintype "passive"))
      (node (ref "R43") (pin "1") (pinfunction "A_1") (pintype "passive"))
      (node (ref "R43") (pin "2") (pinfunction "S_2") (pintype "passive"))
      (node (ref "R44") (pin "1") (pinfunction "A_1") (pintype "passive"))
      (node (ref "R44") (pin "2") (pinfunction "S_2") (pintype "passive"))
      (node (ref "R45") (pin "1") (pinfunction "A_1") (pintype "passive"))
      (node (ref "R45") (pin "2") (pinfunction "S_2") (pintype "passive"))
      (node (ref "R_EXT_Y") (pin "2") (pinfunction "2_2") (pintype "passive"))
      (node (ref "S6") (pin "2") (pinfunction "P_2") (pintype "passive"))
    )
    (net (code "172") (name "Net-(R42-E)") (class "Default")
      (node (ref "R42") (pin "3") (pinfunction "E_3") (pintype "passive"))
      (node (ref "S2") (pin "P$01") (pinfunction "1_P$01") (pintype "passive"))
    )
    (net (code "173") (name "Net-(R43-E)") (class "Default")
      (node (ref "R43") (pin "3") (pinfunction "E_3") (pintype "passive"))
      (node (ref "S2") (pin "P$02") (pinfunction "2_P$02") (pintype "passive"))
    )
    (net (code "174") (name "Net-(R44-E)") (class "Default")
      (node (ref "R44") (pin "3") (pinfunction "E_3") (pintype "passive"))
      (node (ref "S2") (pin "P$03") (pinfunction "3_P$03") (pintype "passive"))
    )
    (net (code "175") (name "Net-(R45-E)") (class "Default")
      (node (ref "R45") (pin "3") (pinfunction "E_3") (pintype "passive"))
      (node (ref "S2") (pin "P$04") (pinfunction "4_P$04") (pintype "passive"))
    )
    (net (code "176") (name "Net-(R46-A)") (class "Default")
      (node (ref "R46") (pin "1") (pinfunction "A_1") (pintype "passive"))
      (node (ref "R46") (pin "2") (pinfunction "S_2") (pintype "passive"))
      (node (ref "R47") (pin "1") (pinfunction "A_1") (pintype "passive"))
      (node (ref "R47") (pin "2") (pinfunction "S_2") (pintype "passive"))
      (node (ref "R48") (pin "1") (pinfunction "A_1") (pintype "passive"))
      (node (ref "R48") (pin "2") (pinfunction "S_2") (pintype "passive"))
      (node (ref "R49") (pin "1") (pinfunction "A_1") (pintype "passive"))
      (node (ref "R49") (pin "2") (pinfunction "S_2") (pintype "passive"))
      (node (ref "R_EXT_Z") (pin "2") (pinfunction "2_2") (pintype "passive"))
      (node (ref "S7") (pin "2") (pinfunction "P_2") (pintype "passive"))
    )
    (net (code "177") (name "Net-(R46-E)") (class "Default")
      (node (ref "R46") (pin "3") (pinfunction "E_3") (pintype "passive"))
      (node (ref "S3") (pin "P$01") (pinfunction "1_P$01") (pintype "passive"))
    )
    (net (code "178") (name "Net-(R47-E)") (class "Default")
      (node (ref "R47") (pin "3") (pinfunction "E_3") (pintype "passive"))
      (node (ref "S3") (pin "P$02") (pinfunction "2_P$02") (pintype "passive"))
    )
    (net (code "179") (name "Net-(R48-E)") (class "Default")
      (node (ref "R48") (pin "3") (pinfunction "E_3") (pintype "passive"))
      (node (ref "S3") (pin "P$03") (pinfunction "3_P$03") (pintype "passive"))
    )
    (net (code "180") (name "Net-(R49-E)") (class "Default")
      (node (ref "R49") (pin "3") (pinfunction "E_3") (pintype "passive"))
      (node (ref "S3") (pin "P$04") (pinfunction "4_P$04") (pintype "passive"))
    )
    (net (code "181") (name "Net-(R50-A)") (class "Default")
      (node (ref "R50") (pin "1") (pinfunction "A_1") (pintype "passive"))
      (node (ref "R50") (pin "2") (pinfunction "S_2") (pintype "passive"))
      (node (ref "R51") (pin "1") (pinfunction "A_1") (pintype "passive"))
      (node (ref "R51") (pin "2") (pinfunction "S_2") (pintype "passive"))
      (node (ref "R52") (pin "1") (pinfunction "A_1") (pintype "passive"))
      (node (ref "R52") (pin "2") (pinfunction "S_2") (pintype "passive"))
      (node (ref "R53") (pin "1") (pinfunction "A_1") (pintype "passive"))
      (node (ref "R53") (pin "2") (pinfunction "S_2") (pintype "passive"))
      (node (ref "R_EXT_W") (pin "2") (pinfunction "2_2") (pintype "passive"))
      (node (ref "S8") (pin "2") (pinfunction "P_2") (pintype "passive"))
    )
    (net (code "182") (name "Net-(R50-E)") (class "Default")
      (node (ref "R50") (pin "3") (pinfunction "E_3") (pintype "passive"))
      (node (ref "S4") (pin "P$01") (pinfunction "1_P$01") (pintype "passive"))
    )
    (net (code "183") (name "Net-(R51-E)") (class "Default")
      (node (ref "R51") (pin "3") (pinfunction "E_3") (pintype "passive"))
      (node (ref "S4") (pin "P$02") (pinfunction "2_P$02") (pintype "passive"))
    )
    (net (code "184") (name "Net-(R52-E)") (class "Default")
      (node (ref "R52") (pin "3") (pinfunction "E_3") (pintype "passive"))
      (node (ref "S4") (pin "P$03") (pinfunction "3_P$03") (pintype "passive"))
    )
    (net (code "185") (name "Net-(R53-E)") (class "Default")
      (node (ref "R53") (pin "3") (pinfunction "E_3") (pintype "passive"))
      (node (ref "S4") (pin "P$04") (pinfunction "4_P$04") (pintype "passive"))
    )
    (net (code "186") (name "Net-(R72-Pad1)") (class "Default")
      (node (ref "R72") (pin "1") (pinfunction "1_1") (pintype "passive"))
      (node (ref "U$3") (pin "G") (pinfunction "G_G") (pintype "passive"))
    )
    (net (code "187") (name "Net-(R73-Pad1)") (class "Default")
      (node (ref "R73") (pin "1") (pinfunction "1_1") (pintype "passive"))
      (node (ref "U$2") (pin "G") (pinfunction "G_G") (pintype "passive"))
    )
    (net (code "188") (name "Net-(R74-A)") (class "Default")
      (node (ref "JP27") (pin "1") (pinfunction "1_1") (pintype "passive"))
      (node (ref "R74") (pin "1") (pinfunction "A_1") (pintype "passive"))
    )
    (net (code "189") (name "Net-(R74-S)") (class "Default")
      (node (ref "JP27") (pin "2") (pinfunction "2_2") (pintype "passive"))
      (node (ref "R74") (pin "2") (pinfunction "S_2") (pintype "passive"))
    )
    (net (code "190") (name "Net-(R75-A)") (class "Default")
      (node (ref "JP28") (pin "1") (pinfunction "1_1") (pintype "passive"))
      (node (ref "R75") (pin "1") (pinfunction "A_1") (pintype "passive"))
    )
    (net (code "191") (name "Net-(R75-S)") (class "Default")
      (node (ref "JP28") (pin "2") (pinfunction "2_2") (pintype "passive"))
      (node (ref "R75") (pin "2") (pinfunction "S_2") (pintype "passive"))
    )
    (net (code "192") (name "Net-(R76-A)") (class "Default")
      (node (ref "JP29") (pin "1") (pinfunction "1_1") (pintype "passive"))
      (node (ref "R76") (pin "1") (pinfunction "A_1") (pintype "passive"))
    )
    (net (code "193") (name "Net-(R76-S)") (class "Default")
      (node (ref "JP29") (pin "2") (pinfunction "2_2") (pintype "passive"))
      (node (ref "R76") (pin "2") (pinfunction "S_2") (pintype "passive"))
    )
    (net (code "194") (name "Net-(R77-A)") (class "Default")
      (node (ref "JP30") (pin "1") (pinfunction "1_1") (pintype "passive"))
      (node (ref "R77") (pin "1") (pinfunction "A_1") (pintype "passive"))
    )
    (net (code "195") (name "Net-(R77-S)") (class "Default")
      (node (ref "JP30") (pin "2") (pinfunction "2_2") (pintype "passive"))
      (node (ref "R77") (pin "2") (pinfunction "S_2") (pintype "passive"))
    )
    (net (code "196") (name "Net-(R78-A)") (class "Default")
      (node (ref "JP31") (pin "1") (pinfunction "1_1") (pintype "passive"))
      (node (ref "R78") (pin "1") (pinfunction "A_1") (pintype "passive"))
    )
    (net (code "197") (name "Net-(R78-S)") (class "Default")
      (node (ref "JP31") (pin "2") (pinfunction "2_2") (pintype "passive"))
      (node (ref "R78") (pin "2") (pinfunction "S_2") (pintype "passive"))
    )
    (net (code "198") (name "Net-(R79-A)") (class "Default")
      (node (ref "JP32") (pin "1") (pinfunction "1_1") (pintype "passive"))
      (node (ref "R79") (pin "1") (pinfunction "A_1") (pintype "passive"))
    )
    (net (code "199") (name "Net-(R79-S)") (class "Default")
      (node (ref "JP32") (pin "2") (pinfunction "2_2") (pintype "passive"))
      (node (ref "R79") (pin "2") (pinfunction "S_2") (pintype "passive"))
    )
    (net (code "200") (name "Net-(R80-A)") (class "Default")
      (node (ref "JP33") (pin "1") (pinfunction "1_1") (pintype "passive"))
      (node (ref "R80") (pin "1") (pinfunction "A_1") (pintype "passive"))
    )
    (net (code "201") (name "Net-(R80-S)") (class "Default")
      (node (ref "JP33") (pin "2") (pinfunction "2_2") (pintype "passive"))
      (node (ref "R80") (pin "2") (pinfunction "S_2") (pintype "passive"))
    )
    (net (code "202") (name "Net-(R81-A)") (class "Default")
      (node (ref "JP34") (pin "1") (pinfunction "1_1") (pintype "passive"))
      (node (ref "R81") (pin "1") (pinfunction "A_1") (pintype "passive"))
    )
    (net (code "203") (name "Net-(R81-S)") (class "Default")
      (node (ref "JP34") (pin "2") (pinfunction "2_2") (pintype "passive"))
      (node (ref "R81") (pin "2") (pinfunction "S_2") (pintype "passive"))
    )
    (net (code "204") (name "Net-(R82-A)") (class "Default")
      (node (ref "JP35") (pin "1") (pinfunction "1_1") (pintype "passive"))
      (node (ref "R82") (pin "1") (pinfunction "A_1") (pintype "passive"))
    )
    (net (code "205") (name "Net-(R82-S)") (class "Default")
      (node (ref "JP35") (pin "2") (pinfunction "2_2") (pintype "passive"))
      (node (ref "R82") (pin "2") (pinfunction "S_2") (pintype "passive"))
    )
    (net (code "206") (name "Net-(R83-A)") (class "Default")
      (node (ref "JP36") (pin "1") (pinfunction "1_1") (pintype "passive"))
      (node (ref "R83") (pin "1") (pinfunction "A_1") (pintype "passive"))
    )
    (net (code "207") (name "Net-(R83-S)") (class "Default")
      (node (ref "JP36") (pin "2") (pinfunction "2_2") (pintype "passive"))
      (node (ref "R83") (pin "2") (pinfunction "S_2") (pintype "passive"))
    )
    (net (code "208") (name "Net-(R84-A)") (class "Default")
      (node (ref "JP37") (pin "1") (pinfunction "1_1") (pintype "passive"))
      (node (ref "R84") (pin "1") (pinfunction "A_1") (pintype "passive"))
    )
    (net (code "209") (name "Net-(R84-S)") (class "Default")
      (node (ref "JP37") (pin "2") (pinfunction "2_2") (pintype "passive"))
      (node (ref "R84") (pin "2") (pinfunction "S_2") (pintype "passive"))
    )
    (net (code "210") (name "Net-(R85-A)") (class "Default")
      (node (ref "JP38") (pin "1") (pinfunction "1_1") (pintype "passive"))
      (node (ref "R85") (pin "1") (pinfunction "A_1") (pintype "passive"))
    )
    (net (code "211") (name "Net-(R85-S)") (class "Default")
      (node (ref "JP38") (pin "2") (pinfunction "2_2") (pintype "passive"))
      (node (ref "R85") (pin "2") (pinfunction "S_2") (pintype "passive"))
    )
    (net (code "212") (name "Net-(R86-S)") (class "Default")
      (node (ref "C107") (pin "1") (pinfunction "1_1") (pintype "passive"))
      (node (ref "R86") (pin "2") (pinfunction "S_2") (pintype "passive"))
      (node (ref "U4") (pin "5") (pinfunction "+IN_5") (pintype "input"))
    )
    (net (code "213") (name "Net-(R87-S)") (class "Default")
      (node (ref "C108") (pin "1") (pinfunction "1_1") (pintype "passive"))
      (node (ref "R87") (pin "2") (pinfunction "S_2") (pintype "passive"))
      (node (ref "U4") (pin "12") (pinfunction "+IN_12") (pintype "input"))
    )
    (net (code "214") (name "Net-(R88-S)") (class "Default")
      (node (ref "C109") (pin "1") (pinfunction "1_1") (pintype "passive"))
      (node (ref "R88") (pin "2") (pinfunction "S_2") (pintype "passive"))
      (node (ref "U4") (pin "14") (pinfunction "+IN_14") (pintype "input"))
    )
    (net (code "215") (name "Net-(R89-E)") (class "Default")
      (node (ref "R69") (pin "1") (pinfunction "1_1") (pintype "passive"))
      (node (ref "R89") (pin "2") (pinfunction "S_2") (pintype "passive"))
      (node (ref "R89") (pin "3") (pinfunction "E_3") (pintype "passive"))
      (node (ref "U3") (pin "6") (pinfunction "-IN_6") (pintype "input"))
    )
    (net (code "216") (name "Net-(R90-E)") (class "Default")
      (node (ref "R71") (pin "1") (pinfunction "1_1") (pintype "passive"))
      (node (ref "R90") (pin "2") (pinfunction "S_2") (pintype "passive"))
      (node (ref "R90") (pin "3") (pinfunction "E_3") (pintype "passive"))
      (node (ref "U3") (pin "15") (pinfunction "-IN_15") (pintype "input"))
    )
    (net (code "217") (name "Net-(R91-E)") (class "Default")
      (node (ref "R68") (pin "1") (pinfunction "1_1") (pintype "passive"))
      (node (ref "R91") (pin "2") (pinfunction "S_2") (pintype "passive"))
      (node (ref "R91") (pin "3") (pinfunction "E_3") (pintype "passive"))
      (node (ref "U3") (pin "2") (pinfunction "-IN_2") (pintype "input"))
    )
    (net (code "218") (name "Net-(R92-E)") (class "Default")
      (node (ref "R70") (pin "1") (pinfunction "1_1") (pintype "passive"))
      (node (ref "R92") (pin "2") (pinfunction "S_2") (pintype "passive"))
      (node (ref "R92") (pin "3") (pinfunction "E_3") (pintype "passive"))
      (node (ref "U3") (pin "11") (pinfunction "-IN_11") (pintype "input"))
    )
    (net (code "219") (name "Net-(R_DIG_1-H)") (class "Default")
      (node (ref "RDIG1") (pin "1") (pinfunction "1_1") (pintype "passive"))
      (node (ref "R_DIG_1") (pin "11") (pinfunction "H_11") (pintype "passive"))
    )
    (net (code "220") (name "Net-(R_DIG_1-W)") (class "Default")
      (node (ref "RDIG1") (pin "2") (pinfunction "2_2") (pintype "passive"))
      (node (ref "R_DIG_1") (pin "12") (pinfunction "W_12") (pintype "passive"))
    )
    (net (code "221") (name "Net-(R_DIG_2-H)") (class "Default")
      (node (ref "RDIG2") (pin "1") (pinfunction "1_1") (pintype "passive"))
      (node (ref "R_DIG_2") (pin "11") (pinfunction "H_11") (pintype "passive"))
    )
    (net (code "222") (name "Net-(R_DIG_2-W)") (class "Default")
      (node (ref "RDIG2") (pin "2") (pinfunction "2_2") (pintype "passive"))
      (node (ref "R_DIG_2") (pin "12") (pinfunction "W_12") (pintype "passive"))
    )
    (net (code "223") (name "Net-(R_DIG_IC-IN+)") (class "Default")
      (node (ref "R_DIG_IC") (pin "12") (pinfunction "W_12") (pintype "passive"))
      (node (ref "R_DIG_IC") (pin "9") (pinfunction "IN+_9") (pintype "input"))
    )
    (net (code "224") (name "Net-(R_DIG_IC-IN-)") (class "Default")
      (node (ref "IC_OUT") (pin "1") (pinfunction "1_1") (pintype "passive"))
      (node (ref "IC_OUT") (pin "2") (pinfunction "2_2") (pintype "passive"))
      (node (ref "IC_OUT") (pin "3") (pinfunction "3_3") (pintype "passive"))
      (node (ref "IC_OUT") (pin "4") (pinfunction "4_4") (pintype "passive"))
      (node (ref "R_DIG_IC") (pin "7") (pinfunction "OUT_7") (pintype "output"))
      (node (ref "R_DIG_IC") (pin "8") (pinfunction "IN-_8") (pintype "input"))
    )
    (net (code "225") (name "Net-(R_DIG_PWL-H)") (class "Default")
      (node (ref "R93") (pin "1") (pinfunction "1_1") (pintype "passive"))
      (node (ref "R_DIG_PWL") (pin "11") (pinfunction "H_11") (pintype "passive"))
    )
    (net (code "226") (name "Net-(S1-5)") (class "Default")
      (node (ref "R_EXT_X") (pin "1") (pinfunction "1_1") (pintype "passive"))
      (node (ref "S1") (pin "P$05") (pinfunction "5_P$05") (pintype "passive"))
    )
    (net (code "227") (name "Net-(S1-7)") (class "Default")
      (node (ref "C1") (pin "1") (pinfunction "1_1") (pintype "passive"))
      (node (ref "S1") (pin "P$07") (pinfunction "7_P$07") (pintype "passive"))
    )
    (net (code "228") (name "Net-(S1-8)") (class "Default")
      (node (ref "C2") (pin "1") (pinfunction "1_1") (pintype "passive"))
      (node (ref "S1") (pin "P$08") (pinfunction "8_P$08") (pintype "passive"))
    )
    (net (code "229") (name "Net-(S1-9)") (class "Default")
      (node (ref "C3") (pin "1") (pinfunction "1_1") (pintype "passive"))
      (node (ref "S1") (pin "P$09") (pinfunction "9_P$09") (pintype "passive"))
    )
    (net (code "230") (name "Net-(S1-10)") (class "Default")
      (node (ref "C4") (pin "1") (pinfunction "1_1") (pintype "passive"))
      (node (ref "S1") (pin "P$10") (pinfunction "10_P$10") (pintype "passive"))
    )
    (net (code "231") (name "Net-(S1-11)") (class "Default")
      (node (ref "C_EXT_X") (pin "1") (pinfunction "1_1") (pintype "passive"))
      (node (ref "S1") (pin "P$11") (pinfunction "11_P$11") (pintype "passive"))
    )
    (net (code "232") (name "Net-(S2-5)") (class "Default")
      (node (ref "R_EXT_Y") (pin "1") (pinfunction "1_1") (pintype "passive"))
      (node (ref "S2") (pin "P$05") (pinfunction "5_P$05") (pintype "passive"))
    )
    (net (code "233") (name "Net-(S2-7)") (class "Default")
      (node (ref "C60") (pin "1") (pinfunction "1_1") (pintype "passive"))
      (node (ref "S2") (pin "P$07") (pinfunction "7_P$07") (pintype "passive"))
    )
    (net (code "234") (name "Net-(S2-8)") (class "Default")
      (node (ref "C61") (pin "1") (pinfunction "1_1") (pintype "passive"))
      (node (ref "S2") (pin "P$08") (pinfunction "8_P$08") (pintype "passive"))
    )
    (net (code "235") (name "Net-(S2-9)") (class "Default")
      (node (ref "C62") (pin "1") (pinfunction "1_1") (pintype "passive"))
      (node (ref "S2") (pin "P$09") (pinfunction "9_P$09") (pintype "passive"))
    )
    (net (code "236") (name "Net-(S2-10)") (class "Default")
      (node (ref "C63") (pin "1") (pinfunction "1_1") (pintype "passive"))
      (node (ref "S2") (pin "P$10") (pinfunction "10_P$10") (pintype "passive"))
    )
    (net (code "237") (name "Net-(S2-11)") (class "Default")
      (node (ref "C_EXT_Y") (pin "1") (pinfunction "1_1") (pintype "passive"))
      (node (ref "S2") (pin "P$11") (pinfunction "11_P$11") (pintype "passive"))
    )
    (net (code "238") (name "Net-(S3-5)") (class "Default")
      (node (ref "R_EXT_Z") (pin "1") (pinfunction "1_1") (pintype "passive"))
      (node (ref "S3") (pin "P$05") (pinfunction "5_P$05") (pintype "passive"))
    )
    (net (code "239") (name "Net-(S3-7)") (class "Default")
      (node (ref "C66") (pin "1") (pinfunction "1_1") (pintype "passive"))
      (node (ref "S3") (pin "P$07") (pinfunction "7_P$07") (pintype "passive"))
    )
    (net (code "240") (name "Net-(S3-8)") (class "Default")
      (node (ref "C67") (pin "1") (pinfunction "1_1") (pintype "passive"))
      (node (ref "S3") (pin "P$08") (pinfunction "8_P$08") (pintype "passive"))
    )
    (net (code "241") (name "Net-(S3-9)") (class "Default")
      (node (ref "C68") (pin "1") (pinfunction "1_1") (pintype "passive"))
      (node (ref "S3") (pin "P$09") (pinfunction "9_P$09") (pintype "passive"))
    )
    (net (code "242") (name "Net-(S3-10)") (class "Default")
      (node (ref "C69") (pin "1") (pinfunction "1_1") (pintype "passive"))
      (node (ref "S3") (pin "P$10") (pinfunction "10_P$10") (pintype "passive"))
    )
    (net (code "243") (name "Net-(S3-11)") (class "Default")
      (node (ref "C_EXT_Z") (pin "1") (pinfunction "1_1") (pintype "passive"))
      (node (ref "S3") (pin "P$11") (pinfunction "11_P$11") (pintype "passive"))
    )
    (net (code "244") (name "Net-(S4-5)") (class "Default")
      (node (ref "R_EXT_W") (pin "1") (pinfunction "1_1") (pintype "passive"))
      (node (ref "S4") (pin "P$05") (pinfunction "5_P$05") (pintype "passive"))
    )
    (net (code "245") (name "Net-(S4-7)") (class "Default")
      (node (ref "C72") (pin "1") (pinfunction "1_1") (pintype "passive"))
      (node (ref "S4") (pin "P$07") (pinfunction "7_P$07") (pintype "passive"))
    )
    (net (code "246") (name "Net-(S4-8)") (class "Default")
      (node (ref "C73") (pin "1") (pinfunction "1_1") (pintype "passive"))
      (node (ref "S4") (pin "P$08") (pinfunction "8_P$08") (pintype "passive"))
    )
    (net (code "247") (name "Net-(S4-9)") (class "Default")
      (node (ref "C74") (pin "1") (pinfunction "1_1") (pintype "passive"))
      (node (ref "S4") (pin "P$09") (pinfunction "9_P$09") (pintype "passive"))
    )
    (net (code "248") (name "Net-(S4-10)") (class "Default")
      (node (ref "C75") (pin "1") (pinfunction "1_1") (pintype "passive"))
      (node (ref "S4") (pin "P$10") (pinfunction "10_P$10") (pintype "passive"))
    )
    (net (code "249") (name "Net-(S4-11)") (class "Default")
      (node (ref "C_EXT_W") (pin "1") (pinfunction "1_1") (pintype "passive"))
      (node (ref "S4") (pin "P$11") (pinfunction "11_P$11") (pintype "passive"))
    )
    (net (code "250") (name "Net-(S5A-S)") (class "Default")
      (node (ref "IN_INTEG_X") (pin "2") (pinfunction "2_2") (pintype "passive"))
      (node (ref "S5") (pin "3") (pinfunction "S_3") (pintype "passive"))
      (node (ref "S5") (pin "4") (pinfunction "O_4") (pintype "passive"))
    )
    (net (code "251") (name "Net-(S6A-S)") (class "Default")
      (node (ref "IN_INTEG_Y") (pin "2") (pinfunction "2_2") (pintype "passive"))
      (node (ref "S6") (pin "3") (pinfunction "S_3") (pintype "passive"))
      (node (ref "S6") (pin "4") (pinfunction "O_4") (pintype "passive"))
    )
    (net (code "252") (name "Net-(S7A-S)") (class "Default")
      (node (ref "IN_INTEG_Z") (pin "2") (pinfunction "2_2") (pintype "passive"))
      (node (ref "S7") (pin "3") (pinfunction "S_3") (pintype "passive"))
      (node (ref "S7") (pin "4") (pinfunction "O_4") (pintype "passive"))
    )
    (net (code "253") (name "Net-(S8A-S)") (class "Default")
      (node (ref "IN_INTEG_W") (pin "2") (pinfunction "2_2") (pintype "passive"))
      (node (ref "S8") (pin "3") (pinfunction "S_3") (pintype "passive"))
      (node (ref "S8") (pin "4") (pinfunction "O_4") (pintype "passive"))
    )
    (net (code "254") (name "Net-(S9A-P)") (class "Default")
      (node (ref "R41") (pin "1") (pinfunction "1_1") (pintype "passive"))
      (node (ref "S9") (pin "2") (pinfunction "P_2") (pintype "passive"))
    )
    (net (code "255") (name "Net-(U1A--IN)") (class "Default")
      (node (ref "R10") (pin "2") (pinfunction "2_2") (pintype "passive"))
      (node (ref "R11") (pin "2") (pinfunction "2_2") (pintype "passive"))
      (node (ref "R12") (pin "2") (pinfunction "2_2") (pintype "passive"))
      (node (ref "R13") (pin "1") (pinfunction "1_1") (pintype "passive"))
      (node (ref "R5") (pin "2") (pinfunction "2_2") (pintype "passive"))
      (node (ref "R6") (pin "2") (pinfunction "2_2") (pintype "passive"))
      (node (ref "R7") (pin "2") (pinfunction "2_2") (pintype "passive"))
      (node (ref "R8") (pin "2") (pinfunction "2_2") (pintype "passive"))
      (node (ref "R9") (pin "2") (pinfunction "2_2") (pintype "passive"))
      (node (ref "U1") (pin "2") (pinfunction "-IN_2") (pintype "input"))
    )
    (net (code "256") (name "Net-(U1B--IN)") (class "Default")
      (node (ref "R14") (pin "2") (pinfunction "2_2") (pintype "passive"))
      (node (ref "R15") (pin "2") (pinfunction "2_2") (pintype "passive"))
      (node (ref "R16") (pin "2") (pinfunction "2_2") (pintype "passive"))
      (node (ref "R17") (pin "2") (pinfunction "2_2") (pintype "passive"))
      (node (ref "R18") (pin "2") (pinfunction "2_2") (pintype "passive"))
      (node (ref "R19") (pin "2") (pinfunction "2_2") (pintype "passive"))
      (node (ref "R20") (pin "2") (pinfunction "2_2") (pintype "passive"))
      (node (ref "R21") (pin "2") (pinfunction "2_2") (pintype "passive"))
      (node (ref "R22") (pin "1") (pinfunction "1_1") (pintype "passive"))
      (node (ref "U1") (pin "6") (pinfunction "-IN_6") (pintype "input"))
    )
    (net (code "257") (name "Net-(U1C--IN)") (class "Default")
      (node (ref "R23") (pin "2") (pinfunction "2_2") (pintype "passive"))
      (node (ref "R24") (pin "2") (pinfunction "2_2") (pintype "passive"))
      (node (ref "R25") (pin "2") (pinfunction "2_2") (pintype "passive"))
      (node (ref "R26") (pin "2") (pinfunction "2_2") (pintype "passive"))
      (node (ref "R27") (pin "2") (pinfunction "2_2") (pintype "passive"))
      (node (ref "R28") (pin "2") (pinfunction "2_2") (pintype "passive"))
      (node (ref "R29") (pin "2") (pinfunction "2_2") (pintype "passive"))
      (node (ref "R30") (pin "2") (pinfunction "2_2") (pintype "passive"))
      (node (ref "R31") (pin "1") (pinfunction "1_1") (pintype "passive"))
      (node (ref "U1") (pin "11") (pinfunction "-IN_11") (pintype "input"))
    )
    (net (code "258") (name "Net-(U1D--IN)") (class "Default")
      (node (ref "R32") (pin "2") (pinfunction "2_2") (pintype "passive"))
      (node (ref "R33") (pin "2") (pinfunction "2_2") (pintype "passive"))
      (node (ref "R34") (pin "2") (pinfunction "2_2") (pintype "passive"))
      (node (ref "R35") (pin "2") (pinfunction "2_2") (pintype "passive"))
      (node (ref "R36") (pin "2") (pinfunction "2_2") (pintype "passive"))
      (node (ref "R37") (pin "2") (pinfunction "2_2") (pintype "passive"))
      (node (ref "R38") (pin "2") (pinfunction "2_2") (pintype "passive"))
      (node (ref "R39") (pin "2") (pinfunction "2_2") (pintype "passive"))
      (node (ref "R40") (pin "1") (pinfunction "1_1") (pintype "passive"))
      (node (ref "U1") (pin "15") (pinfunction "-IN_15") (pintype "input"))
    )
    (net (code "259") (name "Net-(U2A--IN)") (class "Default")
      (node (ref "R60") (pin "1") (pinfunction "1_1") (pintype "passive"))
      (node (ref "R61") (pin "2") (pinfunction "2_2") (pintype "passive"))
      (node (ref "U2") (pin "2") (pinfunction "-IN_2") (pintype "input"))
    )
    (net (code "260") (name "Net-(U2B--IN)") (class "Default")
      (node (ref "R62") (pin "1") (pinfunction "1_1") (pintype "passive"))
      (node (ref "R63") (pin "2") (pinfunction "2_2") (pintype "passive"))
      (node (ref "U2") (pin "6") (pinfunction "-IN_6") (pintype "input"))
    )
    (net (code "261") (name "Net-(U2C--IN)") (class "Default")
      (node (ref "R64") (pin "1") (pinfunction "1_1") (pintype "passive"))
      (node (ref "R65") (pin "2") (pinfunction "2_2") (pintype "passive"))
      (node (ref "U2") (pin "11") (pinfunction "-IN_11") (pintype "input"))
    )
    (net (code "262") (name "Net-(U2D--IN)") (class "Default")
      (node (ref "R66") (pin "1") (pinfunction "1_1") (pintype "passive"))
      (node (ref "R67") (pin "2") (pinfunction "2_2") (pintype "passive"))
      (node (ref "U2") (pin "15") (pinfunction "-IN_15") (pintype "input"))
    )
    (net (code "263") (name "Net-(U4A-+IN)") (class "Default")
      (node (ref "OA_LT1365") (pin "3") (pinfunction "3_3") (pintype "passive"))
      (node (ref "U4") (pin "3") (pinfunction "+IN_3") (pintype "input"))
    )
    (net (code "264") (name "Net-(U4A--IN)") (class "Default")
      (node (ref "OA_LT1365") (pin "2") (pinfunction "2_2") (pintype "passive"))
      (node (ref "U4") (pin "2") (pinfunction "-IN_2") (pintype "input"))
    )
    (net (code "265") (name "Net-(U4A-OUT)") (class "Default")
      (node (ref "OA_LT1365") (pin "1") (pinfunction "1_1") (pintype "passive"))
      (node (ref "U4") (pin "1") (pinfunction "OUT_1") (pintype "output"))
    )
    (net (code "266") (name "PDI") (class "Default")
      (node (ref "JP63") (pin "3") (pinfunction "3_3") (pintype "passive"))
      (node (ref "PROG") (pin "4") (pinfunction "4_4") (pintype "passive"))
    )
    (net (code "267") (name "PDO") (class "Default")
      (node (ref "JP63") (pin "4") (pinfunction "4_4") (pintype "passive"))
      (node (ref "PROG") (pin "6") (pinfunction "6_6") (pintype "passive"))
    )
    (net (code "268") (name "PWL_IN") (class "Default")
      (node (ref "AD_PWL") (pin "7") (pinfunction "VIN0_7") (pintype "input"))
      (node (ref "PWL") (pin "1") (pinfunction "1_1") (pintype "passive"))
      (node (ref "S9") (pin "3") (pinfunction "S_3") (pintype "passive"))
      (node (ref "S9") (pin "4") (pinfunction "O_4") (pintype "passive"))
    )
    (net (code "269") (name "PWL_OUT") (class "Default")
      (node (ref "CFA5") (pin "12") (pinfunction "6_12") (pintype "output"))
      (node (ref "PWL") (pin "2") (pinfunction "2_2") (pintype "passive"))
    )
    (net (code "270") (name "PWL_RESET") (class "Default")
      (node (ref "IC2") (pin "29") (pinfunction "PC6(/RESET)_29") (pintype "bidirectional"))
      (node (ref "JP62") (pin "6") (pinfunction "6_6") (pintype "passive"))
      (node (ref "R55") (pin "1") (pinfunction "1_1") (pintype "passive"))
    )
    (net (code "271") (name "RST") (class "Default")
      (node (ref "JP62") (pin "4") (pinfunction "4_4") (pintype "passive"))
      (node (ref "PROG") (pin "5") (pinfunction "5_5") (pintype "passive"))
    )
    (net (code "272") (name "SPI_CORE_CS_IC") (class "Default")
      (node (ref "IC1") (pin "29") (pinfunction "(IC1)PD4_29") (pintype "bidirectional"))
      (node (ref "R_DIG_IC") (pin "3") (pinfunction "~{CS}_3") (pintype "input"))
    )
    (net (code "273") (name "SPI_CORE_CS_OUT1") (class "Default")
      (node (ref "AD_OUT1") (pin "1") (pinfunction "~{CS}_1") (pintype "input"))
      (node (ref "IC1") (pin "30") (pinfunction "(XCK1)PD5_30") (pintype "bidirectional"))
    )
    (net (code "274") (name "SPI_CORE_CS_OUT2") (class "Default")
      (node (ref "AD_OUT2") (pin "1") (pinfunction "~{CS}_1") (pintype "input"))
      (node (ref "IC1") (pin "31") (pinfunction "(T1)PD6_31") (pintype "bidirectional"))
    )
    (net (code "275") (name "SPI_CORE_CS_R1") (class "Default")
      (node (ref "IC1") (pin "32") (pinfunction "(T2)PD7_32") (pintype "bidirectional"))
      (node (ref "R_DIG_1") (pin "3") (pinfunction "~{CS}_3") (pintype "input"))
    )
    (net (code "276") (name "SPI_CORE_CS_R2") (class "Default")
      (node (ref "IC1") (pin "14") (pinfunction "(OC0)PB4_14") (pintype "bidirectional"))
      (node (ref "R_DIG_2") (pin "3") (pinfunction "~{CS}_3") (pintype "input"))
    )
    (net (code "277") (name "SPI_CORE_MISO") (class "Default")
      (node (ref "AD_OUT1") (pin "12") (pinfunction "DOUT_12") (pintype "output"))
      (node (ref "AD_OUT2") (pin "12") (pinfunction "DOUT_12") (pintype "output"))
      (node (ref "IC1") (pin "13") (pinfunction "(MISO)PB3_13") (pintype "bidirectional"))
    )
    (net (code "278") (name "SPI_CORE_MOSI") (class "Default")
      (node (ref "AD_OUT1") (pin "2") (pinfunction "DIN_2") (pintype "input"))
      (node (ref "AD_OUT2") (pin "2") (pinfunction "DIN_2") (pintype "input"))
      (node (ref "IC1") (pin "12") (pinfunction "(MOSI)PB2_12") (pintype "bidirectional"))
      (node (ref "R_DIG_1") (pin "2") (pinfunction "DIN_2") (pintype "input"))
      (node (ref "R_DIG_2") (pin "2") (pinfunction "DIN_2") (pintype "input"))
      (node (ref "R_DIG_IC") (pin "2") (pinfunction "DIN_2") (pintype "input"))
    )
    (net (code "279") (name "SPI_CORE_SCLK") (class "Default")
      (node (ref "AD_OUT1") (pin "14") (pinfunction "SCLK_14") (pintype "input"))
      (node (ref "AD_OUT2") (pin "14") (pinfunction "SCLK_14") (pintype "input"))
      (node (ref "IC1") (pin "11") (pinfunction "(SCK)PB1_11") (pintype "bidirectional"))
      (node (ref "JP62") (pin "1") (pinfunction "1_1") (pintype "passive"))
      (node (ref "R_DIG_1") (pin "1") (pinfunction "SCLK_1") (pintype "input"))
      (node (ref "R_DIG_2") (pin "1") (pinfunction "SCLK_1") (pintype "input"))
      (node (ref "R_DIG_IC") (pin "1") (pinfunction "SCLK_1") (pintype "input"))
    )
    (net (code "280") (name "SPI_PWL_CS_AD") (class "Default")
      (node (ref "AD_PWL") (pin "1") (pinfunction "~{CS}_1") (pintype "input"))
      (node (ref "IC2") (pin "12") (pinfunction "PB0(ICP)_12") (pintype "bidirectional"))
    )
    (net (code "281") (name "SPI_PWL_CS_R_DIG") (class "Default")
      (node (ref "IC2") (pin "13") (pinfunction "PB1(OC1A)_13") (pintype "bidirectional"))
      (node (ref "R_DIG_PWL") (pin "3") (pinfunction "~{CS}_3") (pintype "input"))
    )
    (net (code "282") (name "SPI_PWL_MISO") (class "Default")
      (node (ref "AD_PWL") (pin "12") (pinfunction "DOUT_12") (pintype "output"))
      (node (ref "IC2") (pin "16") (pinfunction "PB4(MISO)_16") (pintype "bidirectional"))
      (node (ref "JP63") (pin "6") (pinfunction "6_6") (pintype "passive"))
    )
    (net (code "283") (name "SPI_PWL_MOSI") (class "Default")
      (node (ref "AD_PWL") (pin "2") (pinfunction "DIN_2") (pintype "input"))
      (node (ref "IC2") (pin "15") (pinfunction "PB3(MOSI/OC2)_15") (pintype "bidirectional"))
      (node (ref "JP63") (pin "5") (pinfunction "5_5") (pintype "passive"))
      (node (ref "R_DIG_PWL") (pin "2") (pinfunction "DIN_2") (pintype "input"))
    )
    (net (code "284") (name "SPI_PWL_SCLK") (class "Default")
      (node (ref "AD_PWL") (pin "14") (pinfunction "SCLK_14") (pintype "input"))
      (node (ref "IC2") (pin "17") (pinfunction "PB5(SCK)_17") (pintype "bidirectional"))
      (node (ref "JP62") (pin "5") (pinfunction "5_5") (pintype "passive"))
      (node (ref "R_DIG_PWL") (pin "1") (pinfunction "SCLK_1") (pintype "input"))
    )
    (net (code "285") (name "SUM_OUT_W") (class "Default")
      (node (ref "IN_INTEG_W") (pin "1") (pinfunction "1_1") (pintype "passive"))
      (node (ref "R40") (pin "2") (pinfunction "2_2") (pintype "passive"))
      (node (ref "SUM_OUT_W") (pin "1") (pinfunction "1_1") (pintype "passive"))
      (node (ref "U1") (pin "16") (pinfunction "OUT_16") (pintype "output"))
    )
    (net (code "286") (name "SUM_OUT_X") (class "Default")
      (node (ref "IN_INTEG_X") (pin "1") (pinfunction "1_1") (pintype "passive"))
      (node (ref "R13") (pin "2") (pinfunction "2_2") (pintype "passive"))
      (node (ref "SUM_OUT_X") (pin "1") (pinfunction "1_1") (pintype "passive"))
      (node (ref "U1") (pin "1") (pinfunction "OUT_1") (pintype "output"))
    )
    (net (code "287") (name "SUM_OUT_Y") (class "Default")
      (node (ref "IN_INTEG_Y") (pin "1") (pinfunction "1_1") (pintype "passive"))
      (node (ref "R22") (pin "2") (pinfunction "2_2") (pintype "passive"))
      (node (ref "SUM_OUT_Y") (pin "1") (pinfunction "1_1") (pintype "passive"))
      (node (ref "U1") (pin "7") (pinfunction "OUT_7") (pintype "output"))
    )
    (net (code "288") (name "SUM_OUT_Z") (class "Default")
      (node (ref "IN_INTEG_Z") (pin "1") (pinfunction "1_1") (pintype "passive"))
      (node (ref "R31") (pin "2") (pinfunction "2_2") (pintype "passive"))
      (node (ref "SUM_OUT_Z") (pin "1") (pinfunction "1_1") (pintype "passive"))
      (node (ref "U1") (pin "10") (pinfunction "OUT_10") (pintype "output"))
    )
    (net (code "289") (name "UART_PC_RX_TX") (class "Default")
      (node (ref "IC1") (pin "2") (pinfunction "(RXD/PDI)PE0_2") (pintype "bidirectional"))
      (node (ref "IC3") (pin "1") (pinfunction "TXD_1") (pintype "output"))
      (node (ref "JP63") (pin "1") (pinfunction "1_1") (pintype "passive"))
    )
    (net (code "290") (name "UART_PC_TX_RX") (class "Default")
      (node (ref "IC1") (pin "3") (pinfunction "(TXD/PDO)PE1_3") (pintype "bidirectional"))
      (node (ref "IC3") (pin "4") (pinfunction "RXD_4") (pintype "input"))
      (node (ref "JP63") (pin "2") (pinfunction "2_2") (pintype "passive"))
    )
    (net (code "291") (name "UART_PWL_RX_TX") (class "Default")
      (node (ref "IC1") (pin "27") (pinfunction "(RXD1/INT2)PD2_27") (pintype "bidirectional"))
      (node (ref "IC2") (pin "31") (pinfunction "PD1(TXD)_31") (pintype "bidirectional"))
    )
    (net (code "292") (name "UART_PWL_TX_RX") (class "Default")
      (node (ref "IC1") (pin "28") (pinfunction "(TXD1/INT3)PD3_28") (pintype "bidirectional"))
      (node (ref "IC2") (pin "30") (pinfunction "PD0(RXD)_30") (pintype "bidirectional"))
    )
    (net (code "293") (name "W") (class "Default")
      (node (ref "CFA4") (pin "11") (pinfunction "5_11") (pintype "passive"))
      (node (ref "R97") (pin "1") (pinfunction "1_1") (pintype "passive"))
      (node (ref "U$4") (pin "P$10") (pinfunction "10_P$10") (pintype "passive"))
    )
    (net (code "294") (name "X") (class "Default")
      (node (ref "CFA1") (pin "11") (pinfunction "5_11") (pintype "passive"))
      (node (ref "R94") (pin "1") (pinfunction "1_1") (pintype "passive"))
      (node (ref "U$4") (pin "P$01") (pinfunction "1_P$01") (pintype "passive"))
    )
    (net (code "295") (name "Y") (class "Default")
      (node (ref "CFA2") (pin "11") (pinfunction "5_11") (pintype "passive"))
      (node (ref "R95") (pin "1") (pinfunction "1_1") (pintype "passive"))
      (node (ref "U$4") (pin "P$04") (pinfunction "4_P$04") (pintype "passive"))
    )
    (net (code "296") (name "Z") (class "Default")
      (node (ref "CFA3") (pin "11") (pinfunction "5_11") (pintype "passive"))
      (node (ref "R96") (pin "1") (pinfunction "1_1") (pintype "passive"))
      (node (ref "U$4") (pin "P$07") (pinfunction "7_P$07") (pintype "passive"))
    )
    (net (code "297") (name "unconnected-(CFA1-1-Pad2)") (class "Default")
      (node (ref "CFA1") (pin "2") (pinfunction "1_2") (pintype "passive"))
    )
    (net (code "298") (name "unconnected-(CFA1-8-Pad15)") (class "Default")
      (node (ref "CFA1") (pin "15") (pinfunction "8_15") (pintype "passive"))
    )
    (net (code "299") (name "unconnected-(CFA2-1-Pad2)") (class "Default")
      (node (ref "CFA2") (pin "2") (pinfunction "1_2") (pintype "passive"))
    )
    (net (code "300") (name "unconnected-(CFA2-8-Pad15)") (class "Default")
      (node (ref "CFA2") (pin "15") (pinfunction "8_15") (pintype "passive"))
    )
    (net (code "301") (name "unconnected-(CFA3-1-Pad2)") (class "Default")
      (node (ref "CFA3") (pin "2") (pinfunction "1_2") (pintype "passive"))
    )
    (net (code "302") (name "unconnected-(CFA3-8-Pad15)") (class "Default")
      (node (ref "CFA3") (pin "15") (pinfunction "8_15") (pintype "passive"))
    )
    (net (code "303") (name "unconnected-(CFA4-1-Pad2)") (class "Default")
      (node (ref "CFA4") (pin "2") (pinfunction "1_2") (pintype "passive"))
    )
    (net (code "304") (name "unconnected-(CFA4-8-Pad15)") (class "Default")
      (node (ref "CFA4") (pin "15") (pinfunction "8_15") (pintype "passive"))
    )
    (net (code "305") (name "unconnected-(CFA5-1-Pad2)") (class "Default")
      (node (ref "CFA5") (pin "2") (pinfunction "1_2") (pintype "passive"))
    )
    (net (code "306") (name "unconnected-(CFA5-8-Pad15)") (class "Default")
      (node (ref "CFA5") (pin "15") (pinfunction "8_15") (pintype "passive"))
    )
    (net (code "307") (name "unconnected-(IC1-(AD0)PA0-Pad51)") (class "Default")
      (node (ref "IC1") (pin "51") (pinfunction "(AD0)PA0_51") (pintype "bidirectional"))
    )
    (net (code "308") (name "unconnected-(IC1-(AD1)PA1-Pad50)") (class "Default")
      (node (ref "IC1") (pin "50") (pinfunction "(AD1)PA1_50") (pintype "bidirectional"))
    )
    (net (code "309") (name "unconnected-(IC1-(AD2)PA2-Pad49)") (class "Default")
      (node (ref "IC1") (pin "49") (pinfunction "(AD2)PA2_49") (pintype "bidirectional"))
    )
    (net (code "310") (name "unconnected-(IC1-(AD3)PA3-Pad48)") (class "Default")
      (node (ref "IC1") (pin "48") (pinfunction "(AD3)PA3_48") (pintype "bidirectional"))
    )
    (net (code "311") (name "unconnected-(IC1-(AD4)PA4-Pad47)") (class "Default")
      (node (ref "IC1") (pin "47") (pinfunction "(AD4)PA4_47") (pintype "bidirectional"))
    )
    (net (code "312") (name "unconnected-(IC1-(AD5)PA5-Pad46)") (class "Default")
      (node (ref "IC1") (pin "46") (pinfunction "(AD5)PA5_46") (pintype "bidirectional"))
    )
    (net (code "313") (name "unconnected-(IC1-(AD6)PA6-Pad45)") (class "Default")
      (node (ref "IC1") (pin "45") (pinfunction "(AD6)PA6_45") (pintype "bidirectional"))
    )
    (net (code "314") (name "unconnected-(IC1-(AD7)PA7-Pad44)") (class "Default")
      (node (ref "IC1") (pin "44") (pinfunction "(AD7)PA7_44") (pintype "bidirectional"))
    )
    (net (code "315") (name "unconnected-(IC1-(IC3{slash}INT7)PE7-Pad9)") (class "Default")
      (node (ref "IC1") (pin "9") (pinfunction "(IC3/INT7)PE7_9") (pintype "bidirectional"))
    )
    (net (code "316") (name "unconnected-(IC1-(OC1A)PB5-Pad15)") (class "Default")
      (node (ref "IC1") (pin "15") (pinfunction "(OC1A)PB5_15") (pintype "bidirectional"))
    )
    (net (code "317") (name "unconnected-(IC1-(OC1B)PB6-Pad16)") (class "Default")
      (node (ref "IC1") (pin "16") (pinfunction "(OC1B)PB6_16") (pintype "bidirectional"))
    )
    (net (code "318") (name "unconnected-(IC1-(OC2{slash}OC1C)PB7-Pad17)") (class "Default")
      (node (ref "IC1") (pin "17") (pinfunction "(OC2/OC1C)PB7_17") (pintype "bidirectional"))
    )
    (net (code "319") (name "unconnected-(IC1-(OC3A{slash}AIN1)PE3-Pad5)") (class "Default")
      (node (ref "IC1") (pin "5") (pinfunction "(OC3A/AIN1)PE3_5") (pintype "bidirectional"))
    )
    (net (code "320") (name "unconnected-(IC1-(OC3B{slash}INT4)PE4-Pad6)") (class "Default")
      (node (ref "IC1") (pin "6") (pinfunction "(OC3B/INT4)PE4_6") (pintype "bidirectional"))
    )
    (net (code "321") (name "unconnected-(IC1-(OC3C{slash}INT5)PE5-Pad7)") (class "Default")
      (node (ref "IC1") (pin "7") (pinfunction "(OC3C/INT5)PE5_7") (pintype "bidirectional"))
    )
    (net (code "322") (name "unconnected-(IC1-(SS)PB0-Pad10)") (class "Default")
      (node (ref "IC1") (pin "10") (pinfunction "(SS)PB0_10") (pintype "bidirectional"))
    )
    (net (code "323") (name "unconnected-(IC1-(T3{slash}INT6)PE6-Pad8)") (class "Default")
      (node (ref "IC1") (pin "8") (pinfunction "(T3/INT6)PE6_8") (pintype "bidirectional"))
    )
    (net (code "324") (name "unconnected-(IC1-(XCK0{slash}AIN0)PE2-Pad4)") (class "Default")
      (node (ref "IC1") (pin "4") (pinfunction "(XCK0/AIN0)PE2_4") (pintype "bidirectional"))
    )
    (net (code "325") (name "unconnected-(IC1-AREF-Pad62)") (class "Default")
      (node (ref "IC1") (pin "62") (pinfunction "AREF_62") (pintype "passive"))
    )
    (net (code "326") (name "unconnected-(IC1-PEN-Pad1)") (class "Default")
      (node (ref "IC1") (pin "1") (pinfunction "PEN_1") (pintype "input"))
    )
    (net (code "327") (name "unconnected-(IC1-PF0(ADC0)-Pad61)") (class "Default")
      (node (ref "IC1") (pin "61") (pinfunction "PF0(ADC0)_61") (pintype "input"))
    )
    (net (code "328") (name "unconnected-(IC1-PF1(ADC1)-Pad60)") (class "Default")
      (node (ref "IC1") (pin "60") (pinfunction "PF1(ADC1)_60") (pintype "input"))
    )
    (net (code "329") (name "unconnected-(IC1-PF2(ADC2)-Pad59)") (class "Default")
      (node (ref "IC1") (pin "59") (pinfunction "PF2(ADC2)_59") (pintype "input"))
    )
    (net (code "330") (name "unconnected-(IC1-PF3(ADC3)-Pad58)") (class "Default")
      (node (ref "IC1") (pin "58") (pinfunction "PF3(ADC3)_58") (pintype "input"))
    )
    (net (code "331") (name "unconnected-(IC1-PF4(ADC4{slash}TCK)-Pad57)") (class "Default")
      (node (ref "IC1") (pin "57") (pinfunction "PF4(ADC4/TCK)_57") (pintype "input"))
    )
    (net (code "332") (name "unconnected-(IC1-PF5(ADC5{slash}TMS)-Pad56)") (class "Default")
      (node (ref "IC1") (pin "56") (pinfunction "PF5(ADC5/TMS)_56") (pintype "input"))
    )
    (net (code "333") (name "unconnected-(IC1-PF6(ADC6{slash}TDO)-Pad55)") (class "Default")
      (node (ref "IC1") (pin "55") (pinfunction "PF6(ADC6/TDO)_55") (pintype "input"))
    )
    (net (code "334") (name "unconnected-(IC1-PF7(ADC7{slash}TDI)-Pad54)") (class "Default")
      (node (ref "IC1") (pin "54") (pinfunction "PF7(ADC7/TDI)_54") (pintype "input"))
    )
    (net (code "335") (name "unconnected-(IC1-PG0(WR)-Pad33)") (class "Default")
      (node (ref "IC1") (pin "33") (pinfunction "PG0(WR)_33") (pintype "bidirectional"))
    )
    (net (code "336") (name "unconnected-(IC1-PG1(RD)-Pad34)") (class "Default")
      (node (ref "IC1") (pin "34") (pinfunction "PG1(RD)_34") (pintype "bidirectional"))
    )
    (net (code "337") (name "unconnected-(IC1-PG2(ALE)-Pad43)") (class "Default")
      (node (ref "IC1") (pin "43") (pinfunction "PG2(ALE)_43") (pintype "bidirectional"))
    )
    (net (code "338") (name "unconnected-(IC1-PG3(TOSC2)-Pad18)") (class "Default")
      (node (ref "IC1") (pin "18") (pinfunction "PG3(TOSC2)_18") (pintype "bidirectional"))
    )
    (net (code "339") (name "unconnected-(IC1-PG4(TOSC1)-Pad19)") (class "Default")
      (node (ref "IC1") (pin "19") (pinfunction "PG4(TOSC1)_19") (pintype "bidirectional"))
    )
    (net (code "340") (name "unconnected-(IC2-ADC6-Pad19)") (class "Default")
      (node (ref "IC2") (pin "19") (pinfunction "ADC6_19") (pintype "bidirectional"))
    )
    (net (code "341") (name "unconnected-(IC2-ADC7-Pad22)") (class "Default")
      (node (ref "IC2") (pin "22") (pinfunction "ADC7_22") (pintype "bidirectional"))
    )
    (net (code "342") (name "unconnected-(IC2-AREF-Pad20)") (class "Default")
      (node (ref "IC2") (pin "20") (pinfunction "AREF_20") (pintype "passive"))
    )
    (net (code "343") (name "unconnected-(IC2-PB2(SS{slash}OC1B)-Pad14)") (class "Default")
      (node (ref "IC2") (pin "14") (pinfunction "PB2(SS/OC1B)_14") (pintype "bidirectional"))
    )
    (net (code "344") (name "unconnected-(IC2-PC0(ADC0)-Pad23)") (class "Default")
      (node (ref "IC2") (pin "23") (pinfunction "PC0(ADC0)_23") (pintype "bidirectional"))
    )
    (net (code "345") (name "unconnected-(IC2-PC1(ADC1)-Pad24)") (class "Default")
      (node (ref "IC2") (pin "24") (pinfunction "PC1(ADC1)_24") (pintype "bidirectional"))
    )
    (net (code "346") (name "unconnected-(IC2-PC2(ADC2)-Pad25)") (class "Default")
      (node (ref "IC2") (pin "25") (pinfunction "PC2(ADC2)_25") (pintype "bidirectional"))
    )
    (net (code "347") (name "unconnected-(IC2-PC3(ADC3)-Pad26)") (class "Default")
      (node (ref "IC2") (pin "26") (pinfunction "PC3(ADC3)_26") (pintype "bidirectional"))
    )
    (net (code "348") (name "unconnected-(IC2-PC4(ADC4{slash}SDA)-Pad27)") (class "Default")
      (node (ref "IC2") (pin "27") (pinfunction "PC4(ADC4/SDA)_27") (pintype "bidirectional"))
    )
    (net (code "349") (name "unconnected-(IC2-PC5(ADC5{slash}SCL)-Pad28)") (class "Default")
      (node (ref "IC2") (pin "28") (pinfunction "PC5(ADC5/SCL)_28") (pintype "bidirectional"))
    )
    (net (code "350") (name "unconnected-(IC2-PD2(INT0)-Pad32)") (class "Default")
      (node (ref "IC2") (pin "32") (pinfunction "PD2(INT0)_32") (pintype "bidirectional"))
    )
    (net (code "351") (name "unconnected-(IC2-PD3(INT1)-Pad1)") (class "Default")
      (node (ref "IC2") (pin "1") (pinfunction "PD3(INT1)_1") (pintype "bidirectional"))
    )
    (net (code "352") (name "unconnected-(IC2-PD4(XCK{slash}T0)-Pad2)") (class "Default")
      (node (ref "IC2") (pin "2") (pinfunction "PD4(XCK/T0)_2") (pintype "bidirectional"))
    )
    (net (code "353") (name "unconnected-(IC2-PD5(T1)-Pad9)") (class "Default")
      (node (ref "IC2") (pin "9") (pinfunction "PD5(T1)_9") (pintype "bidirectional"))
    )
    (net (code "354") (name "unconnected-(IC2-PD6(AIN0)-Pad10)") (class "Default")
      (node (ref "IC2") (pin "10") (pinfunction "PD6(AIN0)_10") (pintype "bidirectional"))
    )
    (net (code "355") (name "unconnected-(IC2-PD7(AIN1)-Pad11)") (class "Default")
      (node (ref "IC2") (pin "11") (pinfunction "PD7(AIN1)_11") (pintype "bidirectional"))
    )
    (net (code "356") (name "unconnected-(IC3-CBUS0-Pad15)") (class "Default")
      (node (ref "IC3") (pin "15") (pinfunction "CBUS0_15") (pintype "bidirectional"))
    )
    (net (code "357") (name "unconnected-(IC3-CBUS1-Pad14)") (class "Default")
      (node (ref "IC3") (pin "14") (pinfunction "CBUS1_14") (pintype "bidirectional"))
    )
    (net (code "358") (name "unconnected-(IC3-CBUS2-Pad7)") (class "Default")
      (node (ref "IC3") (pin "7") (pinfunction "CBUS2_7") (pintype "bidirectional"))
    )
    (net (code "359") (name "unconnected-(IC3-CBUS3-Pad16)") (class "Default")
      (node (ref "IC3") (pin "16") (pinfunction "CBUS3_16") (pintype "bidirectional"))
    )
    (net (code "360") (name "unconnected-(IC3-~{CTS}-Pad6)") (class "Default")
      (node (ref "IC3") (pin "6") (pinfunction "~{CTS}_6") (pintype "input"))
    )
    (net (code "361") (name "unconnected-(IC3-~{RTS}-Pad2)") (class "Default")
      (node (ref "IC3") (pin "2") (pinfunction "~{RTS}_2") (pintype "output"))
    )
    (net (code "362") (name "unconnected-(R77-E-Pad3)") (class "Default")
      (node (ref "R77") (pin "3") (pinfunction "E_3") (pintype "passive"))
    )
    (net (code "363") (name "unconnected-(R80-E-Pad3)") (class "Default")
      (node (ref "R80") (pin "3") (pinfunction "E_3") (pintype "passive"))
    )
    (net (code "364") (name "unconnected-(R_DIG_1-IN+-Pad9)") (class "Default")
      (node (ref "R_DIG_1") (pin "9") (pinfunction "IN+_9") (pintype "input"))
    )
    (net (code "365") (name "unconnected-(R_DIG_1-IN--Pad8)") (class "Default")
      (node (ref "R_DIG_1") (pin "8") (pinfunction "IN-_8") (pintype "input"))
    )
    (net (code "366") (name "unconnected-(R_DIG_1-OUT-Pad7)") (class "Default")
      (node (ref "R_DIG_1") (pin "7") (pinfunction "OUT_7") (pintype "output"))
    )
    (net (code "367") (name "unconnected-(R_DIG_1-~{SHDN}-Pad4)") (class "Default")
      (node (ref "R_DIG_1") (pin "4") (pinfunction "~{SHDN}_4") (pintype "input"))
    )
    (net (code "368") (name "unconnected-(R_DIG_2-IN+-Pad9)") (class "Default")
      (node (ref "R_DIG_2") (pin "9") (pinfunction "IN+_9") (pintype "input"))
    )
    (net (code "369") (name "unconnected-(R_DIG_2-IN--Pad8)") (class "Default")
      (node (ref "R_DIG_2") (pin "8") (pinfunction "IN-_8") (pintype "input"))
    )
    (net (code "370") (name "unconnected-(R_DIG_2-OUT-Pad7)") (class "Default")
      (node (ref "R_DIG_2") (pin "7") (pinfunction "OUT_7") (pintype "output"))
    )
    (net (code "371") (name "unconnected-(R_DIG_2-~{SHDN}-Pad4)") (class "Default")
      (node (ref "R_DIG_2") (pin "4") (pinfunction "~{SHDN}_4") (pintype "input"))
    )
    (net (code "372") (name "unconnected-(R_DIG_PWL-IN+-Pad9)") (class "Default")
      (node (ref "R_DIG_PWL") (pin "9") (pinfunction "IN+_9") (pintype "input"))
    )
    (net (code "373") (name "unconnected-(R_DIG_PWL-IN--Pad8)") (class "Default")
      (node (ref "R_DIG_PWL") (pin "8") (pinfunction "IN-_8") (pintype "input"))
    )
    (net (code "374") (name "unconnected-(R_DIG_PWL-OUT-Pad7)") (class "Default")
      (node (ref "R_DIG_PWL") (pin "7") (pinfunction "OUT_7") (pintype "output"))
    )
    (net (code "375") (name "unconnected-(U$1-ID-Pad4)") (class "Default")
      (node (ref "U$1") (pin "4") (pinfunction "ID_4") (pintype "bidirectional"))
    )
  )
)
